# expansion_board_V0.net
KiCad netlist of a schematic drawn in EAGLE
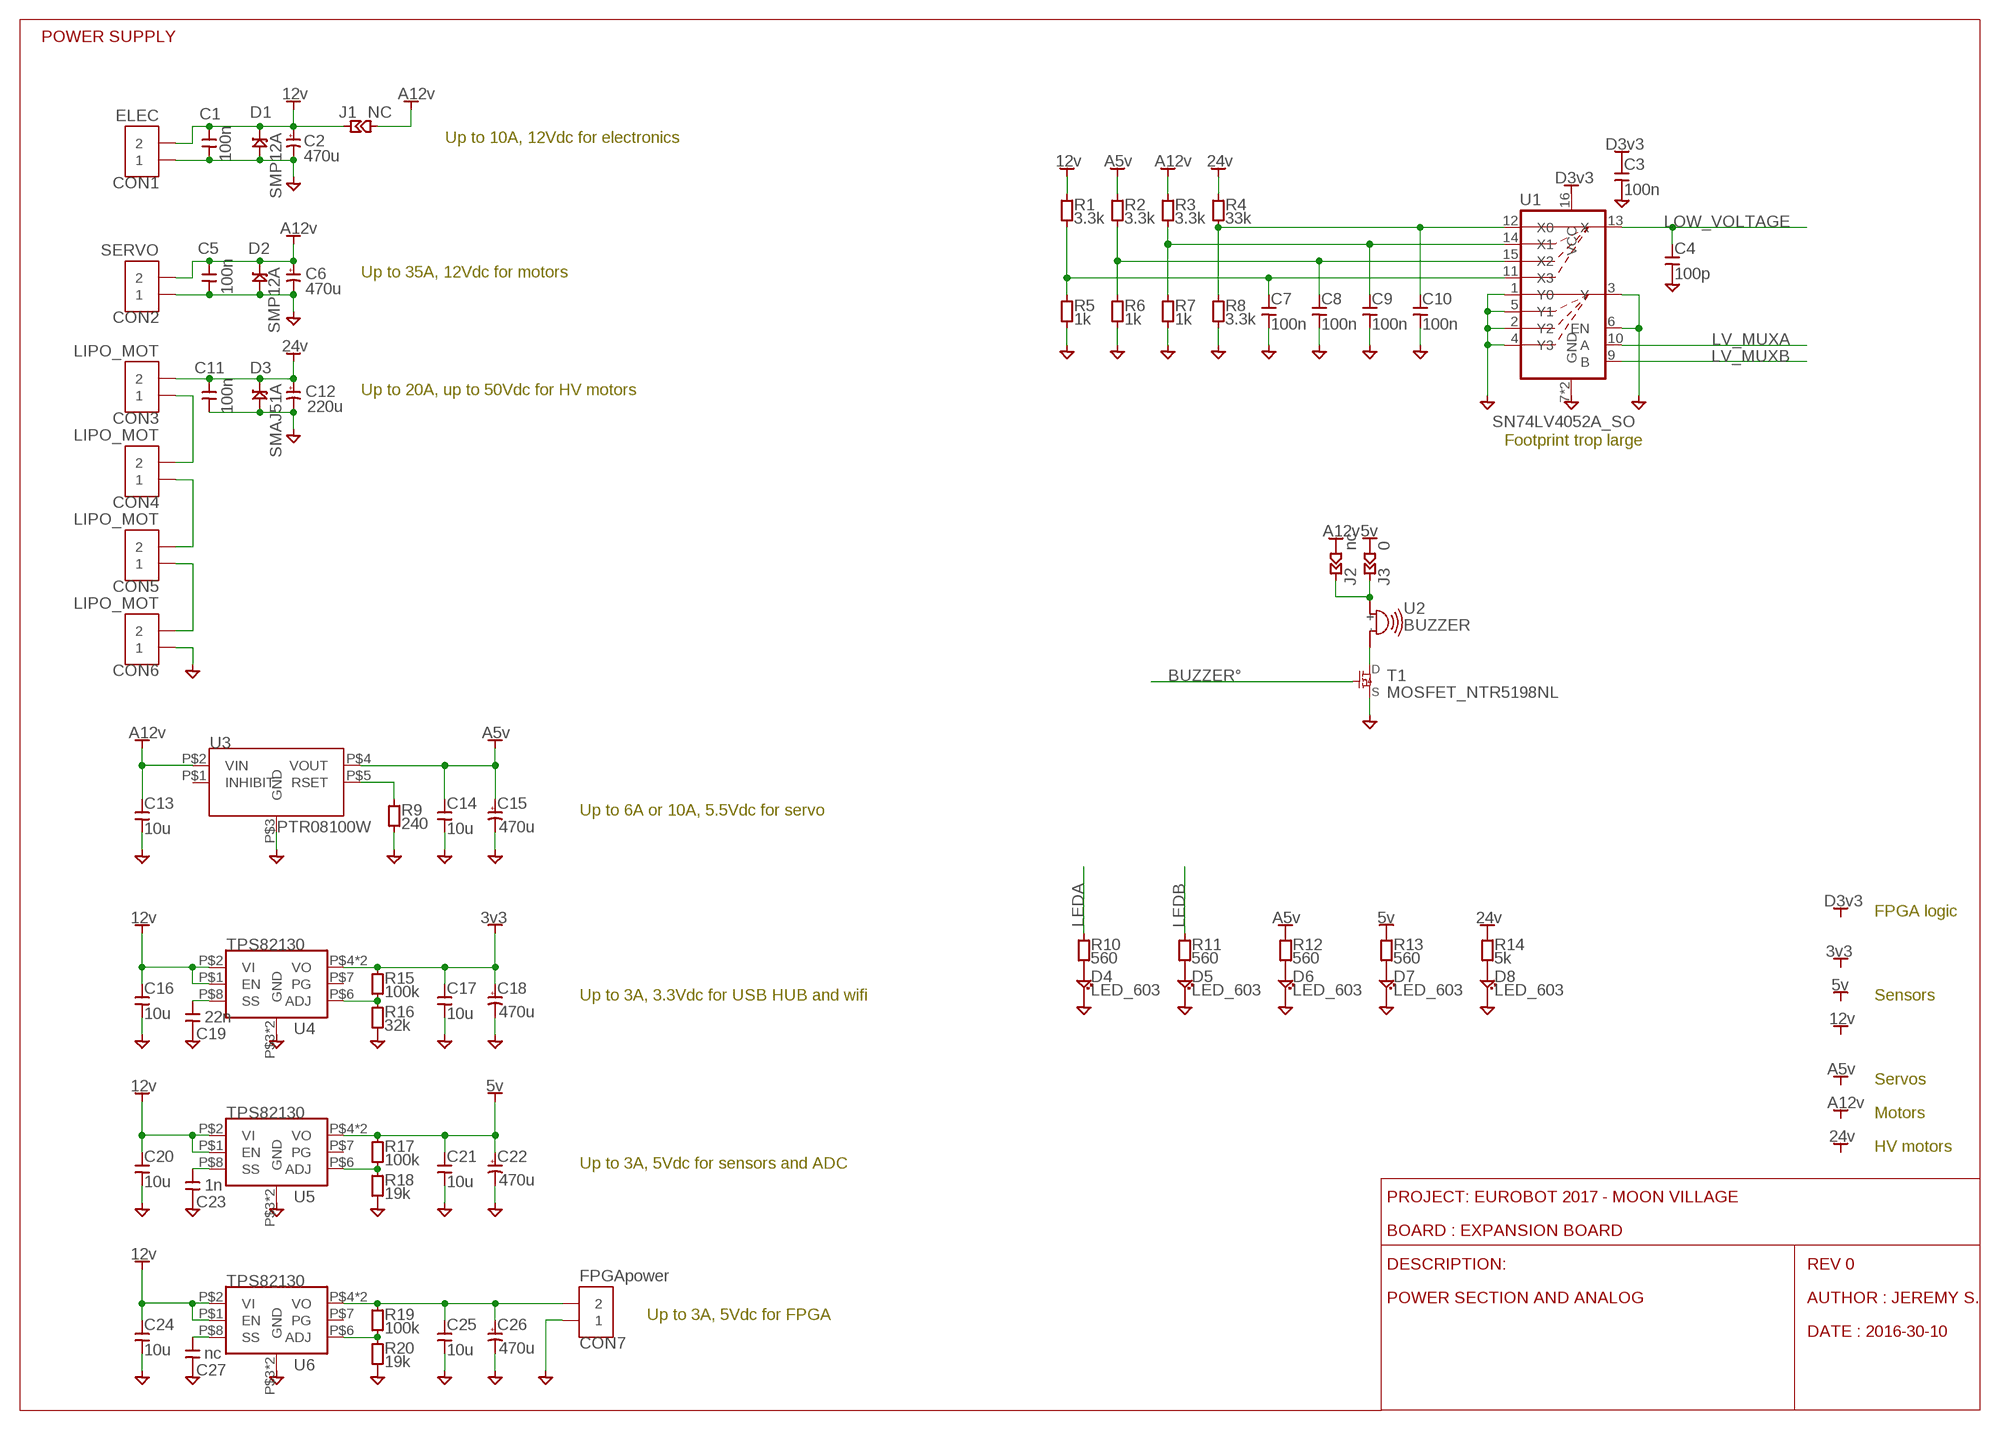
[diagram p0: schematic, sheet 1]
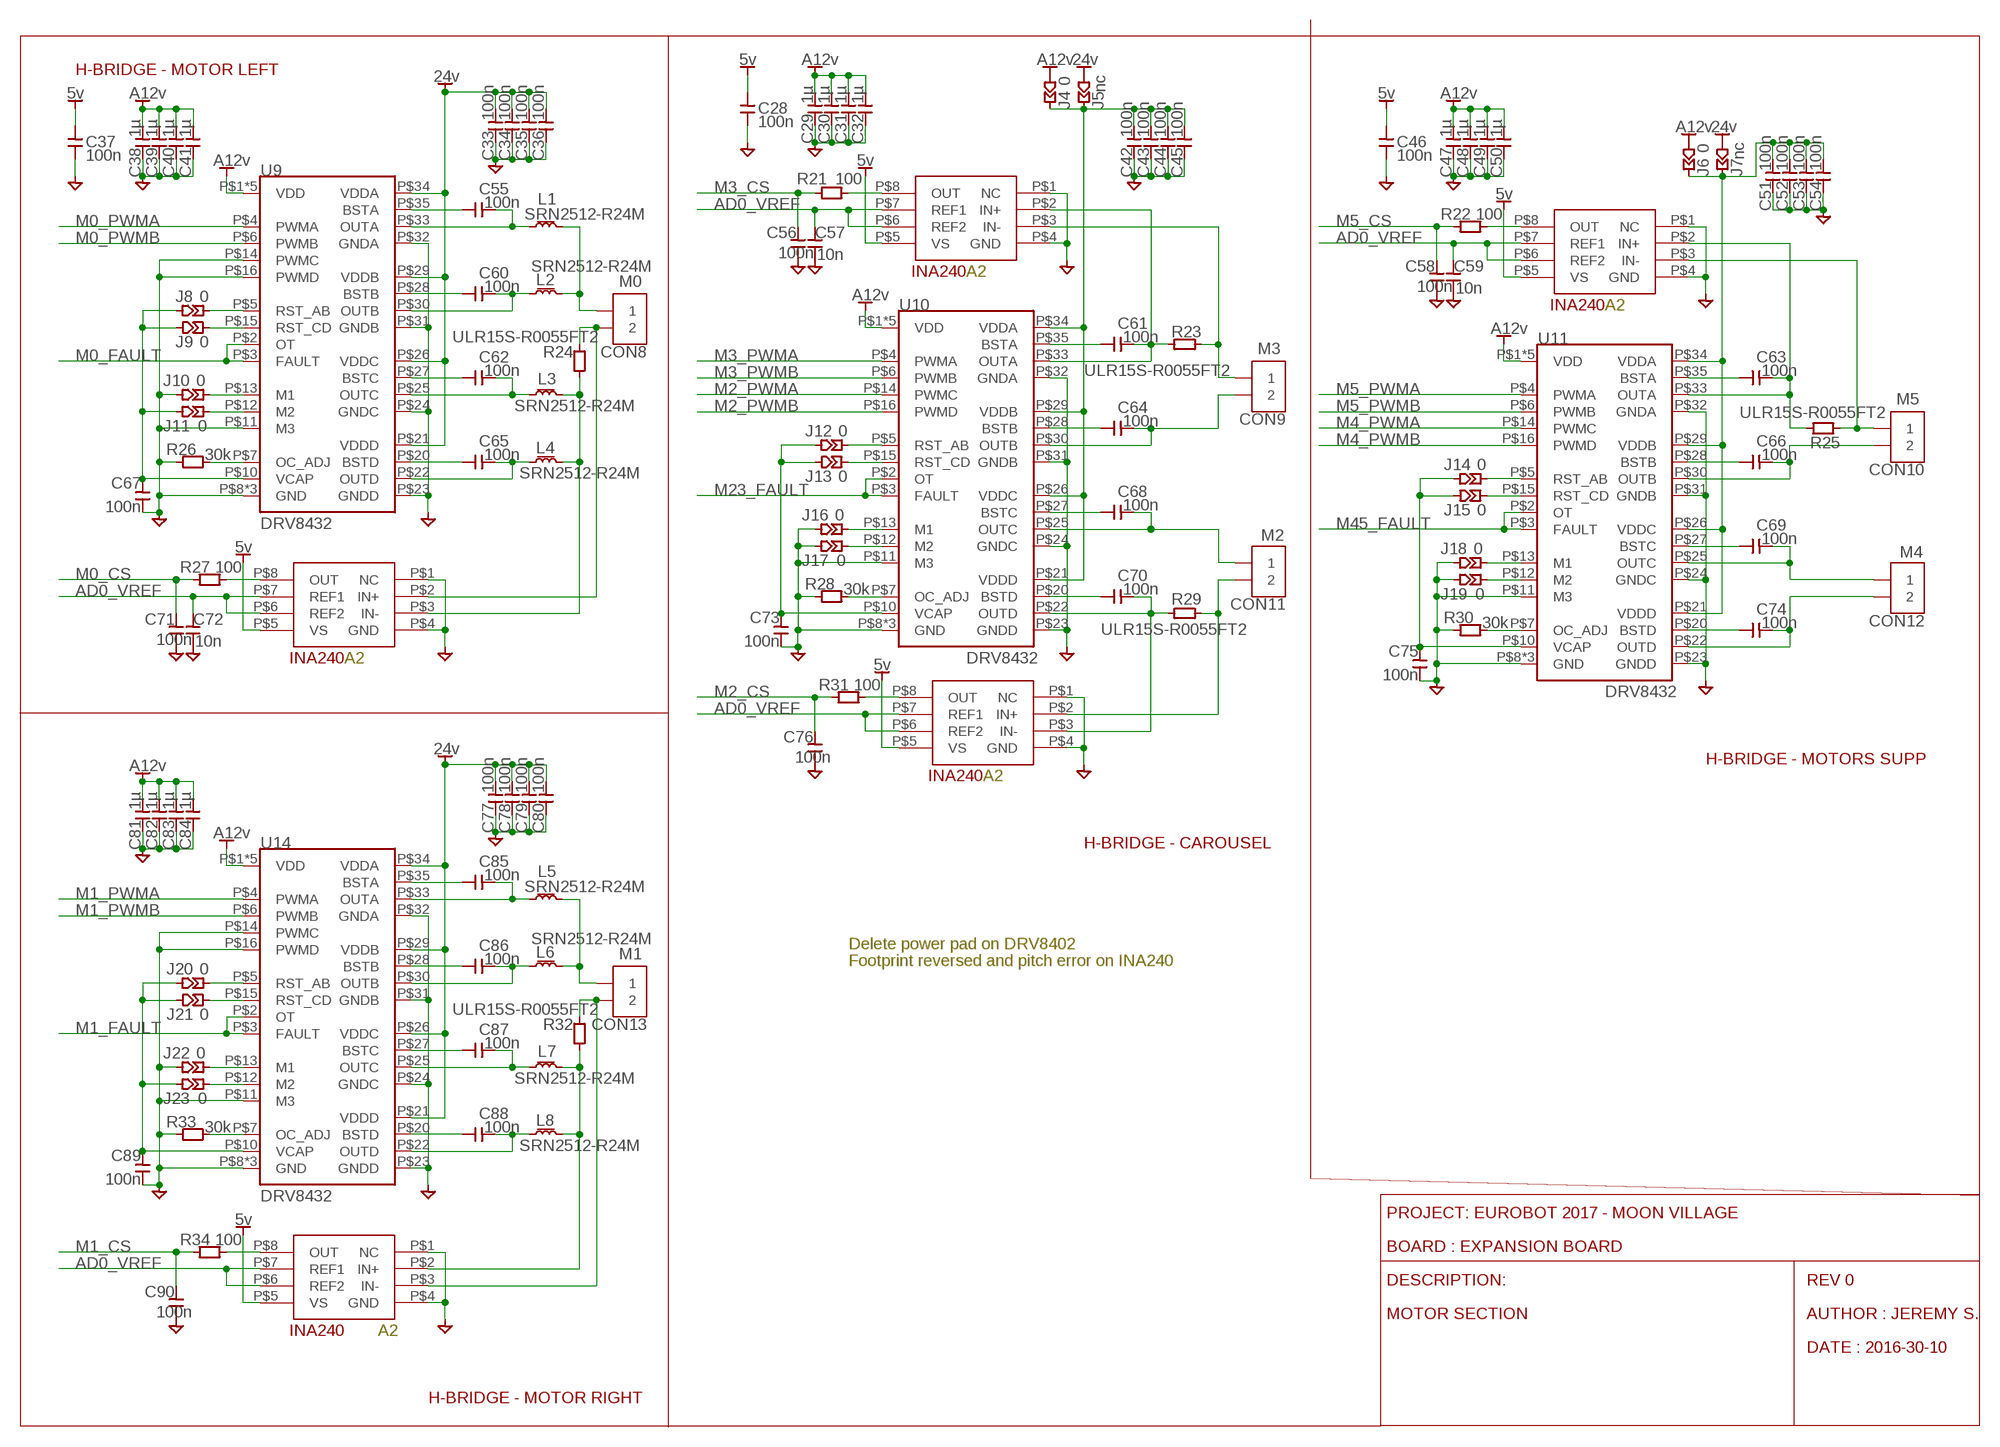
[diagram p1: schematic, sheet 2]
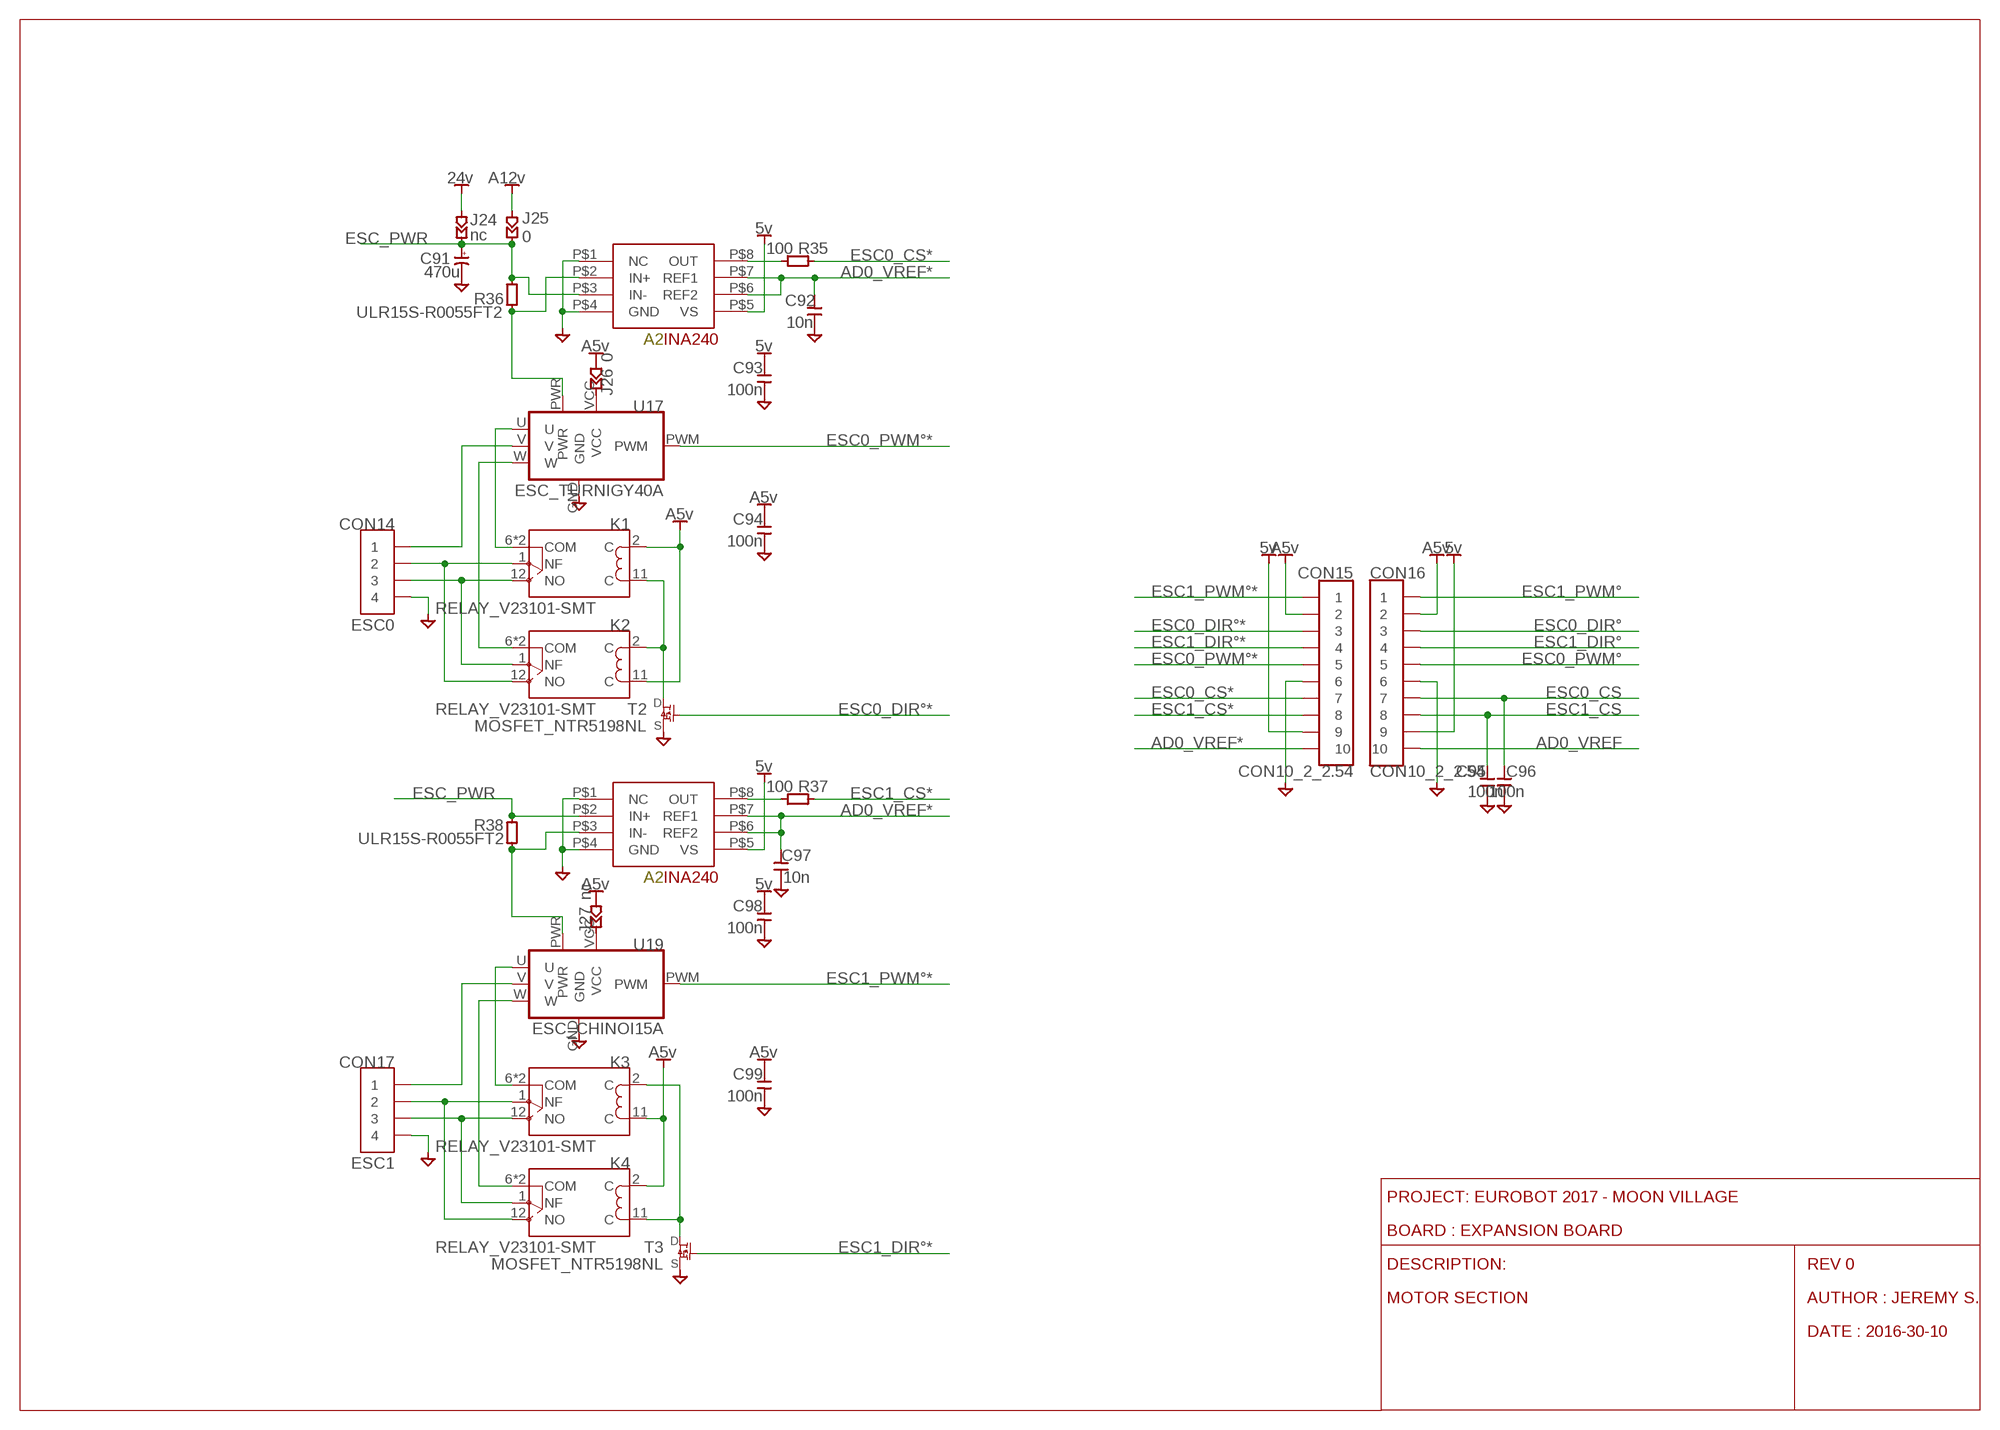
[diagram p2: schematic, sheet 3]
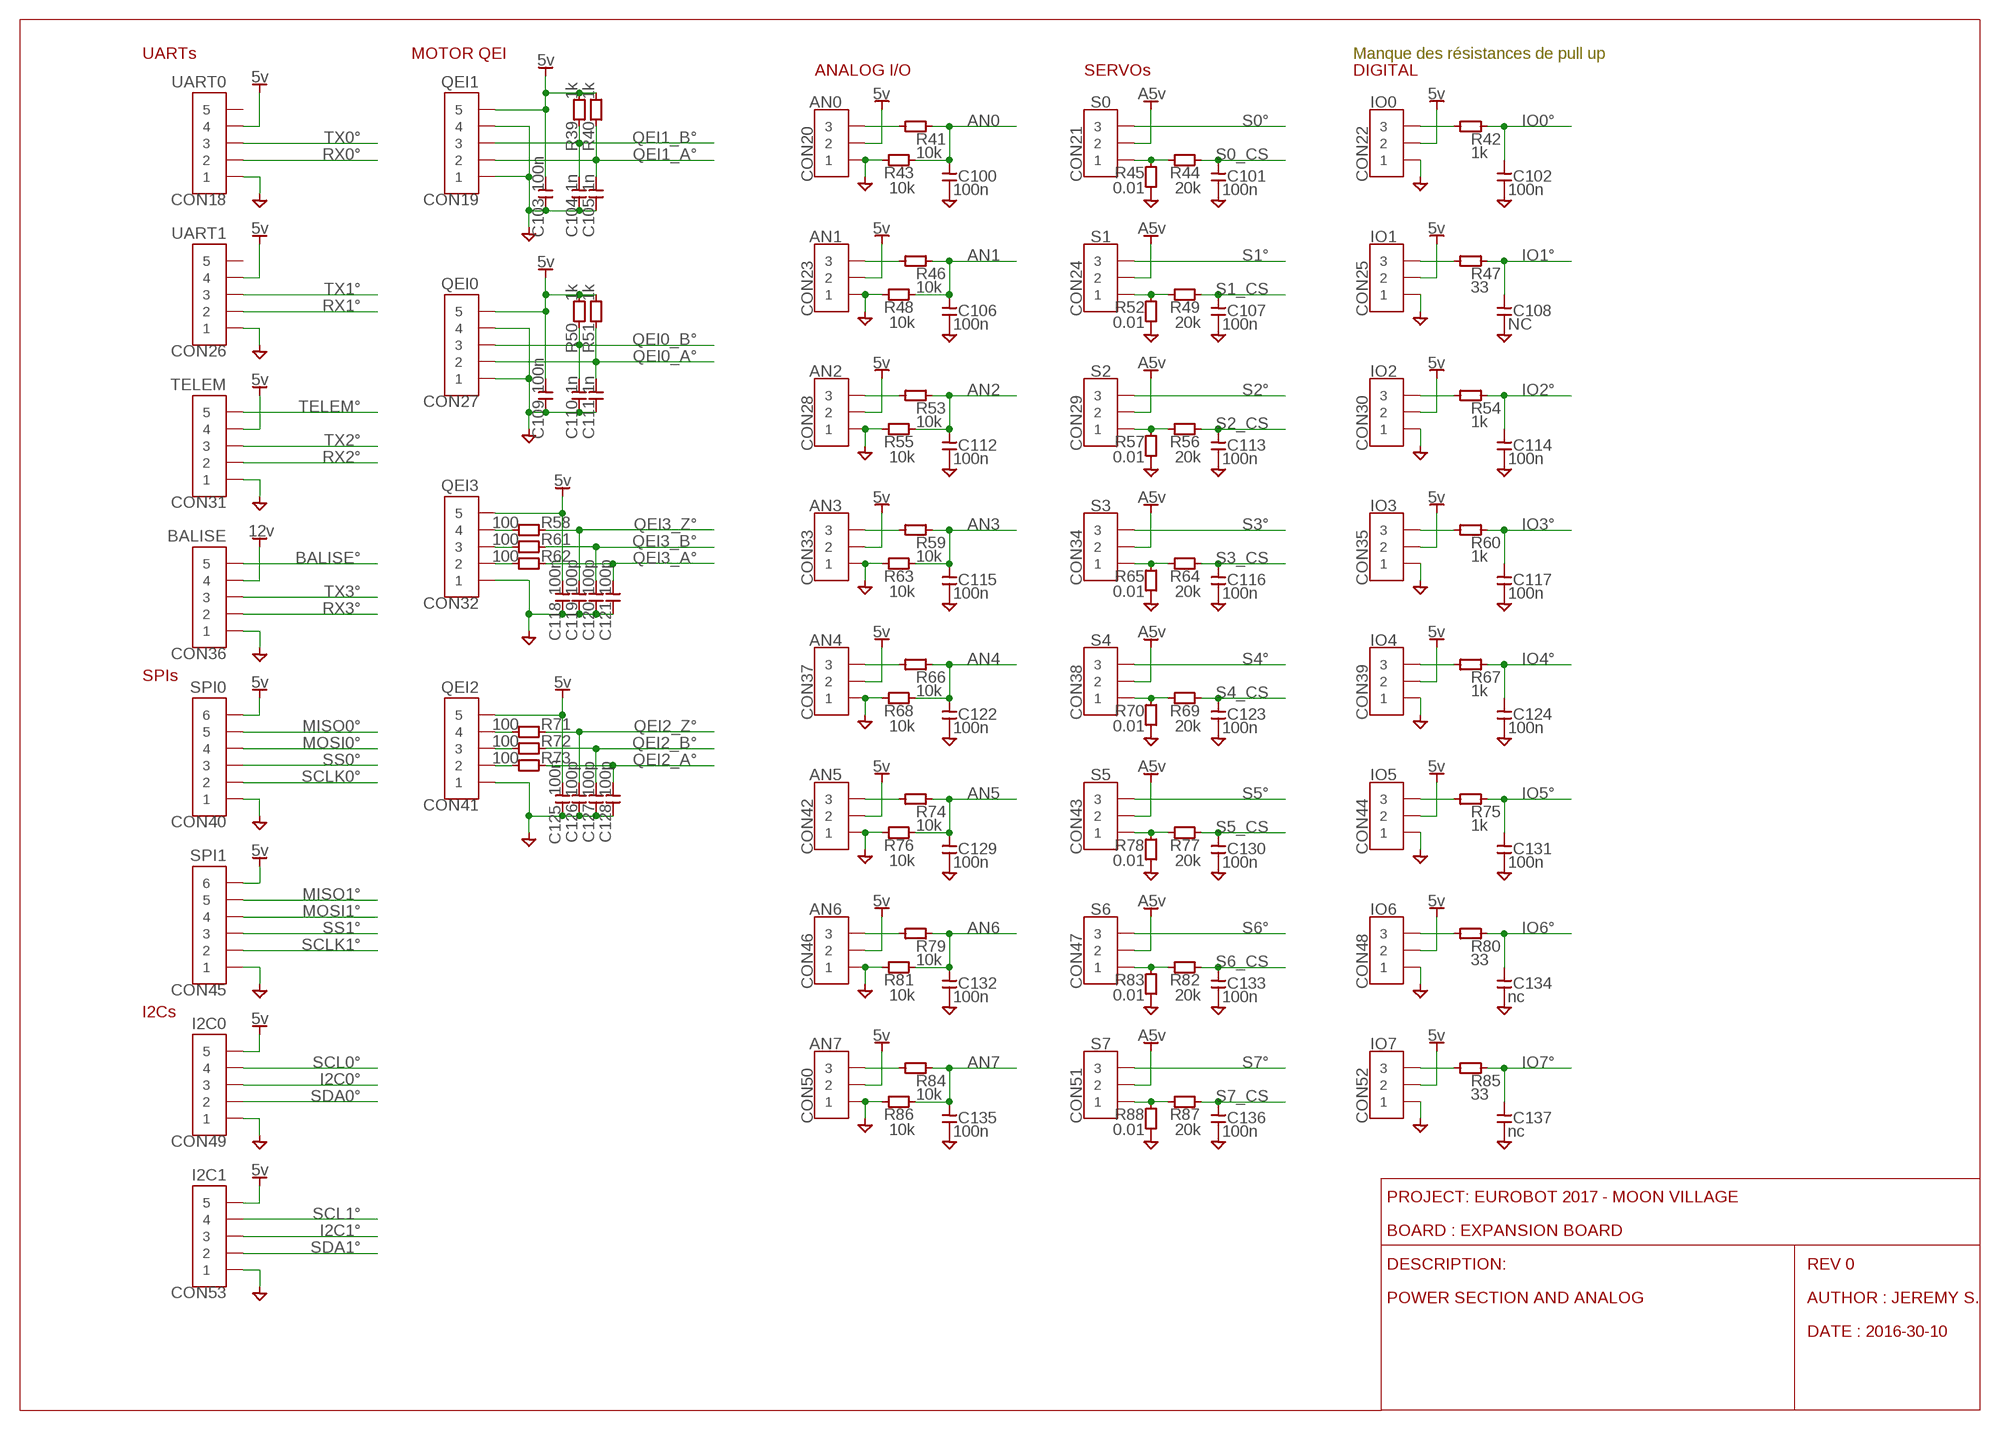
[diagram p3: schematic, sheet 4]
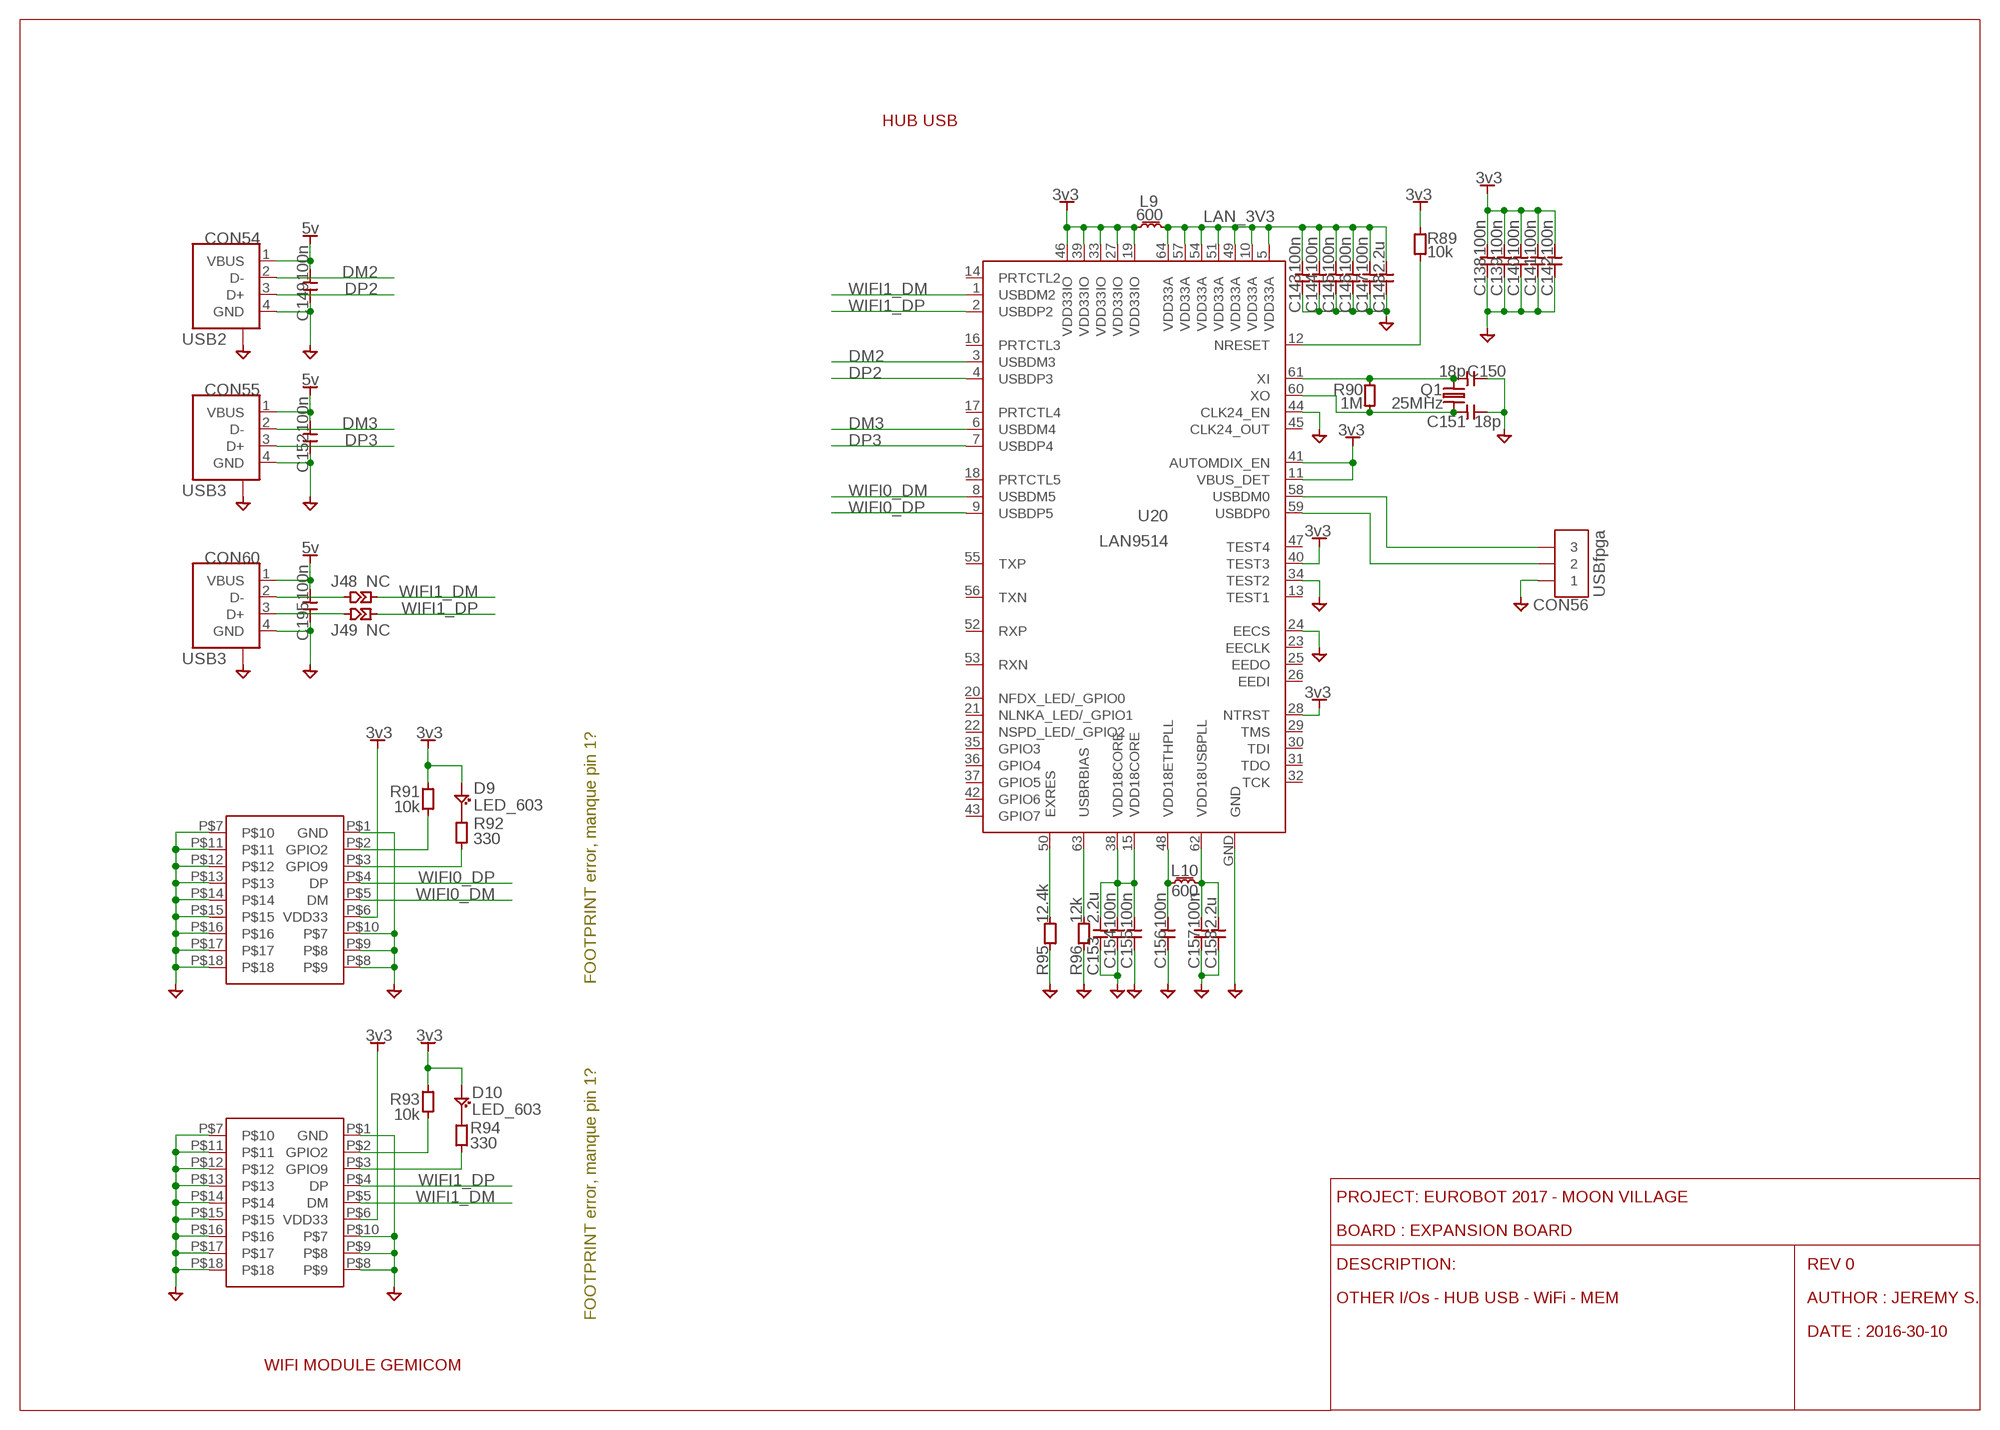
[diagram p4: schematic, sheet 5]
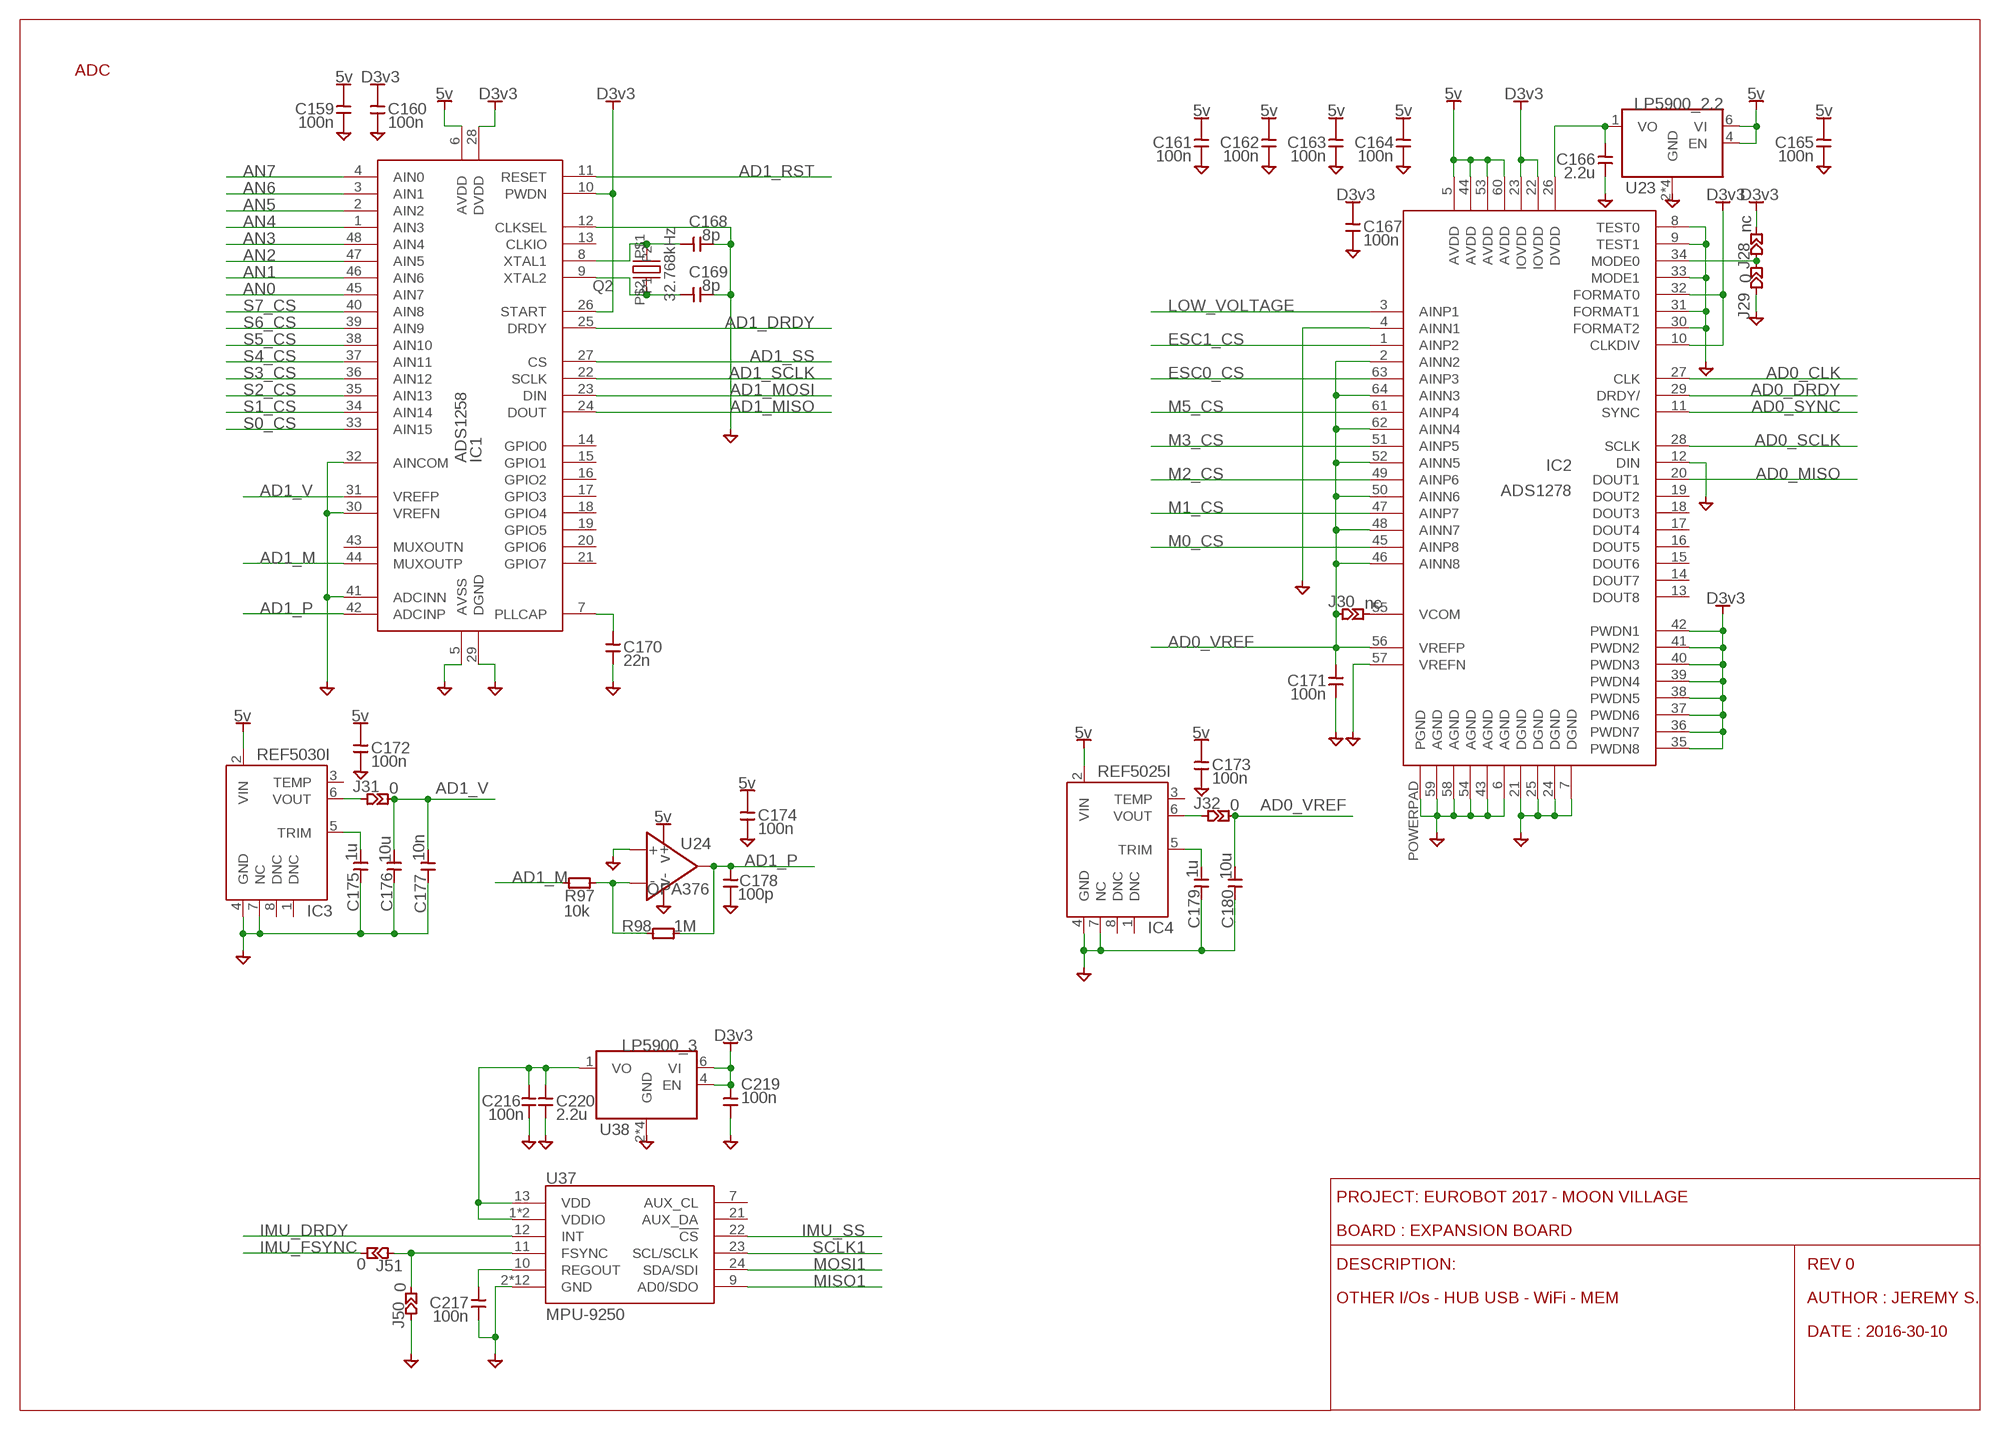
[diagram p5: schematic, sheet 6]
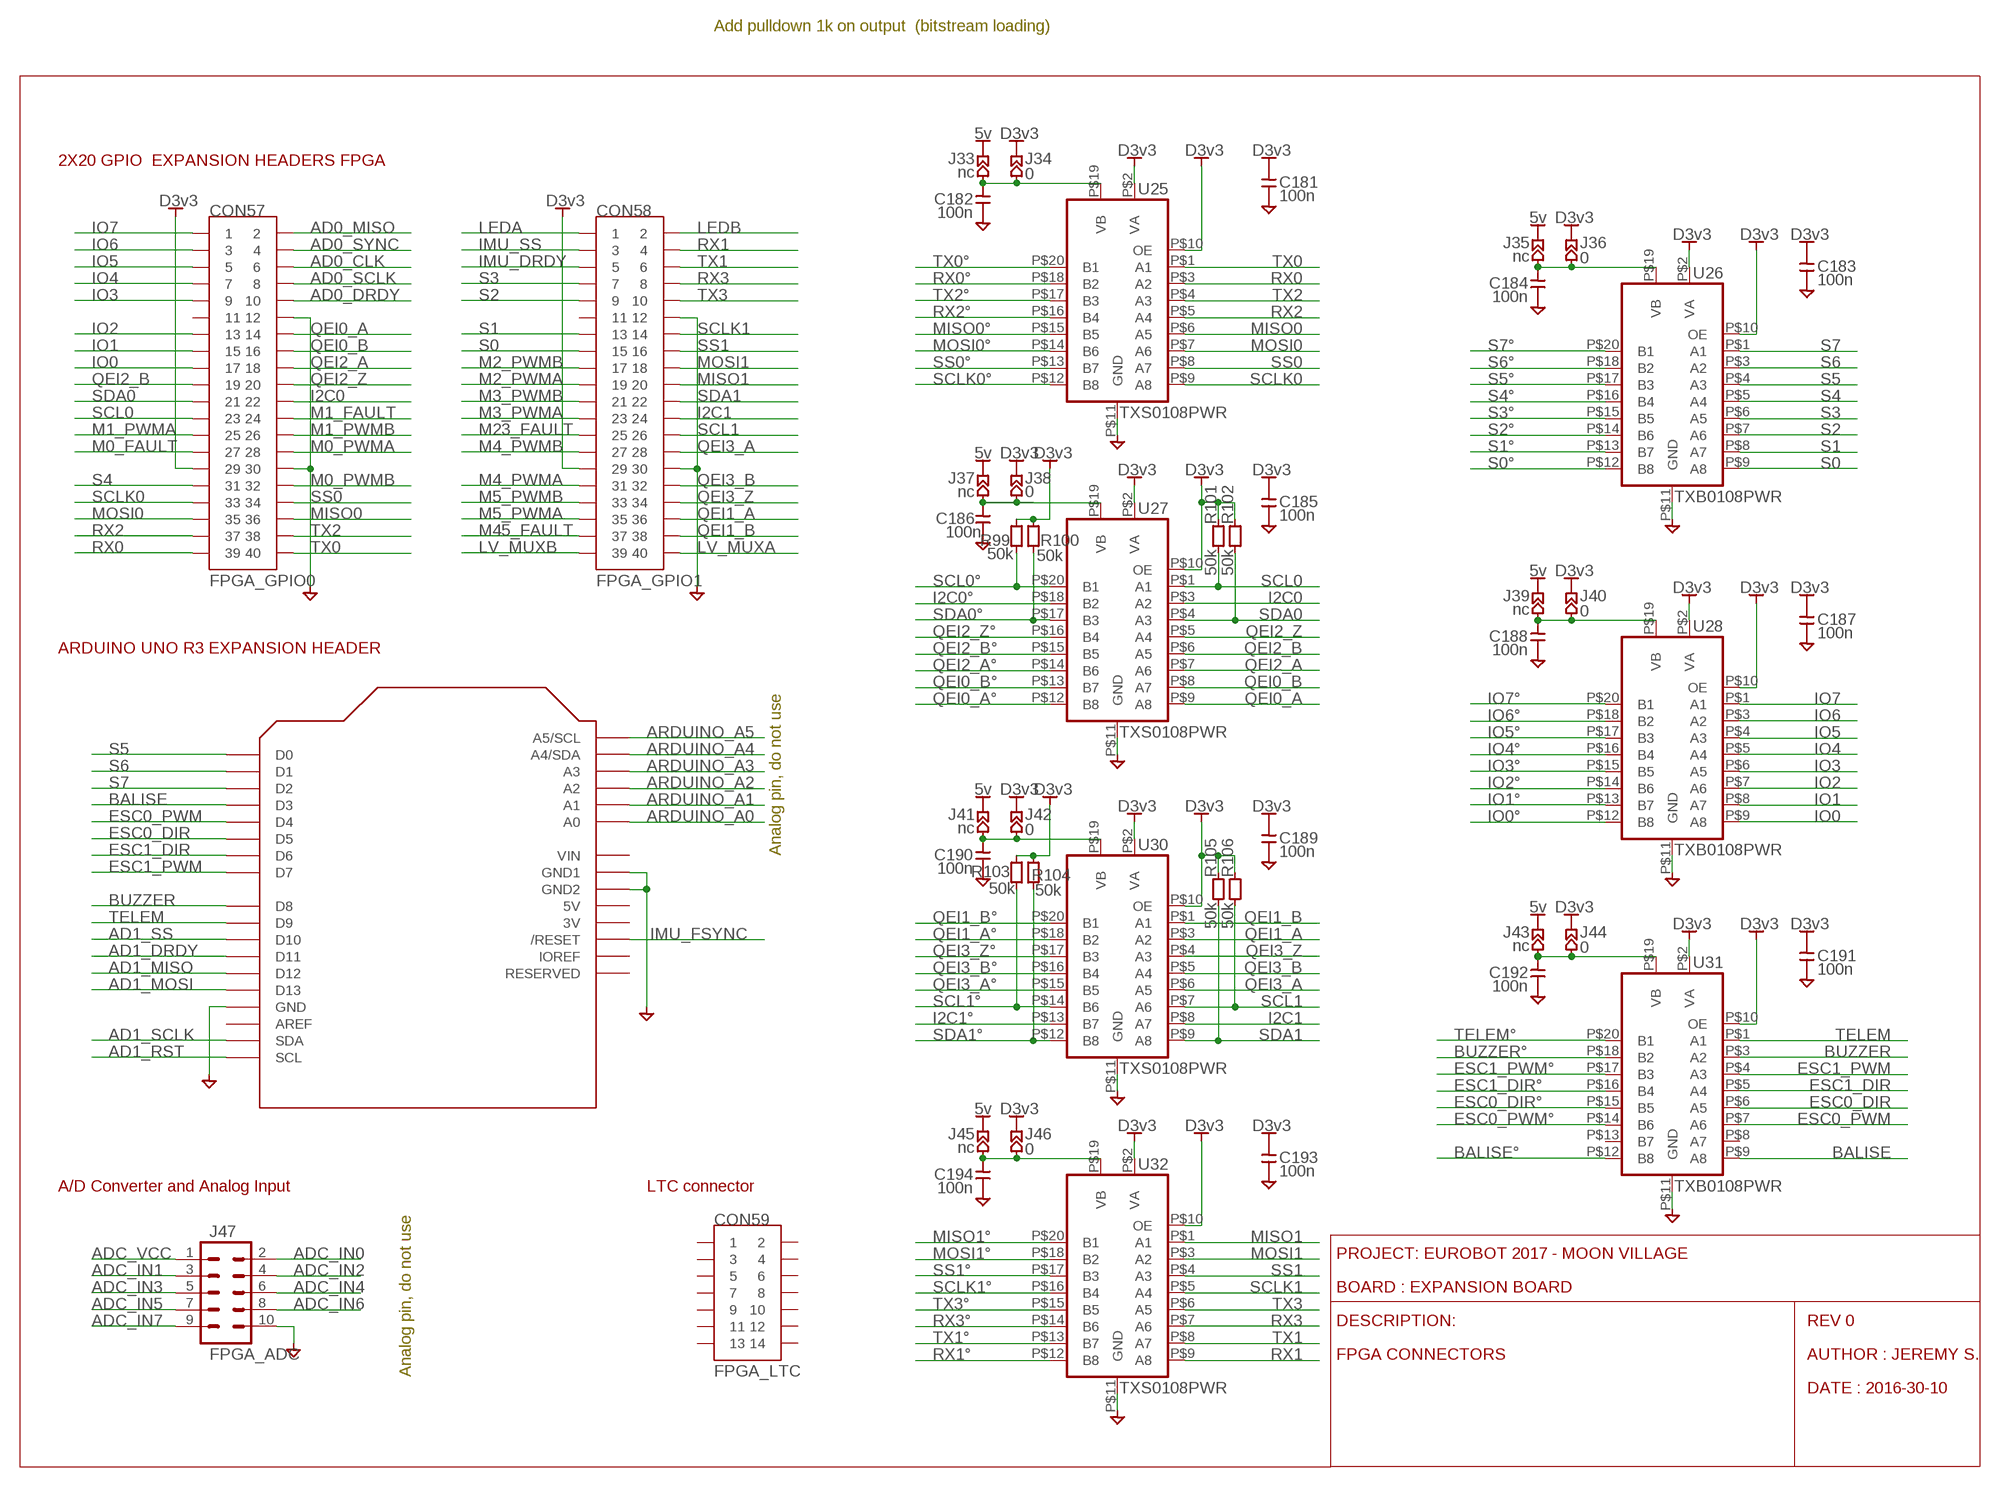
[diagram p6: schematic, sheet 7]
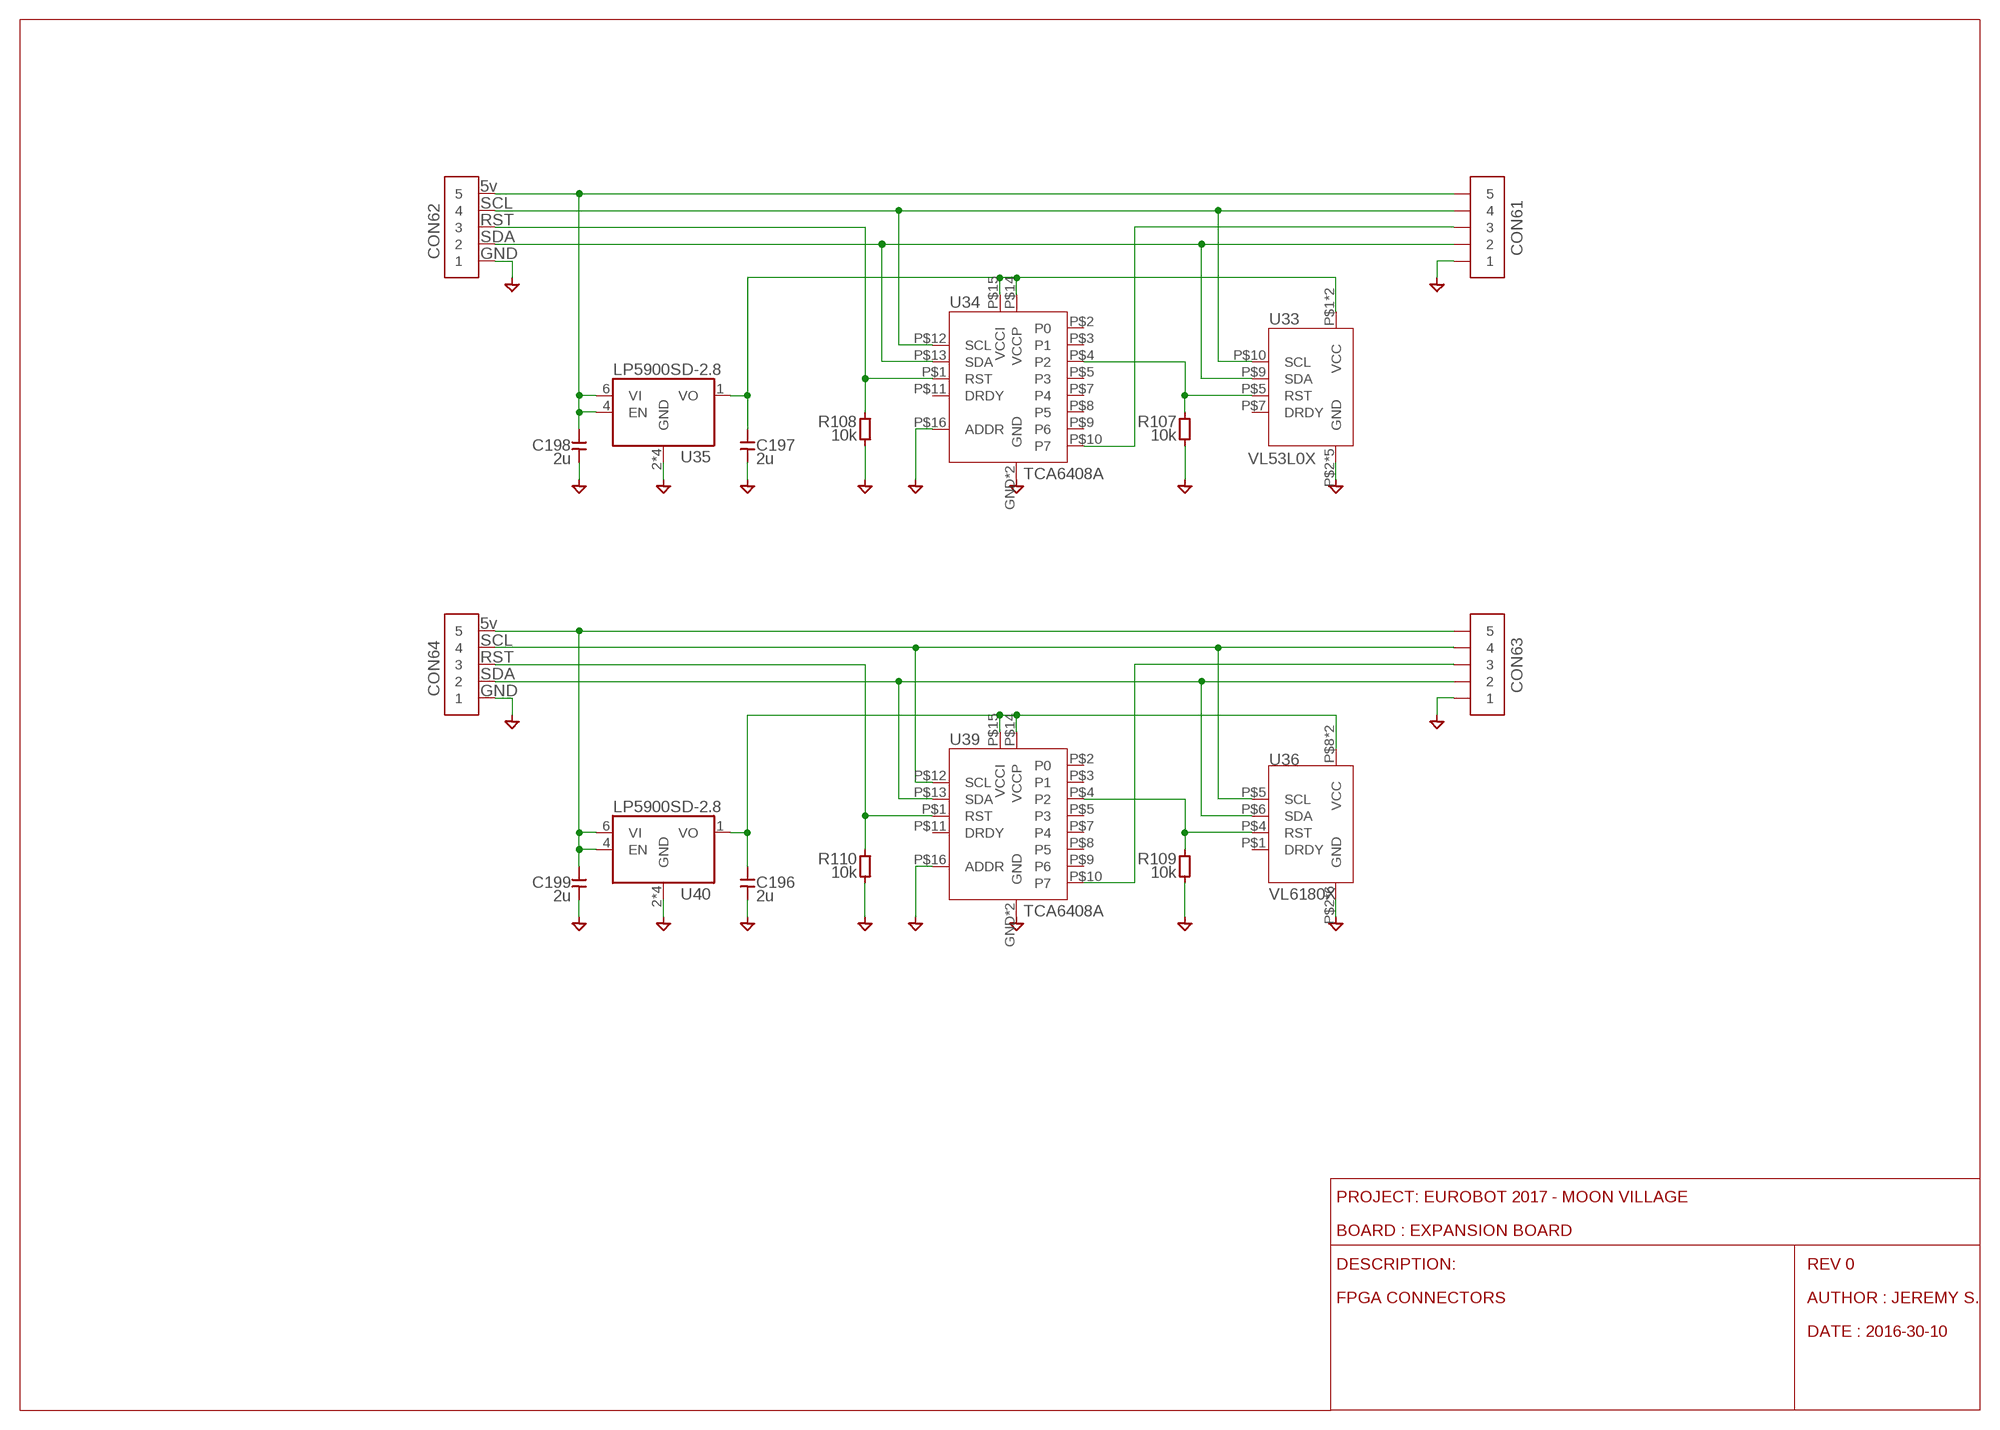
[diagram p7: schematic, sheet 8]

(export (version "E")
  (design (tool "Eeschema 10.0.6"))
  (components
    (comp (ref "C159")
      (value "100n")
      (footprint "eagle-import:CAPC1005X55N")
      (libsource (lib "eagle-import") (part "C_402"))
    )
    (comp (ref "C160")
      (value "100n")
      (footprint "eagle-import:CAPC1005X55N")
      (libsource (lib "eagle-import") (part "C_402"))
    )
    (comp (ref "C161")
      (value "100n")
      (footprint "eagle-import:CAPC1005X55N")
      (libsource (lib "eagle-import") (part "C_402"))
    )
    (comp (ref "C162")
      (value "100n")
      (footprint "eagle-import:CAPC1005X55N")
      (libsource (lib "eagle-import") (part "C_402"))
    )
    (comp (ref "C163")
      (value "100n")
      (footprint "eagle-import:CAPC1005X55N")
      (libsource (lib "eagle-import") (part "C_402"))
    )
    (comp (ref "C164")
      (value "100n")
      (footprint "eagle-import:CAPC1005X55N")
      (libsource (lib "eagle-import") (part "C_402"))
    )
    (comp (ref "C165")
      (value "100n")
      (footprint "eagle-import:CAPC1005X55N")
      (libsource (lib "eagle-import") (part "C_402"))
    )
    (comp (ref "C166")
      (value "2.2u")
      (footprint "eagle-import:CAPC1608X95N")
      (libsource (lib "eagle-import") (part "C_603"))
    )
    (comp (ref "C167")
      (value "100n")
      (footprint "eagle-import:CAPC1005X55N")
      (libsource (lib "eagle-import") (part "C_402"))
    )
    (comp (ref "C168")
      (value "8p")
      (footprint "eagle-import:CAPC1005X55N")
      (libsource (lib "eagle-import") (part "C_402"))
    )
    (comp (ref "C169")
      (value "8p")
      (footprint "eagle-import:CAPC1005X55N")
      (libsource (lib "eagle-import") (part "C_402"))
    )
    (comp (ref "C170")
      (value "22n")
      (footprint "eagle-import:CAPC1005X55N")
      (libsource (lib "eagle-import") (part "C_402"))
    )
    (comp (ref "C171")
      (value "100n")
      (footprint "eagle-import:CAPC1005X55N")
      (libsource (lib "eagle-import") (part "C_402"))
    )
    (comp (ref "C172")
      (value "100n")
      (footprint "eagle-import:CAPC1005X55N")
      (libsource (lib "eagle-import") (part "C_402"))
    )
    (comp (ref "C173")
      (value "100n")
      (footprint "eagle-import:CAPC1005X55N")
      (libsource (lib "eagle-import") (part "C_402"))
    )
    (comp (ref "C174")
      (value "100n")
      (footprint "eagle-import:CAPC1005X55N")
      (libsource (lib "eagle-import") (part "C_402"))
    )
    (comp (ref "C175")
      (value "1u")
      (footprint "eagle-import:CAPC1608X95N")
      (libsource (lib "eagle-import") (part "C_603"))
    )
    (comp (ref "C176")
      (value "10u")
      (footprint "eagle-import:CAPC2013X100N")
      (libsource (lib "eagle-import") (part "C_805"))
    )
    (comp (ref "C177")
      (value "10n")
      (footprint "eagle-import:CAPC1005X55N")
      (libsource (lib "eagle-import") (part "C_402"))
    )
    (comp (ref "C178")
      (value "100p")
      (footprint "eagle-import:CAPC1005X55N")
      (libsource (lib "eagle-import") (part "C_402"))
    )
    (comp (ref "C179")
      (value "1u")
      (footprint "eagle-import:CAPC1608X95N")
      (libsource (lib "eagle-import") (part "C_603"))
    )
    (comp (ref "C180")
      (value "10u")
      (footprint "eagle-import:CAPC2013X100N")
      (libsource (lib "eagle-import") (part "C_805"))
    )
    (comp (ref "C216")
      (value "100n")
      (footprint "eagle-import:CAPC1005X55N")
      (libsource (lib "eagle-import") (part "C_402"))
    )
    (comp (ref "C217")
      (value "100n")
      (footprint "eagle-import:CAPC1005X55N")
      (libsource (lib "eagle-import") (part "C_402"))
    )
    (comp (ref "C219")
      (value "100n")
      (footprint "eagle-import:CAPC1005X55N")
      (libsource (lib "eagle-import") (part "C_402"))
    )
    (comp (ref "C220")
      (value "2.2u")
      (footprint "eagle-import:CAPC1608X95N")
      (libsource (lib "eagle-import") (part "C_603"))
    )
    (comp (ref "IC1")
      (value "ADS1258")
      (footprint "eagle-import:QFN48")
      (libsource (lib "eagle-import") (part "ADS1258"))
    )
    (comp (ref "IC2")
      (value "ADS1278")
      (footprint "eagle-import:TQFP64_POWERPAD")
      (libsource (lib "eagle-import") (part "ADS1278{dblquote}"))
    )
    (comp (ref "IC3")
      (value "REF5030I")
      (footprint "eagle-import:MSOP8_0.65")
      (libsource (lib "eagle-import") (part "REF5025I"))
    )
    (comp (ref "IC4")
      (value "REF5025I")
      (footprint "eagle-import:MSOP8_0.65")
      (libsource (lib "eagle-import") (part "REF5025I"))
    )
    (comp (ref "J28")
      (value "nc")
      (footprint "eagle-import:JUMC1005X50N")
      (libsource (lib "eagle-import") (part "JUMP_402"))
    )
    (comp (ref "J29")
      (value "0")
      (footprint "eagle-import:JUMC1005X50N")
      (libsource (lib "eagle-import") (part "JUMP_402"))
    )
    (comp (ref "J30")
      (value "nc")
      (footprint "eagle-import:JUMC1005X50N")
      (libsource (lib "eagle-import") (part "JUMP_402"))
    )
    (comp (ref "J31")
      (value "0")
      (footprint "eagle-import:JUMC1005X50N")
      (libsource (lib "eagle-import") (part "JUMP_402"))
    )
    (comp (ref "J32")
      (value "0")
      (footprint "eagle-import:JUMC1005X50N")
      (libsource (lib "eagle-import") (part "JUMP_402"))
    )
    (comp (ref "J50")
      (value "0")
      (footprint "eagle-import:JUMC1005X50N")
      (libsource (lib "eagle-import") (part "JUMP_402"))
    )
    (comp (ref "J51")
      (value "0")
      (footprint "eagle-import:JUMC1005X50N")
      (libsource (lib "eagle-import") (part "JUMP_402"))
    )
    (comp (ref "Q2")
      (value "32.768kHz")
      (footprint "eagle-import:1206")
      (libsource (lib "eagle-import") (part "QUARTZ_1206"))
    )
    (comp (ref "R97")
      (value "10k")
      (footprint "eagle-import:RESC1005X40N")
      (libsource (lib "eagle-import") (part "R_402"))
    )
    (comp (ref "R98")
      (value "1M")
      (footprint "eagle-import:RESC1005X40N")
      (libsource (lib "eagle-import") (part "R_402"))
    )
    (comp (ref "U23")
      (value "LP5900_2.2")
      (footprint "eagle-import:SON65P250X220X80-7N")
      (libsource (lib "eagle-import") (part "REG_EN_LP5900"))
    )
    (comp (ref "U24")
      (value "OPA376")
      (footprint "eagle-import:SC70-5N")
      (libsource (lib "eagle-import") (part "OPA376"))
    )
    (comp (ref "U37")
      (value "MPU-9250")
      (footprint "eagle-import:QFN24-3X3")
      (libsource (lib "eagle-import") (part "MPU-9250"))
    )
    (comp (ref "U38")
      (value "LP5900_3")
      (footprint "eagle-import:SON65P250X220X80-7N")
      (libsource (lib "eagle-import") (part "REG_EN_LP5900"))
    )
    (comp (ref "C91")
      (value "470u")
      (footprint "eagle-import:CAPAE835X1020N")
      (libsource (lib "eagle-import") (part "CPOL"))
    )
    (comp (ref "C92")
      (value "10n")
      (footprint "eagle-import:CAPC1005X55N")
      (libsource (lib "eagle-import") (part "C_402"))
    )
    (comp (ref "C93")
      (value "100n")
      (footprint "eagle-import:CAPC1005X55N")
      (libsource (lib "eagle-import") (part "C_402"))
    )
    (comp (ref "C94")
      (value "100n")
      (footprint "eagle-import:CAPC1005X55N")
      (libsource (lib "eagle-import") (part "C_402"))
    )
    (comp (ref "C95")
      (value "100n")
      (footprint "eagle-import:CAPC1005X55N")
      (libsource (lib "eagle-import") (part "C_402"))
    )
    (comp (ref "C96")
      (value "100n")
      (footprint "eagle-import:CAPC1005X55N")
      (libsource (lib "eagle-import") (part "C_402"))
    )
    (comp (ref "C97")
      (value "10n")
      (footprint "eagle-import:CAPC1005X55N")
      (libsource (lib "eagle-import") (part "C_402"))
    )
    (comp (ref "C98")
      (value "100n")
      (footprint "eagle-import:CAPC1005X55N")
      (libsource (lib "eagle-import") (part "C_402"))
    )
    (comp (ref "C99")
      (value "100n")
      (footprint "eagle-import:CAPC1005X55N")
      (libsource (lib "eagle-import") (part "C_402"))
    )
    (comp (ref "CON14")
      (value "ESC0")
      (footprint "eagle-import:PHOENIX381P1662X920-4N")
      (libsource (lib "eagle-import") (part "CON4_3.81"))
    )
    (comp (ref "CON15")
      (value "CON10_2_2.54")
      (footprint "eagle-import:CON245P2030X890-2X5N")
      (libsource (lib "eagle-import") (part "CON10_2_2.54"))
    )
    (comp (ref "CON16")
      (value "CON10_2_2.54")
      (footprint "eagle-import:CON245P2030X890-2X5N")
      (libsource (lib "eagle-import") (part "CON10_2_2.54"))
    )
    (comp (ref "CON17")
      (value "ESC1")
      (footprint "eagle-import:PHOENIX381P1662X920-4N")
      (libsource (lib "eagle-import") (part "CON4_3.81"))
    )
    (comp (ref "J24")
      (value "nc")
      (footprint "eagle-import:JUMC1608X50AN")
      (libsource (lib "eagle-import") (part "JUMP_603"))
    )
    (comp (ref "J25")
      (value "0")
      (footprint "eagle-import:JUMC1608X50AN")
      (libsource (lib "eagle-import") (part "JUMP_603"))
    )
    (comp (ref "J26")
      (value "0")
      (footprint "eagle-import:JUMC1005X50N")
      (libsource (lib "eagle-import") (part "JUMP_402"))
    )
    (comp (ref "J27")
      (value "nc")
      (footprint "eagle-import:JUMC1005X50N")
      (libsource (lib "eagle-import") (part "JUMP_402"))
    )
    (comp (ref "K1")
      (value "RELAY_V23101-SMT")
      (footprint "eagle-import:V23101-D0103-A201-SMT")
      (libsource (lib "eagle-import") (part "RELAY_V23101-SMT"))
    )
    (comp (ref "K2")
      (value "RELAY_V23101-SMT")
      (footprint "eagle-import:V23101-D0103-A201-SMT")
      (libsource (lib "eagle-import") (part "RELAY_V23101-SMT"))
    )
    (comp (ref "K3")
      (value "RELAY_V23101-SMT")
      (footprint "eagle-import:V23101-D0103-A201-SMT")
      (libsource (lib "eagle-import") (part "RELAY_V23101-SMT"))
    )
    (comp (ref "K4")
      (value "RELAY_V23101-SMT")
      (footprint "eagle-import:V23101-D0103-A201-SMT")
      (libsource (lib "eagle-import") (part "RELAY_V23101-SMT"))
    )
    (comp (ref "R35")
      (value "100")
      (footprint "eagle-import:RESC1005X40N")
      (libsource (lib "eagle-import") (part "R_402"))
    )
    (comp (ref "R36")
      (value "ULR15S-R0055FT2")
      (footprint "eagle-import:RESC_ULR15S-R0055FT2")
      (libsource (lib "eagle-import") (part "R_ULR15S-R0055FT2"))
    )
    (comp (ref "R37")
      (value "100")
      (footprint "eagle-import:RESC1005X40N")
      (libsource (lib "eagle-import") (part "R_402"))
    )
    (comp (ref "R38")
      (value "ULR15S-R0055FT2")
      (footprint "eagle-import:RESC_ULR15S-R0055FT2")
      (libsource (lib "eagle-import") (part "R_ULR15S-R0055FT2"))
    )
    (comp (ref "T2")
      (value "MOSFET_NTR5198NL")
      (footprint "eagle-import:SOT95P290X130-3N")
      (libsource (lib "eagle-import") (part "MOSFET_NTR5198NL"))
    )
    (comp (ref "T3")
      (value "MOSFET_NTR5198NL")
      (footprint "eagle-import:SOT95P290X130-3N")
      (libsource (lib "eagle-import") (part "MOSFET_NTR5198NL"))
    )
    (comp (ref "U16")
      (value "INA240-A2")
      (footprint "eagle-import:TSSOP")
      (libsource (lib "eagle-import") (part "INA240-TSSOP"))
    )
    (comp (ref "U17")
      (value "ESC_TURNIGY40A")
      (footprint "eagle-import:ESC_TURNIGY40A")
      (libsource (lib "eagle-import") (part "ESC_TURNIGY40A"))
    )
    (comp (ref "U18")
      (value "INA240-A2")
      (footprint "eagle-import:TSSOP")
      (libsource (lib "eagle-import") (part "INA240-TSSOP"))
    )
    (comp (ref "U19")
      (value "ESC_CHINOI15A")
      (footprint "eagle-import:ESC_CHINOI15A")
      (libsource (lib "eagle-import") (part "ESC_CHINOI15A"))
    )
    (comp (ref "C181")
      (value "100n")
      (footprint "eagle-import:CAPC1005X55N")
      (libsource (lib "eagle-import") (part "C_402"))
    )
    (comp (ref "C182")
      (value "100n")
      (footprint "eagle-import:CAPC1005X55N")
      (libsource (lib "eagle-import") (part "C_402"))
    )
    (comp (ref "C183")
      (value "100n")
      (footprint "eagle-import:CAPC1005X55N")
      (libsource (lib "eagle-import") (part "C_402"))
    )
    (comp (ref "C184")
      (value "100n")
      (footprint "eagle-import:CAPC1005X55N")
      (libsource (lib "eagle-import") (part "C_402"))
    )
    (comp (ref "C185")
      (value "100n")
      (footprint "eagle-import:CAPC1005X55N")
      (libsource (lib "eagle-import") (part "C_402"))
    )
    (comp (ref "C186")
      (value "100n")
      (footprint "eagle-import:CAPC1005X55N")
      (libsource (lib "eagle-import") (part "C_402"))
    )
    (comp (ref "C187")
      (value "100n")
      (footprint "eagle-import:CAPC1005X55N")
      (libsource (lib "eagle-import") (part "C_402"))
    )
    (comp (ref "C188")
      (value "100n")
      (footprint "eagle-import:CAPC1005X55N")
      (libsource (lib "eagle-import") (part "C_402"))
    )
    (comp (ref "C189")
      (value "100n")
      (footprint "eagle-import:CAPC1005X55N")
      (libsource (lib "eagle-import") (part "C_402"))
    )
    (comp (ref "C190")
      (value "100n")
      (footprint "eagle-import:CAPC1005X55N")
      (libsource (lib "eagle-import") (part "C_402"))
    )
    (comp (ref "C191")
      (value "100n")
      (footprint "eagle-import:CAPC1005X55N")
      (libsource (lib "eagle-import") (part "C_402"))
    )
    (comp (ref "C192")
      (value "100n")
      (footprint "eagle-import:CAPC1005X55N")
      (libsource (lib "eagle-import") (part "C_402"))
    )
    (comp (ref "C193")
      (value "100n")
      (footprint "eagle-import:CAPC1005X55N")
      (libsource (lib "eagle-import") (part "C_402"))
    )
    (comp (ref "C194")
      (value "100n")
      (footprint "eagle-import:CAPC1005X55N")
      (libsource (lib "eagle-import") (part "C_402"))
    )
    (comp (ref "CON57")
      (value "FPGA_GPIO0")
      (footprint "eagle-import:CON254P5080X600-40N")
      (libsource (lib "eagle-import") (part "CON40_2.54"))
    )
    (comp (ref "CON58")
      (value "FPGA_GPIO1")
      (footprint "eagle-import:CON254P5080X600-40N")
      (libsource (lib "eagle-import") (part "CON40_2.54"))
    )
    (comp (ref "CON59")
      (value "FPGA_LTC")
      (footprint "eagle-import:CON200P1700X400-2X7N")
      (libsource (lib "eagle-import") (part "CON14"))
    )
    (comp (ref "J33")
      (value "nc")
      (footprint "eagle-import:JUMC1005X50N")
      (libsource (lib "eagle-import") (part "JUMP_402"))
    )
    (comp (ref "J34")
      (value "0")
      (footprint "eagle-import:JUMC1005X50N")
      (libsource (lib "eagle-import") (part "JUMP_402"))
    )
    (comp (ref "J35")
      (value "nc")
      (footprint "eagle-import:JUMC1005X50N")
      (libsource (lib "eagle-import") (part "JUMP_402"))
    )
    (comp (ref "J36")
      (value "0")
      (footprint "eagle-import:JUMC1005X50N")
      (libsource (lib "eagle-import") (part "JUMP_402"))
    )
    (comp (ref "J37")
      (value "nc")
      (footprint "eagle-import:JUMC1005X50N")
      (libsource (lib "eagle-import") (part "JUMP_402"))
    )
    (comp (ref "J38")
      (value "0")
      (footprint "eagle-import:JUMC1005X50N")
      (libsource (lib "eagle-import") (part "JUMP_402"))
    )
    (comp (ref "J39")
      (value "nc")
      (footprint "eagle-import:JUMC1005X50N")
      (libsource (lib "eagle-import") (part "JUMP_402"))
    )
    (comp (ref "J40")
      (value "0")
      (footprint "eagle-import:JUMC1005X50N")
      (libsource (lib "eagle-import") (part "JUMP_402"))
    )
    (comp (ref "J41")
      (value "nc")
      (footprint "eagle-import:JUMC1005X50N")
      (libsource (lib "eagle-import") (part "JUMP_402"))
    )
    (comp (ref "J42")
      (value "0")
      (footprint "eagle-import:JUMC1005X50N")
      (libsource (lib "eagle-import") (part "JUMP_402"))
    )
    (comp (ref "J43")
      (value "nc")
      (footprint "eagle-import:JUMC1005X50N")
      (libsource (lib "eagle-import") (part "JUMP_402"))
    )
    (comp (ref "J44")
      (value "0")
      (footprint "eagle-import:JUMC1005X50N")
      (libsource (lib "eagle-import") (part "JUMP_402"))
    )
    (comp (ref "J45")
      (value "nc")
      (footprint "eagle-import:JUMC1005X50N")
      (libsource (lib "eagle-import") (part "JUMP_402"))
    )
    (comp (ref "J46")
      (value "0")
      (footprint "eagle-import:JUMC1005X50N")
      (libsource (lib "eagle-import") (part "JUMP_402"))
    )
    (comp (ref "J47")
      (value "FPGA_ADC")
      (footprint "eagle-import:2X5_NOSILK")
      (libsource (lib "eagle-import") (part "M05X2NO_SILK"))
    )
    (comp (ref "R99")
      (value "50k")
      (footprint "eagle-import:RESC1005X40N")
      (libsource (lib "eagle-import") (part "R_402"))
    )
    (comp (ref "R100")
      (value "50k")
      (footprint "eagle-import:RESC1005X40N")
      (libsource (lib "eagle-import") (part "R_402"))
    )
    (comp (ref "R101")
      (value "50k")
      (footprint "eagle-import:RESC1005X40N")
      (libsource (lib "eagle-import") (part "R_402"))
    )
    (comp (ref "R102")
      (value "50k")
      (footprint "eagle-import:RESC1005X40N")
      (libsource (lib "eagle-import") (part "R_402"))
    )
    (comp (ref "R103")
      (value "50k")
      (footprint "eagle-import:RESC1005X40N")
      (libsource (lib "eagle-import") (part "R_402"))
    )
    (comp (ref "R104")
      (value "50k")
      (footprint "eagle-import:RESC1005X40N")
      (libsource (lib "eagle-import") (part "R_402"))
    )
    (comp (ref "R105")
      (value "50k")
      (footprint "eagle-import:RESC1005X40N")
      (libsource (lib "eagle-import") (part "R_402"))
    )
    (comp (ref "R106")
      (value "50k")
      (footprint "eagle-import:RESC1005X40N")
      (libsource (lib "eagle-import") (part "R_402"))
    )
    (comp (ref "U25")
      (value "TXS0108PWR")
      (footprint "eagle-import:SOP65P640X110-20N")
      (libsource (lib "eagle-import") (part "TX_0108_TSSOP"))
    )
    (comp (ref "U26")
      (value "TXB0108PWR")
      (footprint "eagle-import:SOP65P640X110-20N")
      (libsource (lib "eagle-import") (part "TX_0108_TSSOP"))
    )
    (comp (ref "U27")
      (value "TXS0108PWR")
      (footprint "eagle-import:SOP65P640X110-20N")
      (libsource (lib "eagle-import") (part "TX_0108_TSSOP"))
    )
    (comp (ref "U28")
      (value "TXB0108PWR")
      (footprint "eagle-import:SOP65P640X110-20N")
      (libsource (lib "eagle-import") (part "TX_0108_TSSOP"))
    )
    (comp (ref "U29")
      (value "FPGA_ARDUINO")
      (footprint "eagle-import:ARDUINOR3")
      (libsource (lib "eagle-import") (part "ARDUINOR3-DIMENSION"))
    )
    (comp (ref "U30")
      (value "TXS0108PWR")
      (footprint "eagle-import:SOP65P640X110-20N")
      (libsource (lib "eagle-import") (part "TX_0108_TSSOP"))
    )
    (comp (ref "U31")
      (value "TXB0108PWR")
      (footprint "eagle-import:SOP65P640X110-20N")
      (libsource (lib "eagle-import") (part "TX_0108_TSSOP"))
    )
    (comp (ref "U32")
      (value "TXS0108PWR")
      (footprint "eagle-import:SOP65P640X110-20N")
      (libsource (lib "eagle-import") (part "TX_0108_TSSOP"))
    )
    (comp (ref "C28")
      (value "100n")
      (footprint "eagle-import:CAPC1005X55N")
      (libsource (lib "eagle-import") (part "C_402"))
    )
    (comp (ref "C29")
      (value "1µ")
      (footprint "eagle-import:CAPC1608X95N")
      (libsource (lib "eagle-import") (part "C_603"))
    )
    (comp (ref "C30")
      (value "1µ")
      (footprint "eagle-import:CAPC1608X95N")
      (libsource (lib "eagle-import") (part "C_603"))
    )
    (comp (ref "C31")
      (value "1µ")
      (footprint "eagle-import:CAPC1608X95N")
      (libsource (lib "eagle-import") (part "C_603"))
    )
    (comp (ref "C32")
      (value "1µ")
      (footprint "eagle-import:CAPC1608X95N")
      (libsource (lib "eagle-import") (part "C_603"))
    )
    (comp (ref "C33")
      (value "100n")
      (footprint "eagle-import:CAPC1608X95N")
      (libsource (lib "eagle-import") (part "C_603"))
    )
    (comp (ref "C34")
      (value "100n")
      (footprint "eagle-import:CAPC1608X95N")
      (libsource (lib "eagle-import") (part "C_603"))
    )
    (comp (ref "C35")
      (value "100n")
      (footprint "eagle-import:CAPC1608X95N")
      (libsource (lib "eagle-import") (part "C_603"))
    )
    (comp (ref "C36")
      (value "100n")
      (footprint "eagle-import:CAPC1608X95N")
      (libsource (lib "eagle-import") (part "C_603"))
    )
    (comp (ref "C37")
      (value "100n")
      (footprint "eagle-import:CAPC1005X55N")
      (libsource (lib "eagle-import") (part "C_402"))
    )
    (comp (ref "C38")
      (value "1µ")
      (footprint "eagle-import:CAPC1608X95N")
      (libsource (lib "eagle-import") (part "C_603"))
    )
    (comp (ref "C39")
      (value "1µ")
      (footprint "eagle-import:CAPC1608X95N")
      (libsource (lib "eagle-import") (part "C_603"))
    )
    (comp (ref "C40")
      (value "1µ")
      (footprint "eagle-import:CAPC1608X95N")
      (libsource (lib "eagle-import") (part "C_603"))
    )
    (comp (ref "C41")
      (value "1µ")
      (footprint "eagle-import:CAPC1608X95N")
      (libsource (lib "eagle-import") (part "C_603"))
    )
    (comp (ref "C42")
      (value "100n")
      (footprint "eagle-import:CAPC1608X95N")
      (libsource (lib "eagle-import") (part "C_603"))
    )
    (comp (ref "C43")
      (value "100n")
      (footprint "eagle-import:CAPC1608X95N")
      (libsource (lib "eagle-import") (part "C_603"))
    )
    (comp (ref "C44")
      (value "100n")
      (footprint "eagle-import:CAPC1608X95N")
      (libsource (lib "eagle-import") (part "C_603"))
    )
    (comp (ref "C45")
      (value "100n")
      (footprint "eagle-import:CAPC1608X95N")
      (libsource (lib "eagle-import") (part "C_603"))
    )
    (comp (ref "C46")
      (value "100n")
      (footprint "eagle-import:CAPC1005X55N")
      (libsource (lib "eagle-import") (part "C_402"))
    )
    (comp (ref "C47")
      (value "1µ")
      (footprint "eagle-import:CAPC1608X95N")
      (libsource (lib "eagle-import") (part "C_603"))
    )
    (comp (ref "C48")
      (value "1µ")
      (footprint "eagle-import:CAPC1608X95N")
      (libsource (lib "eagle-import") (part "C_603"))
    )
    (comp (ref "C49")
      (value "1µ")
      (footprint "eagle-import:CAPC1608X95N")
      (libsource (lib "eagle-import") (part "C_603"))
    )
    (comp (ref "C50")
      (value "1µ")
      (footprint "eagle-import:CAPC1608X95N")
      (libsource (lib "eagle-import") (part "C_603"))
    )
    (comp (ref "C51")
      (value "100n")
      (footprint "eagle-import:CAPC1608X95N")
      (libsource (lib "eagle-import") (part "C_603"))
    )
    (comp (ref "C52")
      (value "100n")
      (footprint "eagle-import:CAPC1608X95N")
      (libsource (lib "eagle-import") (part "C_603"))
    )
    (comp (ref "C53")
      (value "100n")
      (footprint "eagle-import:CAPC1608X95N")
      (libsource (lib "eagle-import") (part "C_603"))
    )
    (comp (ref "C54")
      (value "100n")
      (footprint "eagle-import:CAPC1608X95N")
      (libsource (lib "eagle-import") (part "C_603"))
    )
    (comp (ref "C55")
      (value "100n")
      (footprint "eagle-import:CAPC1608X95N")
      (libsource (lib "eagle-import") (part "C_603"))
    )
    (comp (ref "C56")
      (value "100n")
      (footprint "eagle-import:CAPC1005X55N")
      (libsource (lib "eagle-import") (part "C_402"))
    )
    (comp (ref "C57")
      (value "10n")
      (footprint "eagle-import:CAPC1005X55N")
      (libsource (lib "eagle-import") (part "C_402"))
    )
    (comp (ref "C58")
      (value "100n")
      (footprint "eagle-import:CAPC1005X55N")
      (libsource (lib "eagle-import") (part "C_402"))
    )
    (comp (ref "C59")
      (value "10n")
      (footprint "eagle-import:CAPC1005X55N")
      (libsource (lib "eagle-import") (part "C_402"))
    )
    (comp (ref "C60")
      (value "100n")
      (footprint "eagle-import:CAPC1608X95N")
      (libsource (lib "eagle-import") (part "C_603"))
    )
    (comp (ref "C61")
      (value "100n")
      (footprint "eagle-import:CAPC1608X95N")
      (libsource (lib "eagle-import") (part "C_603"))
    )
    (comp (ref "C62")
      (value "100n")
      (footprint "eagle-import:CAPC1608X95N")
      (libsource (lib "eagle-import") (part "C_603"))
    )
    (comp (ref "C63")
      (value "100n")
      (footprint "eagle-import:CAPC1608X95N")
      (libsource (lib "eagle-import") (part "C_603"))
    )
    (comp (ref "C64")
      (value "100n")
      (footprint "eagle-import:CAPC1608X95N")
      (libsource (lib "eagle-import") (part "C_603"))
    )
    (comp (ref "C65")
      (value "100n")
      (footprint "eagle-import:CAPC1608X95N")
      (libsource (lib "eagle-import") (part "C_603"))
    )
    (comp (ref "C66")
      (value "100n")
      (footprint "eagle-import:CAPC1608X95N")
      (libsource (lib "eagle-import") (part "C_603"))
    )
    (comp (ref "C67")
      (value "100n")
      (footprint "eagle-import:CAPC1005X55N")
      (libsource (lib "eagle-import") (part "C_402"))
    )
    (comp (ref "C68")
      (value "100n")
      (footprint "eagle-import:CAPC1608X95N")
      (libsource (lib "eagle-import") (part "C_603"))
    )
    (comp (ref "C69")
      (value "100n")
      (footprint "eagle-import:CAPC1608X95N")
      (libsource (lib "eagle-import") (part "C_603"))
    )
    (comp (ref "C70")
      (value "100n")
      (footprint "eagle-import:CAPC1608X95N")
      (libsource (lib "eagle-import") (part "C_603"))
    )
    (comp (ref "C71")
      (value "100n")
      (footprint "eagle-import:CAPC1005X55N")
      (libsource (lib "eagle-import") (part "C_402"))
    )
    (comp (ref "C72")
      (value "10n")
      (footprint "eagle-import:CAPC1005X55N")
      (libsource (lib "eagle-import") (part "C_402"))
    )
    (comp (ref "C73")
      (value "100n")
      (footprint "eagle-import:CAPC1005X55N")
      (libsource (lib "eagle-import") (part "C_402"))
    )
    (comp (ref "C74")
      (value "100n")
      (footprint "eagle-import:CAPC1608X95N")
      (libsource (lib "eagle-import") (part "C_603"))
    )
    (comp (ref "C75")
      (value "100n")
      (footprint "eagle-import:CAPC1005X55N")
      (libsource (lib "eagle-import") (part "C_402"))
    )
    (comp (ref "C76")
      (value "100n")
      (footprint "eagle-import:CAPC1005X55N")
      (libsource (lib "eagle-import") (part "C_402"))
    )
    (comp (ref "C77")
      (value "100n")
      (footprint "eagle-import:CAPC1608X95N")
      (libsource (lib "eagle-import") (part "C_603"))
    )
    (comp (ref "C78")
      (value "100n")
      (footprint "eagle-import:CAPC1608X95N")
      (libsource (lib "eagle-import") (part "C_603"))
    )
    (comp (ref "C79")
      (value "100n")
      (footprint "eagle-import:CAPC1608X95N")
      (libsource (lib "eagle-import") (part "C_603"))
    )
    (comp (ref "C80")
      (value "100n")
      (footprint "eagle-import:CAPC1608X95N")
      (libsource (lib "eagle-import") (part "C_603"))
    )
    (comp (ref "C81")
      (value "1µ")
      (footprint "eagle-import:CAPC1608X95N")
      (libsource (lib "eagle-import") (part "C_603"))
    )
    (comp (ref "C82")
      (value "1µ")
      (footprint "eagle-import:CAPC1608X95N")
      (libsource (lib "eagle-import") (part "C_603"))
    )
    (comp (ref "C83")
      (value "1µ")
      (footprint "eagle-import:CAPC1608X95N")
      (libsource (lib "eagle-import") (part "C_603"))
    )
    (comp (ref "C84")
      (value "1µ")
      (footprint "eagle-import:CAPC1608X95N")
      (libsource (lib "eagle-import") (part "C_603"))
    )
    (comp (ref "C85")
      (value "100n")
      (footprint "eagle-import:CAPC1608X95N")
      (libsource (lib "eagle-import") (part "C_603"))
    )
    (comp (ref "C86")
      (value "100n")
      (footprint "eagle-import:CAPC1608X95N")
      (libsource (lib "eagle-import") (part "C_603"))
    )
    (comp (ref "C87")
      (value "100n")
      (footprint "eagle-import:CAPC1608X95N")
      (libsource (lib "eagle-import") (part "C_603"))
    )
    (comp (ref "C88")
      (value "100n")
      (footprint "eagle-import:CAPC1608X95N")
      (libsource (lib "eagle-import") (part "C_603"))
    )
    (comp (ref "C89")
      (value "100n")
      (footprint "eagle-import:CAPC1005X55N")
      (libsource (lib "eagle-import") (part "C_402"))
    )
    (comp (ref "C90")
      (value "100n")
      (footprint "eagle-import:CAPC1005X55N")
      (libsource (lib "eagle-import") (part "C_402"))
    )
    (comp (ref "CON8")
      (value "M0")
      (footprint "eagle-import:PHOENIX381P900X920-2N")
      (libsource (lib "eagle-import") (part "CON2_3.81"))
    )
    (comp (ref "CON9")
      (value "M3")
      (footprint "eagle-import:PHOENIX381P900X920-2N")
      (libsource (lib "eagle-import") (part "CON2_3.81"))
    )
    (comp (ref "CON10")
      (value "M5")
      (footprint "eagle-import:PHOENIX381P900X920-2N")
      (libsource (lib "eagle-import") (part "CON2_3.81"))
    )
    (comp (ref "CON11")
      (value "M2")
      (footprint "eagle-import:PHOENIX381P900X920-2N")
      (libsource (lib "eagle-import") (part "CON2_3.81"))
    )
    (comp (ref "CON12")
      (value "M4")
      (footprint "eagle-import:PHOENIX381P900X920-2N")
      (libsource (lib "eagle-import") (part "CON2_3.81"))
    )
    (comp (ref "CON13")
      (value "M1")
      (footprint "eagle-import:PHOENIX381P900X920-2N")
      (libsource (lib "eagle-import") (part "CON2_3.81"))
    )
    (comp (ref "J4")
      (value "0")
      (footprint "eagle-import:JUMC1608X50AN")
      (libsource (lib "eagle-import") (part "JUMP_603"))
    )
    (comp (ref "J5")
      (value "nc")
      (footprint "eagle-import:JUMC1608X50AN")
      (libsource (lib "eagle-import") (part "JUMP_603"))
    )
    (comp (ref "J6")
      (value "0")
      (footprint "eagle-import:JUMC1608X50AN")
      (libsource (lib "eagle-import") (part "JUMP_603"))
    )
    (comp (ref "J7")
      (value "nc")
      (footprint "eagle-import:JUMC1608X50AN")
      (libsource (lib "eagle-import") (part "JUMP_603"))
    )
    (comp (ref "J8")
      (value "0")
      (footprint "eagle-import:JUMC1005X50N")
      (libsource (lib "eagle-import") (part "JUMP_402"))
    )
    (comp (ref "J9")
      (value "0")
      (footprint "eagle-import:JUMC1005X50N")
      (libsource (lib "eagle-import") (part "JUMP_402"))
    )
    (comp (ref "J10")
      (value "0")
      (footprint "eagle-import:JUMC1005X50N")
      (libsource (lib "eagle-import") (part "JUMP_402"))
    )
    (comp (ref "J11")
      (value "0")
      (footprint "eagle-import:JUMC1005X50N")
      (libsource (lib "eagle-import") (part "JUMP_402"))
    )
    (comp (ref "J12")
      (value "0")
      (footprint "eagle-import:JUMC1005X50N")
      (libsource (lib "eagle-import") (part "JUMP_402"))
    )
    (comp (ref "J13")
      (value "0")
      (footprint "eagle-import:JUMC1005X50N")
      (libsource (lib "eagle-import") (part "JUMP_402"))
    )
    (comp (ref "J14")
      (value "0")
      (footprint "eagle-import:JUMC1005X50N")
      (libsource (lib "eagle-import") (part "JUMP_402"))
    )
    (comp (ref "J15")
      (value "0")
      (footprint "eagle-import:JUMC1005X50N")
      (libsource (lib "eagle-import") (part "JUMP_402"))
    )
    (comp (ref "J16")
      (value "0")
      (footprint "eagle-import:JUMC1005X50N")
      (libsource (lib "eagle-import") (part "JUMP_402"))
    )
    (comp (ref "J17")
      (value "0")
      (footprint "eagle-import:JUMC1005X50N")
      (libsource (lib "eagle-import") (part "JUMP_402"))
    )
    (comp (ref "J18")
      (value "0")
      (footprint "eagle-import:JUMC1005X50N")
      (libsource (lib "eagle-import") (part "JUMP_402"))
    )
    (comp (ref "J19")
      (value "0")
      (footprint "eagle-import:JUMC1005X50N")
      (libsource (lib "eagle-import") (part "JUMP_402"))
    )
    (comp (ref "J20")
      (value "0")
      (footprint "eagle-import:JUMC1005X50N")
      (libsource (lib "eagle-import") (part "JUMP_402"))
    )
    (comp (ref "J21")
      (value "0")
      (footprint "eagle-import:JUMC1005X50N")
      (libsource (lib "eagle-import") (part "JUMP_402"))
    )
    (comp (ref "J22")
      (value "0")
      (footprint "eagle-import:JUMC1005X50N")
      (libsource (lib "eagle-import") (part "JUMP_402"))
    )
    (comp (ref "J23")
      (value "0")
      (footprint "eagle-import:JUMC1005X50N")
      (libsource (lib "eagle-import") (part "JUMP_402"))
    )
    (comp (ref "L1")
      (value "SRN2512-R24M")
      (footprint "eagle-import:INDC2520X120N")
      (libsource (lib "eagle-import") (part "INDUCTANCE_2520"))
    )
    (comp (ref "L2")
      (value "SRN2512-R24M")
      (footprint "eagle-import:INDC2520X120N")
      (libsource (lib "eagle-import") (part "INDUCTANCE_2520"))
    )
    (comp (ref "L3")
      (value "SRN2512-R24M")
      (footprint "eagle-import:INDC2520X120N")
      (libsource (lib "eagle-import") (part "INDUCTANCE_2520"))
    )
    (comp (ref "L4")
      (value "SRN2512-R24M")
      (footprint "eagle-import:INDC2520X120N")
      (libsource (lib "eagle-import") (part "INDUCTANCE_2520"))
    )
    (comp (ref "L5")
      (value "SRN2512-R24M")
      (footprint "eagle-import:INDC2520X120N")
      (libsource (lib "eagle-import") (part "INDUCTANCE_2520"))
    )
    (comp (ref "L6")
      (value "SRN2512-R24M")
      (footprint "eagle-import:INDC2520X120N")
      (libsource (lib "eagle-import") (part "INDUCTANCE_2520"))
    )
    (comp (ref "L7")
      (value "SRN2512-R24M")
      (footprint "eagle-import:INDC2520X120N")
      (libsource (lib "eagle-import") (part "INDUCTANCE_2520"))
    )
    (comp (ref "L8")
      (value "SRN2512-R24M")
      (footprint "eagle-import:INDC2520X120N")
      (libsource (lib "eagle-import") (part "INDUCTANCE_2520"))
    )
    (comp (ref "R21")
      (value "100")
      (footprint "eagle-import:RESC1005X40N")
      (libsource (lib "eagle-import") (part "R_402"))
    )
    (comp (ref "R22")
      (value "100")
      (footprint "eagle-import:RESC1005X40N")
      (libsource (lib "eagle-import") (part "R_402"))
    )
    (comp (ref "R23")
      (value "ULR15S-R0055FT2")
      (footprint "eagle-import:RESC_ULR15S-R0055FT2")
      (libsource (lib "eagle-import") (part "R_ULR15S-R0055FT2"))
    )
    (comp (ref "R24")
      (value "ULR15S-R0055FT2")
      (footprint "eagle-import:RESC_ULR15S-R0055FT2")
      (libsource (lib "eagle-import") (part "R_ULR15S-R0055FT2"))
    )
    (comp (ref "R25")
      (value "ULR15S-R0055FT2")
      (footprint "eagle-import:RESC_ULR15S-R0055FT2")
      (libsource (lib "eagle-import") (part "R_ULR15S-R0055FT2"))
    )
    (comp (ref "R26")
      (value "30k")
      (footprint "eagle-import:RESC1005X40N")
      (libsource (lib "eagle-import") (part "R_402"))
    )
    (comp (ref "R27")
      (value "100")
      (footprint "eagle-import:RESC1005X40N")
      (libsource (lib "eagle-import") (part "R_402"))
    )
    (comp (ref "R28")
      (value "30k")
      (footprint "eagle-import:RESC1005X40N")
      (libsource (lib "eagle-import") (part "R_402"))
    )
    (comp (ref "R29")
      (value "ULR15S-R0055FT2")
      (footprint "eagle-import:RESC_ULR15S-R0055FT2")
      (libsource (lib "eagle-import") (part "R_ULR15S-R0055FT2"))
    )
    (comp (ref "R30")
      (value "30k")
      (footprint "eagle-import:RESC1005X40N")
      (libsource (lib "eagle-import") (part "R_402"))
    )
    (comp (ref "R31")
      (value "100")
      (footprint "eagle-import:RESC1005X40N")
      (libsource (lib "eagle-import") (part "R_402"))
    )
    (comp (ref "R32")
      (value "ULR15S-R0055FT2")
      (footprint "eagle-import:RESC_ULR15S-R0055FT2")
      (libsource (lib "eagle-import") (part "R_ULR15S-R0055FT2"))
    )
    (comp (ref "R33")
      (value "30k")
      (footprint "eagle-import:RESC1005X40N")
      (libsource (lib "eagle-import") (part "R_402"))
    )
    (comp (ref "R34")
      (value "100")
      (footprint "eagle-import:RESC1005X40N")
      (libsource (lib "eagle-import") (part "R_402"))
    )
    (comp (ref "U7")
      (value "INA240-A2")
      (footprint "eagle-import:TSSOP")
      (libsource (lib "eagle-import") (part "INA240-TSSOP"))
    )
    (comp (ref "U8")
      (value "INA240-A2")
      (footprint "eagle-import:TSSOP")
      (libsource (lib "eagle-import") (part "INA240-TSSOP"))
    )
    (comp (ref "U9")
      (value "DRV8432")
      (footprint "eagle-import:R-PDSO-G36")
      (libsource (lib "eagle-import") (part "DRV84X2_DRV8432"))
    )
    (comp (ref "U10")
      (value "DRV8432")
      (footprint "eagle-import:R-PDSO-G36")
      (libsource (lib "eagle-import") (part "DRV84X2_DRV8432"))
    )
    (comp (ref "U11")
      (value "DRV8432")
      (footprint "eagle-import:R-PDSO-G36")
      (libsource (lib "eagle-import") (part "DRV84X2_DRV8432"))
    )
    (comp (ref "U12")
      (value "INA240-A2")
      (footprint "eagle-import:TSSOP")
      (libsource (lib "eagle-import") (part "INA240-TSSOP"))
    )
    (comp (ref "U13")
      (value "INA240-A2")
      (footprint "eagle-import:TSSOP")
      (libsource (lib "eagle-import") (part "INA240-TSSOP"))
    )
    (comp (ref "U14")
      (value "DRV8432")
      (footprint "eagle-import:R-PDSO-G36")
      (libsource (lib "eagle-import") (part "DRV84X2_DRV8432"))
    )
    (comp (ref "U15")
      (value "INA240-A2")
      (footprint "eagle-import:TSSOP")
      (libsource (lib "eagle-import") (part "INA240-TSSOP"))
    )
    (comp (ref "C100")
      (value "100n")
      (footprint "eagle-import:CAPC1005X55N")
      (libsource (lib "eagle-import") (part "C_402"))
    )
    (comp (ref "C101")
      (value "100n")
      (footprint "eagle-import:CAPC1005X55N")
      (libsource (lib "eagle-import") (part "C_402"))
    )
    (comp (ref "C102")
      (value "100n")
      (footprint "eagle-import:CAPC1005X55N")
      (libsource (lib "eagle-import") (part "C_402"))
    )
    (comp (ref "C103")
      (value "100n")
      (footprint "eagle-import:CAPC1005X55N")
      (libsource (lib "eagle-import") (part "C_402"))
    )
    (comp (ref "C104")
      (value "1n")
      (footprint "eagle-import:CAPC1005X55N")
      (libsource (lib "eagle-import") (part "C_402"))
    )
    (comp (ref "C105")
      (value "1n")
      (footprint "eagle-import:CAPC1005X55N")
      (libsource (lib "eagle-import") (part "C_402"))
    )
    (comp (ref "C106")
      (value "100n")
      (footprint "eagle-import:CAPC1005X55N")
      (libsource (lib "eagle-import") (part "C_402"))
    )
    (comp (ref "C107")
      (value "100n")
      (footprint "eagle-import:CAPC1005X55N")
      (libsource (lib "eagle-import") (part "C_402"))
    )
    (comp (ref "C108")
      (value "NC")
      (footprint "eagle-import:CAPC1005X55N")
      (libsource (lib "eagle-import") (part "C_402"))
    )
    (comp (ref "C109")
      (value "100n")
      (footprint "eagle-import:CAPC1005X55N")
      (libsource (lib "eagle-import") (part "C_402"))
    )
    (comp (ref "C110")
      (value "1n")
      (footprint "eagle-import:CAPC1005X55N")
      (libsource (lib "eagle-import") (part "C_402"))
    )
    (comp (ref "C111")
      (value "1n")
      (footprint "eagle-import:CAPC1005X55N")
      (libsource (lib "eagle-import") (part "C_402"))
    )
    (comp (ref "C112")
      (value "100n")
      (footprint "eagle-import:CAPC1005X55N")
      (libsource (lib "eagle-import") (part "C_402"))
    )
    (comp (ref "C113")
      (value "100n")
      (footprint "eagle-import:CAPC1005X55N")
      (libsource (lib "eagle-import") (part "C_402"))
    )
    (comp (ref "C114")
      (value "100n")
      (footprint "eagle-import:CAPC1005X55N")
      (libsource (lib "eagle-import") (part "C_402"))
    )
    (comp (ref "C115")
      (value "100n")
      (footprint "eagle-import:CAPC1005X55N")
      (libsource (lib "eagle-import") (part "C_402"))
    )
    (comp (ref "C116")
      (value "100n")
      (footprint "eagle-import:CAPC1005X55N")
      (libsource (lib "eagle-import") (part "C_402"))
    )
    (comp (ref "C117")
      (value "100n")
      (footprint "eagle-import:CAPC1005X55N")
      (libsource (lib "eagle-import") (part "C_402"))
    )
    (comp (ref "C118")
      (value "100n")
      (footprint "eagle-import:CAPC1005X55N")
      (libsource (lib "eagle-import") (part "C_402"))
    )
    (comp (ref "C119")
      (value "100p")
      (footprint "eagle-import:CAPC1005X55N")
      (libsource (lib "eagle-import") (part "C_402"))
    )
    (comp (ref "C120")
      (value "100p")
      (footprint "eagle-import:CAPC1005X55N")
      (libsource (lib "eagle-import") (part "C_402"))
    )
    (comp (ref "C121")
      (value "100p")
      (footprint "eagle-import:CAPC1005X55N")
      (libsource (lib "eagle-import") (part "C_402"))
    )
    (comp (ref "C122")
      (value "100n")
      (footprint "eagle-import:CAPC1005X55N")
      (libsource (lib "eagle-import") (part "C_402"))
    )
    (comp (ref "C123")
      (value "100n")
      (footprint "eagle-import:CAPC1005X55N")
      (libsource (lib "eagle-import") (part "C_402"))
    )
    (comp (ref "C124")
      (value "100n")
      (footprint "eagle-import:CAPC1005X55N")
      (libsource (lib "eagle-import") (part "C_402"))
    )
    (comp (ref "C125")
      (value "100n")
      (footprint "eagle-import:CAPC1005X55N")
      (libsource (lib "eagle-import") (part "C_402"))
    )
    (comp (ref "C126")
      (value "100p")
      (footprint "eagle-import:CAPC1005X55N")
      (libsource (lib "eagle-import") (part "C_402"))
    )
    (comp (ref "C127")
      (value "100p")
      (footprint "eagle-import:CAPC1005X55N")
      (libsource (lib "eagle-import") (part "C_402"))
    )
    (comp (ref "C128")
      (value "100p")
      (footprint "eagle-import:CAPC1005X55N")
      (libsource (lib "eagle-import") (part "C_402"))
    )
    (comp (ref "C129")
      (value "100n")
      (footprint "eagle-import:CAPC1005X55N")
      (libsource (lib "eagle-import") (part "C_402"))
    )
    (comp (ref "C130")
      (value "100n")
      (footprint "eagle-import:CAPC1005X55N")
      (libsource (lib "eagle-import") (part "C_402"))
    )
    (comp (ref "C131")
      (value "100n")
      (footprint "eagle-import:CAPC1005X55N")
      (libsource (lib "eagle-import") (part "C_402"))
    )
    (comp (ref "C132")
      (value "100n")
      (footprint "eagle-import:CAPC1005X55N")
      (libsource (lib "eagle-import") (part "C_402"))
    )
    (comp (ref "C133")
      (value "100n")
      (footprint "eagle-import:CAPC1005X55N")
      (libsource (lib "eagle-import") (part "C_402"))
    )
    (comp (ref "C134")
      (value "nc")
      (footprint "eagle-import:CAPC1005X55N")
      (libsource (lib "eagle-import") (part "C_402"))
    )
    (comp (ref "C135")
      (value "100n")
      (footprint "eagle-import:CAPC1005X55N")
      (libsource (lib "eagle-import") (part "C_402"))
    )
    (comp (ref "C136")
      (value "100n")
      (footprint "eagle-import:CAPC1005X55N")
      (libsource (lib "eagle-import") (part "C_402"))
    )
    (comp (ref "C137")
      (value "nc")
      (footprint "eagle-import:CAPC1005X55N")
      (libsource (lib "eagle-import") (part "C_402"))
    )
    (comp (ref "CON18")
      (value "UART0")
      (footprint "eagle-import:CON254P1270X400-5S")
      (libsource (lib "eagle-import") (part "CON5_2.54S"))
    )
    (comp (ref "CON19")
      (value "QEI1")
      (footprint "eagle-import:CON254P1270X400-5S")
      (libsource (lib "eagle-import") (part "CON5_2.54S"))
    )
    (comp (ref "CON20")
      (value "AN0")
      (footprint "eagle-import:CON254P762X400-3SMT")
      (libsource (lib "eagle-import") (part "CON3_SMT"))
    )
    (comp (ref "CON21")
      (value "S0")
      (footprint "eagle-import:CON254P762X400-3SMT")
      (libsource (lib "eagle-import") (part "CON3_SMT"))
    )
    (comp (ref "CON22")
      (value "IO0")
      (footprint "eagle-import:CON254P762X400-3SMT")
      (libsource (lib "eagle-import") (part "CON3_SMT"))
    )
    (comp (ref "CON23")
      (value "AN1")
      (footprint "eagle-import:CON254P762X400-3SMT")
      (libsource (lib "eagle-import") (part "CON3_SMT"))
    )
    (comp (ref "CON24")
      (value "S1")
      (footprint "eagle-import:CON254P762X400-3SMT")
      (libsource (lib "eagle-import") (part "CON3_SMT"))
    )
    (comp (ref "CON25")
      (value "IO1")
      (footprint "eagle-import:CON254P762X400-3SMT")
      (libsource (lib "eagle-import") (part "CON3_SMT"))
    )
    (comp (ref "CON26")
      (value "UART1")
      (footprint "eagle-import:CON254P1270X400-5S")
      (libsource (lib "eagle-import") (part "CON5_2.54S"))
    )
    (comp (ref "CON27")
      (value "QEI0")
      (footprint "eagle-import:CON254P1270X400-5S")
      (libsource (lib "eagle-import") (part "CON5_2.54S"))
    )
    (comp (ref "CON28")
      (value "AN2")
      (footprint "eagle-import:CON254P762X400-3SMT")
      (libsource (lib "eagle-import") (part "CON3_SMT"))
    )
    (comp (ref "CON29")
      (value "S2")
      (footprint "eagle-import:CON254P762X400-3SMT")
      (libsource (lib "eagle-import") (part "CON3_SMT"))
    )
    (comp (ref "CON30")
      (value "IO2")
      (footprint "eagle-import:CON254P762X400-3SMT")
      (libsource (lib "eagle-import") (part "CON3_SMT"))
    )
    (comp (ref "CON31")
      (value "TELEM")
      (footprint "eagle-import:CON254P1270X400-5S")
      (libsource (lib "eagle-import") (part "CON5_2.54S"))
    )
    (comp (ref "CON32")
      (value "QEI3")
      (footprint "eagle-import:CON254P1270X400-5S")
      (libsource (lib "eagle-import") (part "CON5_2.54S"))
    )
    (comp (ref "CON33")
      (value "AN3")
      (footprint "eagle-import:CON254P762X400-3SMT")
      (libsource (lib "eagle-import") (part "CON3_SMT"))
    )
    (comp (ref "CON34")
      (value "S3")
      (footprint "eagle-import:CON254P762X400-3SMT")
      (libsource (lib "eagle-import") (part "CON3_SMT"))
    )
    (comp (ref "CON35")
      (value "IO3")
      (footprint "eagle-import:CON254P762X400-3SMT")
      (libsource (lib "eagle-import") (part "CON3_SMT"))
    )
    (comp (ref "CON36")
      (value "BALISE")
      (footprint "eagle-import:CON254P1270X400-5S")
      (libsource (lib "eagle-import") (part "CON5_2.54S"))
    )
    (comp (ref "CON37")
      (value "AN4")
      (footprint "eagle-import:CON254P762X400-3SMT")
      (libsource (lib "eagle-import") (part "CON3_SMT"))
    )
    (comp (ref "CON38")
      (value "S4")
      (footprint "eagle-import:CON254P762X400-3SMT")
      (libsource (lib "eagle-import") (part "CON3_SMT"))
    )
    (comp (ref "CON39")
      (value "IO4")
      (footprint "eagle-import:CON254P762X400-3SMT")
      (libsource (lib "eagle-import") (part "CON3_SMT"))
    )
    (comp (ref "CON40")
      (value "SPI0")
      (footprint "eagle-import:CON254P1524X400-6N-S")
      (libsource (lib "eagle-import") (part "CON6_2.54S"))
    )
    (comp (ref "CON41")
      (value "QEI2")
      (footprint "eagle-import:CON254P1270X400-5S")
      (libsource (lib "eagle-import") (part "CON5_2.54S"))
    )
    (comp (ref "CON42")
      (value "AN5")
      (footprint "eagle-import:CON254P762X400-3SMT")
      (libsource (lib "eagle-import") (part "CON3_SMT"))
    )
    (comp (ref "CON43")
      (value "S5")
      (footprint "eagle-import:CON254P762X400-3SMT")
      (libsource (lib "eagle-import") (part "CON3_SMT"))
    )
    (comp (ref "CON44")
      (value "IO5")
      (footprint "eagle-import:CON254P762X400-3SMT")
      (libsource (lib "eagle-import") (part "CON3_SMT"))
    )
    (comp (ref "CON45")
      (value "SPI1")
      (footprint "eagle-import:CON254P1524X400-6N-S")
      (libsource (lib "eagle-import") (part "CON6_2.54S"))
    )
    (comp (ref "CON46")
      (value "AN6")
      (footprint "eagle-import:CON254P762X400-3SMT")
      (libsource (lib "eagle-import") (part "CON3_SMT"))
    )
    (comp (ref "CON47")
      (value "S6")
      (footprint "eagle-import:CON254P762X400-3SMT")
      (libsource (lib "eagle-import") (part "CON3_SMT"))
    )
    (comp (ref "CON48")
      (value "IO6")
      (footprint "eagle-import:CON254P762X400-3SMT")
      (libsource (lib "eagle-import") (part "CON3_SMT"))
    )
    (comp (ref "CON49")
      (value "I2C0")
      (footprint "eagle-import:CON254P1270X400-5S")
      (libsource (lib "eagle-import") (part "CON5_2.54S"))
    )
    (comp (ref "CON50")
      (value "AN7")
      (footprint "eagle-import:CON254P762X400-3SMT")
      (libsource (lib "eagle-import") (part "CON3_SMT"))
    )
    (comp (ref "CON51")
      (value "S7")
      (footprint "eagle-import:CON254P762X400-3SMT")
      (libsource (lib "eagle-import") (part "CON3_SMT"))
    )
    (comp (ref "CON52")
      (value "IO7")
      (footprint "eagle-import:CON254P762X400-3SMT")
      (libsource (lib "eagle-import") (part "CON3_SMT"))
    )
    (comp (ref "CON53")
      (value "I2C1")
      (footprint "eagle-import:CON254P1270X400-5S")
      (libsource (lib "eagle-import") (part "CON5_2.54S"))
    )
    (comp (ref "R39")
      (value "1k")
      (footprint "eagle-import:RESC1005X40N")
      (libsource (lib "eagle-import") (part "R_402"))
    )
    (comp (ref "R40")
      (value "1k")
      (footprint "eagle-import:RESC1005X40N")
      (libsource (lib "eagle-import") (part "R_402"))
    )
    (comp (ref "R41")
      (value "10k")
      (footprint "eagle-import:RESC1005X40N")
      (libsource (lib "eagle-import") (part "R_402"))
    )
    (comp (ref "R42")
      (value "1k")
      (footprint "eagle-import:RESC1005X40N")
      (libsource (lib "eagle-import") (part "R_402"))
    )
    (comp (ref "R43")
      (value "10k")
      (footprint "eagle-import:RESC1005X40N")
      (libsource (lib "eagle-import") (part "R_402"))
    )
    (comp (ref "R44")
      (value "20k")
      (footprint "eagle-import:RESC1005X40N")
      (libsource (lib "eagle-import") (part "R_402"))
    )
    (comp (ref "R45")
      (value "0.01")
      (footprint "eagle-import:RESC1608X50AN")
      (libsource (lib "eagle-import") (part "R_603"))
    )
    (comp (ref "R46")
      (value "10k")
      (footprint "eagle-import:RESC1005X40N")
      (libsource (lib "eagle-import") (part "R_402"))
    )
    (comp (ref "R47")
      (value "33")
      (footprint "eagle-import:RESC1005X40N")
      (libsource (lib "eagle-import") (part "R_402"))
    )
    (comp (ref "R48")
      (value "10k")
      (footprint "eagle-import:RESC1005X40N")
      (libsource (lib "eagle-import") (part "R_402"))
    )
    (comp (ref "R49")
      (value "20k")
      (footprint "eagle-import:RESC1005X40N")
      (libsource (lib "eagle-import") (part "R_402"))
    )
    (comp (ref "R50")
      (value "1k")
      (footprint "eagle-import:RESC1005X40N")
      (libsource (lib "eagle-import") (part "R_402"))
    )
    (comp (ref "R51")
      (value "1k")
      (footprint "eagle-import:RESC1005X40N")
      (libsource (lib "eagle-import") (part "R_402"))
    )
    (comp (ref "R52")
      (value "0.01")
      (footprint "eagle-import:RESC1608X50AN")
      (libsource (lib "eagle-import") (part "R_603"))
    )
    (comp (ref "R53")
      (value "10k")
      (footprint "eagle-import:RESC1005X40N")
      (libsource (lib "eagle-import") (part "R_402"))
    )
    (comp (ref "R54")
      (value "1k")
      (footprint "eagle-import:RESC1005X40N")
      (libsource (lib "eagle-import") (part "R_402"))
    )
    (comp (ref "R55")
      (value "10k")
      (footprint "eagle-import:RESC1005X40N")
      (libsource (lib "eagle-import") (part "R_402"))
    )
    (comp (ref "R56")
      (value "20k")
      (footprint "eagle-import:RESC1005X40N")
      (libsource (lib "eagle-import") (part "R_402"))
    )
    (comp (ref "R57")
      (value "0.01")
      (footprint "eagle-import:RESC1608X50AN")
      (libsource (lib "eagle-import") (part "R_603"))
    )
    (comp (ref "R58")
      (value "100")
      (footprint "eagle-import:RESC1005X40N")
      (libsource (lib "eagle-import") (part "R_402"))
    )
    (comp (ref "R59")
      (value "10k")
      (footprint "eagle-import:RESC1005X40N")
      (libsource (lib "eagle-import") (part "R_402"))
    )
    (comp (ref "R60")
      (value "1k")
      (footprint "eagle-import:RESC1005X40N")
      (libsource (lib "eagle-import") (part "R_402"))
    )
    (comp (ref "R61")
      (value "100")
      (footprint "eagle-import:RESC1005X40N")
      (libsource (lib "eagle-import") (part "R_402"))
    )
    (comp (ref "R62")
      (value "100")
      (footprint "eagle-import:RESC1005X40N")
      (libsource (lib "eagle-import") (part "R_402"))
    )
    (comp (ref "R63")
      (value "10k")
      (footprint "eagle-import:RESC1005X40N")
      (libsource (lib "eagle-import") (part "R_402"))
    )
    (comp (ref "R64")
      (value "20k")
      (footprint "eagle-import:RESC1005X40N")
      (libsource (lib "eagle-import") (part "R_402"))
    )
    (comp (ref "R65")
      (value "0.01")
      (footprint "eagle-import:RESC1608X50AN")
      (libsource (lib "eagle-import") (part "R_603"))
    )
    (comp (ref "R66")
      (value "10k")
      (footprint "eagle-import:RESC1005X40N")
      (libsource (lib "eagle-import") (part "R_402"))
    )
    (comp (ref "R67")
      (value "1k")
      (footprint "eagle-import:RESC1005X40N")
      (libsource (lib "eagle-import") (part "R_402"))
    )
    (comp (ref "R68")
      (value "10k")
      (footprint "eagle-import:RESC1005X40N")
      (libsource (lib "eagle-import") (part "R_402"))
    )
    (comp (ref "R69")
      (value "20k")
      (footprint "eagle-import:RESC1005X40N")
      (libsource (lib "eagle-import") (part "R_402"))
    )
    (comp (ref "R70")
      (value "0.01")
      (footprint "eagle-import:RESC1608X50AN")
      (libsource (lib "eagle-import") (part "R_603"))
    )
    (comp (ref "R71")
      (value "100")
      (footprint "eagle-import:RESC1005X40N")
      (libsource (lib "eagle-import") (part "R_402"))
    )
    (comp (ref "R72")
      (value "100")
      (footprint "eagle-import:RESC1005X40N")
      (libsource (lib "eagle-import") (part "R_402"))
    )
    (comp (ref "R73")
      (value "100")
      (footprint "eagle-import:RESC1005X40N")
      (libsource (lib "eagle-import") (part "R_402"))
    )
    (comp (ref "R74")
      (value "10k")
      (footprint "eagle-import:RESC1005X40N")
      (libsource (lib "eagle-import") (part "R_402"))
    )
    (comp (ref "R75")
      (value "1k")
      (footprint "eagle-import:RESC1005X40N")
      (libsource (lib "eagle-import") (part "R_402"))
    )
    (comp (ref "R76")
      (value "10k")
      (footprint "eagle-import:RESC1005X40N")
      (libsource (lib "eagle-import") (part "R_402"))
    )
    (comp (ref "R77")
      (value "20k")
      (footprint "eagle-import:RESC1005X40N")
      (libsource (lib "eagle-import") (part "R_402"))
    )
    (comp (ref "R78")
      (value "0.01")
      (footprint "eagle-import:RESC1608X50AN")
      (libsource (lib "eagle-import") (part "R_603"))
    )
    (comp (ref "R79")
      (value "10k")
      (footprint "eagle-import:RESC1005X40N")
      (libsource (lib "eagle-import") (part "R_402"))
    )
    (comp (ref "R80")
      (value "33")
      (footprint "eagle-import:RESC1005X40N")
      (libsource (lib "eagle-import") (part "R_402"))
    )
    (comp (ref "R81")
      (value "10k")
      (footprint "eagle-import:RESC1005X40N")
      (libsource (lib "eagle-import") (part "R_402"))
    )
    (comp (ref "R82")
      (value "20k")
      (footprint "eagle-import:RESC1005X40N")
      (libsource (lib "eagle-import") (part "R_402"))
    )
    (comp (ref "R83")
      (value "0.01")
      (footprint "eagle-import:RESC1608X50AN")
      (libsource (lib "eagle-import") (part "R_603"))
    )
    (comp (ref "R84")
      (value "10k")
      (footprint "eagle-import:RESC1005X40N")
      (libsource (lib "eagle-import") (part "R_402"))
    )
    (comp (ref "R85")
      (value "33")
      (footprint "eagle-import:RESC1005X40N")
      (libsource (lib "eagle-import") (part "R_402"))
    )
    (comp (ref "R86")
      (value "10k")
      (footprint "eagle-import:RESC1005X40N")
      (libsource (lib "eagle-import") (part "R_402"))
    )
    (comp (ref "R87")
      (value "20k")
      (footprint "eagle-import:RESC1005X40N")
      (libsource (lib "eagle-import") (part "R_402"))
    )
    (comp (ref "R88")
      (value "0.01")
      (footprint "eagle-import:RESC1608X50AN")
      (libsource (lib "eagle-import") (part "R_603"))
    )
    (comp (ref "C1")
      (value "100n")
      (footprint "eagle-import:CAPC1005X55N")
      (libsource (lib "eagle-import") (part "C_402"))
    )
    (comp (ref "C2")
      (value "470u")
      (footprint "eagle-import:CAPAE835X1020N")
      (libsource (lib "eagle-import") (part "CPOL"))
    )
    (comp (ref "C3")
      (value "100n")
      (footprint "eagle-import:CAPC1005X55N")
      (libsource (lib "eagle-import") (part "C_402"))
    )
    (comp (ref "C4")
      (value "100p")
      (footprint "eagle-import:CAPC1005X55N")
      (libsource (lib "eagle-import") (part "C_402"))
    )
    (comp (ref "C5")
      (value "100n")
      (footprint "eagle-import:CAPC1005X55N")
      (libsource (lib "eagle-import") (part "C_402"))
    )
    (comp (ref "C6")
      (value "470u")
      (footprint "eagle-import:CAPAE835X1020N")
      (libsource (lib "eagle-import") (part "CPOL"))
    )
    (comp (ref "C7")
      (value "100n")
      (footprint "eagle-import:CAPC1005X55N")
      (libsource (lib "eagle-import") (part "C_402"))
    )
    (comp (ref "C8")
      (value "100n")
      (footprint "eagle-import:CAPC1005X55N")
      (libsource (lib "eagle-import") (part "C_402"))
    )
    (comp (ref "C9")
      (value "100n")
      (footprint "eagle-import:CAPC1005X55N")
      (libsource (lib "eagle-import") (part "C_402"))
    )
    (comp (ref "C10")
      (value "100n")
      (footprint "eagle-import:CAPC1005X55N")
      (libsource (lib "eagle-import") (part "C_402"))
    )
    (comp (ref "C11")
      (value "100n")
      (footprint "eagle-import:CAPC2013X100N")
      (libsource (lib "eagle-import") (part "C_805"))
    )
    (comp (ref "C12")
      (value "220u")
      (footprint "eagle-import:CAPAE835X1020N")
      (libsource (lib "eagle-import") (part "CPOL"))
    )
    (comp (ref "C13")
      (value "10u")
      (footprint "eagle-import:CAPC2013X100N")
      (libsource (lib "eagle-import") (part "C_805"))
    )
    (comp (ref "C14")
      (value "10u")
      (footprint "eagle-import:CAPC2013X100N")
      (libsource (lib "eagle-import") (part "C_805"))
    )
    (comp (ref "C15")
      (value "470u")
      (footprint "eagle-import:CAPAE835X1020N")
      (libsource (lib "eagle-import") (part "CPOL"))
    )
    (comp (ref "C16")
      (value "10u")
      (footprint "eagle-import:CAPC2013X100N")
      (libsource (lib "eagle-import") (part "C_805"))
    )
    (comp (ref "C17")
      (value "10u")
      (footprint "eagle-import:CAPC2013X100N")
      (libsource (lib "eagle-import") (part "C_805"))
    )
    (comp (ref "C18")
      (value "470u")
      (footprint "eagle-import:CAPAE835X1020N")
      (libsource (lib "eagle-import") (part "CPOL"))
    )
    (comp (ref "C19")
      (value "22n")
      (footprint "eagle-import:CAPC1005X55N")
      (libsource (lib "eagle-import") (part "C_402"))
    )
    (comp (ref "C20")
      (value "10u")
      (footprint "eagle-import:CAPC2013X100N")
      (libsource (lib "eagle-import") (part "C_805"))
    )
    (comp (ref "C21")
      (value "10u")
      (footprint "eagle-import:CAPC2013X100N")
      (libsource (lib "eagle-import") (part "C_805"))
    )
    (comp (ref "C22")
      (value "470u")
      (footprint "eagle-import:CAPAE835X1020N")
      (libsource (lib "eagle-import") (part "CPOL"))
    )
    (comp (ref "C23")
      (value "1n")
      (footprint "eagle-import:CAPC1005X55N")
      (libsource (lib "eagle-import") (part "C_402"))
    )
    (comp (ref "C24")
      (value "10u")
      (footprint "eagle-import:CAPC2013X100N")
      (libsource (lib "eagle-import") (part "C_805"))
    )
    (comp (ref "C25")
      (value "10u")
      (footprint "eagle-import:CAPC2013X100N")
      (libsource (lib "eagle-import") (part "C_805"))
    )
    (comp (ref "C26")
      (value "470u")
      (footprint "eagle-import:CAPAE835X1020N")
      (libsource (lib "eagle-import") (part "CPOL"))
    )
    (comp (ref "C27")
      (value "nc")
      (footprint "eagle-import:CAPC1005X55N")
      (libsource (lib "eagle-import") (part "C_402"))
    )
    (comp (ref "CON1")
      (value "ELEC")
      (footprint "eagle-import:PHOENIX381P900X920-2N")
      (libsource (lib "eagle-import") (part "CON2_3.81"))
    )
    (comp (ref "CON2")
      (value "SERVO")
      (footprint "eagle-import:PHOENIX381P900X920-2N")
      (libsource (lib "eagle-import") (part "CON2_3.81"))
    )
    (comp (ref "CON3")
      (value "LIPO_MOT")
      (footprint "eagle-import:PHOENIX381P900X920-2N")
      (libsource (lib "eagle-import") (part "CON2_3.81"))
    )
    (comp (ref "CON4")
      (value "LIPO_MOT")
      (footprint "eagle-import:PHOENIX381P900X920-2N")
      (libsource (lib "eagle-import") (part "CON2_3.81"))
    )
    (comp (ref "CON5")
      (value "LIPO_MOT")
      (footprint "eagle-import:PHOENIX381P900X920-2N")
      (libsource (lib "eagle-import") (part "CON2_3.81"))
    )
    (comp (ref "CON6")
      (value "LIPO_MOT")
      (footprint "eagle-import:PHOENIX381P900X920-2N")
      (libsource (lib "eagle-import") (part "CON2_3.81"))
    )
    (comp (ref "CON7")
      (value "FPGApower")
      (footprint "eagle-import:PHOENIX381P900X920-2N")
      (libsource (lib "eagle-import") (part "CON2_3.81"))
    )
    (comp (ref "D1")
      (value "SMP12A")
      (footprint "eagle-import:DO220AA")
      (libsource (lib "eagle-import") (part "ZENER"))
    )
    (comp (ref "D2")
      (value "SMP12A")
      (footprint "eagle-import:DO220AA")
      (libsource (lib "eagle-import") (part "ZENER"))
    )
    (comp (ref "D3")
      (value "SMAJ51A")
      (footprint "eagle-import:D0214AC")
      (libsource (lib "eagle-import") (part "ZENERDO214"))
    )
    (comp (ref "D4")
      (value "LED_603")
      (footprint "eagle-import:LEDC1608X60N")
      (libsource (lib "eagle-import") (part "LED_603"))
    )
    (comp (ref "D5")
      (value "LED_603")
      (footprint "eagle-import:LEDC1608X60N")
      (libsource (lib "eagle-import") (part "LED_603"))
    )
    (comp (ref "D6")
      (value "LED_603")
      (footprint "eagle-import:LEDC1608X60N")
      (libsource (lib "eagle-import") (part "LED_603"))
    )
    (comp (ref "D7")
      (value "LED_603")
      (footprint "eagle-import:LEDC1608X60N")
      (libsource (lib "eagle-import") (part "LED_603"))
    )
    (comp (ref "D8")
      (value "LED_603")
      (footprint "eagle-import:LEDC1608X60N")
      (libsource (lib "eagle-import") (part "LED_603"))
    )
    (comp (ref "J1")
      (value "NC")
      (footprint "eagle-import:JUMC1608X50AN")
      (libsource (lib "eagle-import") (part "JUMP_603"))
    )
    (comp (ref "J2")
      (value "nc")
      (footprint "eagle-import:JUMC1005X50N")
      (libsource (lib "eagle-import") (part "JUMP_402"))
    )
    (comp (ref "J3")
      (value "0")
      (footprint "eagle-import:JUMC1005X50N")
      (libsource (lib "eagle-import") (part "JUMP_402"))
    )
    (comp (ref "R1")
      (value "3.3k")
      (footprint "eagle-import:RESC1005X40N")
      (libsource (lib "eagle-import") (part "R_402"))
    )
    (comp (ref "R2")
      (value "3.3k")
      (footprint "eagle-import:RESC1005X40N")
      (libsource (lib "eagle-import") (part "R_402"))
    )
    (comp (ref "R3")
      (value "3.3k")
      (footprint "eagle-import:RESC1005X40N")
      (libsource (lib "eagle-import") (part "R_402"))
    )
    (comp (ref "R4")
      (value "33k")
      (footprint "eagle-import:RESC1005X40N")
      (libsource (lib "eagle-import") (part "R_402"))
    )
    (comp (ref "R5")
      (value "1k")
      (footprint "eagle-import:RESC1005X40N")
      (libsource (lib "eagle-import") (part "R_402"))
    )
    (comp (ref "R6")
      (value "1k")
      (footprint "eagle-import:RESC1005X40N")
      (libsource (lib "eagle-import") (part "R_402"))
    )
    (comp (ref "R7")
      (value "1k")
      (footprint "eagle-import:RESC1005X40N")
      (libsource (lib "eagle-import") (part "R_402"))
    )
    (comp (ref "R8")
      (value "3.3k")
      (footprint "eagle-import:RESC1005X40N")
      (libsource (lib "eagle-import") (part "R_402"))
    )
    (comp (ref "R9")
      (value "240")
      (footprint "eagle-import:RESC1005X40N")
      (libsource (lib "eagle-import") (part "R_402"))
    )
    (comp (ref "R10")
      (value "560")
      (footprint "eagle-import:RESC1005X40N")
      (libsource (lib "eagle-import") (part "R_402"))
    )
    (comp (ref "R11")
      (value "560")
      (footprint "eagle-import:RESC1005X40N")
      (libsource (lib "eagle-import") (part "R_402"))
    )
    (comp (ref "R12")
      (value "560")
      (footprint "eagle-import:RESC1005X40N")
      (libsource (lib "eagle-import") (part "R_402"))
    )
    (comp (ref "R13")
      (value "560")
      (footprint "eagle-import:RESC1005X40N")
      (libsource (lib "eagle-import") (part "R_402"))
    )
    (comp (ref "R14")
      (value "5k")
      (footprint "eagle-import:RESC1005X40N")
      (libsource (lib "eagle-import") (part "R_402"))
    )
    (comp (ref "R15")
      (value "100k")
      (footprint "eagle-import:RESC1005X40N")
      (libsource (lib "eagle-import") (part "R_402"))
    )
    (comp (ref "R16")
      (value "32k")
      (footprint "eagle-import:RESC1005X40N")
      (libsource (lib "eagle-import") (part "R_402"))
    )
    (comp (ref "R17")
      (value "100k")
      (footprint "eagle-import:RESC1005X40N")
      (libsource (lib "eagle-import") (part "R_402"))
    )
    (comp (ref "R18")
      (value "19k")
      (footprint "eagle-import:RESC1005X40N")
      (libsource (lib "eagle-import") (part "R_402"))
    )
    (comp (ref "R19")
      (value "100k")
      (footprint "eagle-import:RESC1005X40N")
      (libsource (lib "eagle-import") (part "R_402"))
    )
    (comp (ref "R20")
      (value "19k")
      (footprint "eagle-import:RESC1005X40N")
      (libsource (lib "eagle-import") (part "R_402"))
    )
    (comp (ref "T1")
      (value "MOSFET_NTR5198NL")
      (footprint "eagle-import:SOT95P290X130-3N")
      (libsource (lib "eagle-import") (part "MOSFET_NTR5198NL"))
    )
    (comp (ref "U1")
      (value "SN74LV4052A_SO")
      (footprint "eagle-import:SOIC127P780X200-16N")
      (libsource (lib "eagle-import") (part "SN74LV4052A_SO"))
    )
    (comp (ref "U2")
      (value "BUZZER")
      (footprint "eagle-import:BUZZER_CIRCLE")
      (libsource (lib "eagle-import") (part "BUZZER"))
    )
    (comp (ref "U3")
      (value "PTR08100W")
      (footprint "eagle-import:PTR08100W")
      (libsource (lib "eagle-import") (part "PTR08100W"))
    )
    (comp (ref "U4")
      (value "TPS82130")
      (footprint "eagle-import:SON65P310X290X153-9N")
      (libsource (lib "eagle-import") (part "TPS82130"))
    )
    (comp (ref "U5")
      (value "TPS82130")
      (footprint "eagle-import:SON65P310X290X153-9N")
      (libsource (lib "eagle-import") (part "TPS82130"))
    )
    (comp (ref "U6")
      (value "TPS82130")
      (footprint "eagle-import:SON65P310X290X153-9N")
      (libsource (lib "eagle-import") (part "TPS82130"))
    )
    (comp (ref "C196")
      (value "2u")
      (footprint "eagle-import:CAPC1608X95N")
      (libsource (lib "eagle-import") (part "C_603"))
    )
    (comp (ref "C197")
      (value "2u")
      (footprint "eagle-import:CAPC1608X95N")
      (libsource (lib "eagle-import") (part "C_603"))
    )
    (comp (ref "C198")
      (value "2u")
      (footprint "eagle-import:CAPC1608X95N")
      (libsource (lib "eagle-import") (part "C_603"))
    )
    (comp (ref "C199")
      (value "2u")
      (footprint "eagle-import:CAPC1608X95N")
      (libsource (lib "eagle-import") (part "C_603"))
    )
    (comp (ref "CON61")
      (value "CON5_2.54S")
      (footprint "eagle-import:CON254P1270X400-5S")
      (libsource (lib "eagle-import") (part "CON5_2.54S"))
    )
    (comp (ref "CON62")
      (value "CON5_2.54S")
      (footprint "eagle-import:CON254P1270X400-5S")
      (libsource (lib "eagle-import") (part "CON5_2.54S"))
    )
    (comp (ref "CON63")
      (value "CON5_2.54S")
      (footprint "eagle-import:CON254P1270X400-5S")
      (libsource (lib "eagle-import") (part "CON5_2.54S"))
    )
    (comp (ref "CON64")
      (value "CON5_2.54S")
      (footprint "eagle-import:CON254P1270X400-5S")
      (libsource (lib "eagle-import") (part "CON5_2.54S"))
    )
    (comp (ref "R107")
      (value "10k")
      (footprint "eagle-import:RESC1005X40N")
      (libsource (lib "eagle-import") (part "R_402"))
    )
    (comp (ref "R108")
      (value "10k")
      (footprint "eagle-import:RESC1005X40N")
      (libsource (lib "eagle-import") (part "R_402"))
    )
    (comp (ref "R109")
      (value "10k")
      (footprint "eagle-import:RESC1005X40N")
      (libsource (lib "eagle-import") (part "R_402"))
    )
    (comp (ref "R110")
      (value "10k")
      (footprint "eagle-import:RESC1005X40N")
      (libsource (lib "eagle-import") (part "R_402"))
    )
    (comp (ref "U33")
      (value "VL53L0X")
      (footprint "eagle-import:VL53L0X")
      (libsource (lib "eagle-import") (part "VL53L0X"))
    )
    (comp (ref "U34")
      (value "TCA6408A")
      (footprint "eagle-import:QFN50P300X300X80-17N")
      (libsource (lib "eagle-import") (part "I2C_EXPTCA6408A"))
    )
    (comp (ref "U35")
      (value "LP5900SD-2.8")
      (footprint "eagle-import:SON65P250X220X80-7N")
      (libsource (lib "eagle-import") (part "REG_EN_LP5900"))
    )
    (comp (ref "U36")
      (value "VL6180X")
      (footprint "eagle-import:VL6180X")
      (libsource (lib "eagle-import") (part "VL6180X"))
    )
    (comp (ref "U39")
      (value "TCA6408A")
      (footprint "eagle-import:QFN50P300X300X80-17N")
      (libsource (lib "eagle-import") (part "I2C_EXPTCA6408A"))
    )
    (comp (ref "U40")
      (value "LP5900SD-2.8")
      (footprint "eagle-import:SON65P250X220X80-7N")
      (libsource (lib "eagle-import") (part "REG_EN_LP5900"))
    )
    (comp (ref "C138")
      (value "100n")
      (footprint "eagle-import:CAPC1005X55N")
      (libsource (lib "eagle-import") (part "C_402"))
    )
    (comp (ref "C139")
      (value "100n")
      (footprint "eagle-import:CAPC1005X55N")
      (libsource (lib "eagle-import") (part "C_402"))
    )
    (comp (ref "C140")
      (value "100n")
      (footprint "eagle-import:CAPC1005X55N")
      (libsource (lib "eagle-import") (part "C_402"))
    )
    (comp (ref "C141")
      (value "100n")
      (footprint "eagle-import:CAPC1005X55N")
      (libsource (lib "eagle-import") (part "C_402"))
    )
    (comp (ref "C142")
      (value "100n")
      (footprint "eagle-import:CAPC1005X55N")
      (libsource (lib "eagle-import") (part "C_402"))
    )
    (comp (ref "C143")
      (value "100n")
      (footprint "eagle-import:CAPC1005X55N")
      (libsource (lib "eagle-import") (part "C_402"))
    )
    (comp (ref "C144")
      (value "100n")
      (footprint "eagle-import:CAPC1005X55N")
      (libsource (lib "eagle-import") (part "C_402"))
    )
    (comp (ref "C145")
      (value "100n")
      (footprint "eagle-import:CAPC1005X55N")
      (libsource (lib "eagle-import") (part "C_402"))
    )
    (comp (ref "C146")
      (value "100n")
      (footprint "eagle-import:CAPC1005X55N")
      (libsource (lib "eagle-import") (part "C_402"))
    )
    (comp (ref "C147")
      (value "100n")
      (footprint "eagle-import:CAPC1005X55N")
      (libsource (lib "eagle-import") (part "C_402"))
    )
    (comp (ref "C148")
      (value "2.2u")
      (footprint "eagle-import:CAPC1608X95N")
      (libsource (lib "eagle-import") (part "C_603"))
    )
    (comp (ref "C149")
      (value "100n")
      (footprint "eagle-import:CAPC1005X55N")
      (libsource (lib "eagle-import") (part "C_402"))
    )
    (comp (ref "C150")
      (value "18p")
      (footprint "eagle-import:CAPC1005X55N")
      (libsource (lib "eagle-import") (part "C_402"))
    )
    (comp (ref "C151")
      (value "18p")
      (footprint "eagle-import:CAPC1005X55N")
      (libsource (lib "eagle-import") (part "C_402"))
    )
    (comp (ref "C152")
      (value "100n")
      (footprint "eagle-import:CAPC1005X55N")
      (libsource (lib "eagle-import") (part "C_402"))
    )
    (comp (ref "C153")
      (value "2.2u")
      (footprint "eagle-import:CAPC1608X95N")
      (libsource (lib "eagle-import") (part "C_603"))
    )
    (comp (ref "C154")
      (value "100n")
      (footprint "eagle-import:CAPC1005X55N")
      (libsource (lib "eagle-import") (part "C_402"))
    )
    (comp (ref "C155")
      (value "100n")
      (footprint "eagle-import:CAPC1005X55N")
      (libsource (lib "eagle-import") (part "C_402"))
    )
    (comp (ref "C156")
      (value "100n")
      (footprint "eagle-import:CAPC1005X55N")
      (libsource (lib "eagle-import") (part "C_402"))
    )
    (comp (ref "C157")
      (value "100n")
      (footprint "eagle-import:CAPC1005X55N")
      (libsource (lib "eagle-import") (part "C_402"))
    )
    (comp (ref "C158")
      (value "2.2u")
      (footprint "eagle-import:CAPC1608X95N")
      (libsource (lib "eagle-import") (part "C_603"))
    )
    (comp (ref "C195")
      (value "100n")
      (footprint "eagle-import:CAPC1005X55N")
      (libsource (lib "eagle-import") (part "C_402"))
    )
    (comp (ref "CON54")
      (value "USB2")
      (footprint "eagle-import:USB_A")
      (libsource (lib "eagle-import") (part "USB_A"))
    )
    (comp (ref "CON55")
      (value "USB3")
      (footprint "eagle-import:USB_A")
      (libsource (lib "eagle-import") (part "USB_A"))
    )
    (comp (ref "CON56")
      (value "USBfpga")
      (footprint "eagle-import:CON254P762X400-3N-S")
      (libsource (lib "eagle-import") (part "CON3_2.54S"))
    )
    (comp (ref "CON60")
      (value "USB3")
      (footprint "eagle-import:USB_A")
      (libsource (lib "eagle-import") (part "USB_A"))
    )
    (comp (ref "D9")
      (value "LED_603")
      (footprint "eagle-import:LEDC1608X60N")
      (libsource (lib "eagle-import") (part "LED_603"))
    )
    (comp (ref "D10")
      (value "LED_603")
      (footprint "eagle-import:LEDC1608X60N")
      (libsource (lib "eagle-import") (part "LED_603"))
    )
    (comp (ref "J48")
      (value "NC")
      (footprint "eagle-import:JUMC1005X50N")
      (libsource (lib "eagle-import") (part "JUMP_402"))
    )
    (comp (ref "J49")
      (value "NC")
      (footprint "eagle-import:JUMC1005X50N")
      (libsource (lib "eagle-import") (part "JUMP_402"))
    )
    (comp (ref "L9")
      (value "600")
      (footprint "eagle-import:INDC1608X95N")
      (libsource (lib "eagle-import") (part "INDUCTANCE_603"))
    )
    (comp (ref "L10")
      (value "600")
      (footprint "eagle-import:INDC1608X95N")
      (libsource (lib "eagle-import") (part "INDUCTANCE_603"))
    )
    (comp (ref "Q1")
      (value "25MHz")
      (footprint "eagle-import:XTAL500X320X130N")
      (libsource (lib "eagle-import") (part "QUARTZ2"))
    )
    (comp (ref "R89")
      (value "10k")
      (footprint "eagle-import:RESC1005X40N")
      (libsource (lib "eagle-import") (part "R_402"))
    )
    (comp (ref "R90")
      (value "1M")
      (footprint "eagle-import:RESC1005X40N")
      (libsource (lib "eagle-import") (part "R_402"))
    )
    (comp (ref "R91")
      (value "10k")
      (footprint "eagle-import:RESC1005X40N")
      (libsource (lib "eagle-import") (part "R_402"))
    )
    (comp (ref "R92")
      (value "330")
      (footprint "eagle-import:RESC1005X40N")
      (libsource (lib "eagle-import") (part "R_402"))
    )
    (comp (ref "R93")
      (value "10k")
      (footprint "eagle-import:RESC1005X40N")
      (libsource (lib "eagle-import") (part "R_402"))
    )
    (comp (ref "R94")
      (value "330")
      (footprint "eagle-import:RESC1005X40N")
      (libsource (lib "eagle-import") (part "R_402"))
    )
    (comp (ref "R95")
      (value "12.4k")
      (footprint "eagle-import:RESC1005X40N")
      (libsource (lib "eagle-import") (part "R_402"))
    )
    (comp (ref "R96")
      (value "12k")
      (footprint "eagle-import:RESC1005X40N")
      (libsource (lib "eagle-import") (part "R_402"))
    )
    (comp (ref "U20")
      (value "LAN9514")
      (footprint "eagle-import:QFN50P900X900X100-65N")
      (libsource (lib "eagle-import") (part "LAN9514"))
    )
    (comp (ref "U21")
      (value "LGA22U")
      (footprint "eagle-import:LGA22U")
      (libsource (lib "eagle-import") (part "LGA22U"))
    )
    (comp (ref "U22")
      (value "LGA22U")
      (footprint "eagle-import:LGA22U")
      (libsource (lib "eagle-import") (part "LGA22U"))
    )
  )
  (nets
    (net (code "1") (name "3V3") (class "Default")
      (node (ref "C138") (pin "2") (pinfunction "P$2_2") (pintype "bidirectional"))
      (node (ref "C139") (pin "2") (pinfunction "P$2_2") (pintype "bidirectional"))
      (node (ref "C140") (pin "2") (pinfunction "P$2_2") (pintype "bidirectional"))
      (node (ref "C141") (pin "2") (pinfunction "P$2_2") (pintype "bidirectional"))
      (node (ref "C142") (pin "2") (pinfunction "P$2_2") (pintype "bidirectional"))
      (node (ref "C17") (pin "P$1") (pinfunction "P$1_P$1") (pintype "bidirectional"))
      (node (ref "C18") (pin "+") (pinfunction "+_+") (pintype "bidirectional"))
      (node (ref "D10") (pin "A") (pinfunction "A_A") (pintype "bidirectional"))
      (node (ref "D9") (pin "A") (pinfunction "A_A") (pintype "bidirectional"))
      (node (ref "L9") (pin "1") (pinfunction "1_1") (pintype "bidirectional"))
      (node (ref "R15") (pin "1") (pinfunction "P$1_1") (pintype "bidirectional"))
      (node (ref "R89") (pin "2") (pinfunction "P$2_2") (pintype "bidirectional"))
      (node (ref "R91") (pin "2") (pinfunction "P$2_2") (pintype "bidirectional"))
      (node (ref "R93") (pin "2") (pinfunction "P$2_2") (pintype "bidirectional"))
      (node (ref "U20") (pin "11") (pinfunction "VBUS_DET_11") (pintype "bidirectional"))
      (node (ref "U20") (pin "19") (pinfunction "VDD33IO_19") (pintype "bidirectional"))
      (node (ref "U20") (pin "27") (pinfunction "VDD33IO_27") (pintype "bidirectional"))
      (node (ref "U20") (pin "28") (pinfunction "NTRST_28") (pintype "bidirectional"))
      (node (ref "U20") (pin "33") (pinfunction "VDD33IO_33") (pintype "bidirectional"))
      (node (ref "U20") (pin "39") (pinfunction "VDD33IO_39") (pintype "bidirectional"))
      (node (ref "U20") (pin "40") (pinfunction "TEST3_40") (pintype "bidirectional"))
      (node (ref "U20") (pin "41") (pinfunction "AUTOMDIX_EN_41") (pintype "bidirectional"))
      (node (ref "U20") (pin "46") (pinfunction "VDD33IO_46") (pintype "bidirectional"))
      (node (ref "U21") (pin "P$6") (pinfunction "VDD33_P$6") (pintype "bidirectional"))
      (node (ref "U22") (pin "P$6") (pinfunction "VDD33_P$6") (pintype "bidirectional"))
      (node (ref "U4") (pin "P$4") (pinfunction "VO_P$4") (pintype "bidirectional"))
      (node (ref "U4") (pin "P$5") (pinfunction "VO_P$5") (pintype "bidirectional"))
    )
    (net (code "2") (name "5V") (class "Default")
      (node (ref "C103") (pin "2") (pinfunction "P$2_2") (pintype "bidirectional"))
      (node (ref "C109") (pin "2") (pinfunction "P$2_2") (pintype "bidirectional"))
      (node (ref "C118") (pin "2") (pinfunction "P$2_2") (pintype "bidirectional"))
      (node (ref "C125") (pin "2") (pinfunction "P$2_2") (pintype "bidirectional"))
      (node (ref "C149") (pin "2") (pinfunction "P$2_2") (pintype "bidirectional"))
      (node (ref "C152") (pin "2") (pinfunction "P$2_2") (pintype "bidirectional"))
      (node (ref "C159") (pin "2") (pinfunction "P$2_2") (pintype "bidirectional"))
      (node (ref "C161") (pin "2") (pinfunction "P$2_2") (pintype "bidirectional"))
      (node (ref "C162") (pin "2") (pinfunction "P$2_2") (pintype "bidirectional"))
      (node (ref "C163") (pin "2") (pinfunction "P$2_2") (pintype "bidirectional"))
      (node (ref "C164") (pin "2") (pinfunction "P$2_2") (pintype "bidirectional"))
      (node (ref "C165") (pin "2") (pinfunction "P$2_2") (pintype "bidirectional"))
      (node (ref "C172") (pin "2") (pinfunction "P$2_2") (pintype "bidirectional"))
      (node (ref "C173") (pin "2") (pinfunction "P$2_2") (pintype "bidirectional"))
      (node (ref "C174") (pin "2") (pinfunction "P$2_2") (pintype "bidirectional"))
      (node (ref "C195") (pin "2") (pinfunction "P$2_2") (pintype "bidirectional"))
      (node (ref "C21") (pin "P$1") (pinfunction "P$1_P$1") (pintype "bidirectional"))
      (node (ref "C22") (pin "+") (pinfunction "+_+") (pintype "bidirectional"))
      (node (ref "C28") (pin "2") (pinfunction "P$2_2") (pintype "bidirectional"))
      (node (ref "C37") (pin "2") (pinfunction "P$2_2") (pintype "bidirectional"))
      (node (ref "C46") (pin "2") (pinfunction "P$2_2") (pintype "bidirectional"))
      (node (ref "C93") (pin "1") (pinfunction "P$1_1") (pintype "bidirectional"))
      (node (ref "C98") (pin "1") (pinfunction "P$1_1") (pintype "bidirectional"))
      (node (ref "CON15") (pin "P$9") (pinfunction "9_P$9") (pintype "bidirectional"))
      (node (ref "CON16") (pin "P$9") (pinfunction "9_P$9") (pintype "bidirectional"))
      (node (ref "CON18") (pin "4") (pinfunction "4_4") (pintype "bidirectional"))
      (node (ref "CON19") (pin "5") (pinfunction "5_5") (pintype "bidirectional"))
      (node (ref "CON20") (pin "2") (pinfunction "2_2") (pintype "bidirectional"))
      (node (ref "CON22") (pin "2") (pinfunction "2_2") (pintype "bidirectional"))
      (node (ref "CON23") (pin "2") (pinfunction "2_2") (pintype "bidirectional"))
      (node (ref "CON25") (pin "2") (pinfunction "2_2") (pintype "bidirectional"))
      (node (ref "CON26") (pin "4") (pinfunction "4_4") (pintype "bidirectional"))
      (node (ref "CON27") (pin "5") (pinfunction "5_5") (pintype "bidirectional"))
      (node (ref "CON28") (pin "2") (pinfunction "2_2") (pintype "bidirectional"))
      (node (ref "CON30") (pin "2") (pinfunction "2_2") (pintype "bidirectional"))
      (node (ref "CON31") (pin "4") (pinfunction "4_4") (pintype "bidirectional"))
      (node (ref "CON32") (pin "5") (pinfunction "5_5") (pintype "bidirectional"))
      (node (ref "CON33") (pin "2") (pinfunction "2_2") (pintype "bidirectional"))
      (node (ref "CON35") (pin "2") (pinfunction "2_2") (pintype "bidirectional"))
      (node (ref "CON37") (pin "2") (pinfunction "2_2") (pintype "bidirectional"))
      (node (ref "CON39") (pin "2") (pinfunction "2_2") (pintype "bidirectional"))
      (node (ref "CON40") (pin "6") (pinfunction "6_6") (pintype "bidirectional"))
      (node (ref "CON41") (pin "5") (pinfunction "5_5") (pintype "bidirectional"))
      (node (ref "CON42") (pin "2") (pinfunction "2_2") (pintype "bidirectional"))
      (node (ref "CON44") (pin "2") (pinfunction "2_2") (pintype "bidirectional"))
      (node (ref "CON45") (pin "6") (pinfunction "6_6") (pintype "bidirectional"))
      (node (ref "CON46") (pin "2") (pinfunction "2_2") (pintype "bidirectional"))
      (node (ref "CON48") (pin "2") (pinfunction "2_2") (pintype "bidirectional"))
      (node (ref "CON49") (pin "5") (pinfunction "5_5") (pintype "bidirectional"))
      (node (ref "CON50") (pin "2") (pinfunction "2_2") (pintype "bidirectional"))
      (node (ref "CON52") (pin "2") (pinfunction "2_2") (pintype "bidirectional"))
      (node (ref "CON53") (pin "5") (pinfunction "5_5") (pintype "bidirectional"))
      (node (ref "CON54") (pin "1") (pinfunction "VBUS_1") (pintype "bidirectional"))
      (node (ref "CON55") (pin "1") (pinfunction "VBUS_1") (pintype "bidirectional"))
      (node (ref "CON60") (pin "1") (pinfunction "VBUS_1") (pintype "bidirectional"))
      (node (ref "IC1") (pin "6") (pinfunction "AVDD_6") (pintype "passive"))
      (node (ref "IC2") (pin "44") (pinfunction "AVDD_44") (pintype "passive"))
      (node (ref "IC2") (pin "5") (pinfunction "AVDD_5") (pintype "passive"))
      (node (ref "IC2") (pin "53") (pinfunction "AVDD_53") (pintype "passive"))
      (node (ref "IC2") (pin "60") (pinfunction "AVDD_60") (pintype "passive"))
      (node (ref "IC3") (pin "2") (pinfunction "VIN_2") (pintype "passive"))
      (node (ref "IC4") (pin "2") (pinfunction "VIN_2") (pintype "passive"))
      (node (ref "J3") (pin "P$1") (pinfunction "1_P$1") (pintype "bidirectional"))
      (node (ref "J33") (pin "P$2") (pinfunction "2_P$2") (pintype "bidirectional"))
      (node (ref "J35") (pin "P$2") (pinfunction "2_P$2") (pintype "bidirectional"))
      (node (ref "J37") (pin "P$2") (pinfunction "2_P$2") (pintype "bidirectional"))
      (node (ref "J39") (pin "P$2") (pinfunction "2_P$2") (pintype "bidirectional"))
      (node (ref "J41") (pin "P$2") (pinfunction "2_P$2") (pintype "bidirectional"))
      (node (ref "J43") (pin "P$2") (pinfunction "2_P$2") (pintype "bidirectional"))
      (node (ref "J45") (pin "P$2") (pinfunction "2_P$2") (pintype "bidirectional"))
      (node (ref "R13") (pin "1") (pinfunction "P$1_1") (pintype "bidirectional"))
      (node (ref "R17") (pin "1") (pinfunction "P$1_1") (pintype "bidirectional"))
      (node (ref "R39") (pin "2") (pinfunction "P$2_2") (pintype "bidirectional"))
      (node (ref "R40") (pin "2") (pinfunction "P$2_2") (pintype "bidirectional"))
      (node (ref "R50") (pin "2") (pinfunction "P$2_2") (pintype "bidirectional"))
      (node (ref "R51") (pin "2") (pinfunction "P$2_2") (pintype "bidirectional"))
      (node (ref "U12") (pin "P$5") (pinfunction "VS_P$5") (pintype "bidirectional"))
      (node (ref "U13") (pin "P$5") (pinfunction "VS_P$5") (pintype "bidirectional"))
      (node (ref "U15") (pin "P$5") (pinfunction "VS_P$5") (pintype "bidirectional"))
      (node (ref "U16") (pin "P$5") (pinfunction "VS_P$5") (pintype "bidirectional"))
      (node (ref "U18") (pin "P$5") (pinfunction "VS_P$5") (pintype "bidirectional"))
      (node (ref "U23") (pin "4") (pinfunction "EN_4") (pintype "bidirectional"))
      (node (ref "U23") (pin "6") (pinfunction "VI_6") (pintype "bidirectional"))
      (node (ref "U24") (pin "P$5") (pinfunction "VCC_P$5") (pintype "bidirectional"))
      (node (ref "U5") (pin "P$4") (pinfunction "VO_P$4") (pintype "bidirectional"))
      (node (ref "U5") (pin "P$5") (pinfunction "VO_P$5") (pintype "bidirectional"))
      (node (ref "U7") (pin "P$5") (pinfunction "VS_P$5") (pintype "bidirectional"))
      (node (ref "U8") (pin "P$5") (pinfunction "VS_P$5") (pintype "bidirectional"))
    )
    (net (code "3") (name "12V") (class "Default")
      (node (ref "C1") (pin "1") (pinfunction "P$1_1") (pintype "bidirectional"))
      (node (ref "C16") (pin "P$1") (pinfunction "P$1_P$1") (pintype "bidirectional"))
      (node (ref "C2") (pin "+") (pinfunction "+_+") (pintype "bidirectional"))
      (node (ref "C20") (pin "P$1") (pinfunction "P$1_P$1") (pintype "bidirectional"))
      (node (ref "C24") (pin "P$1") (pinfunction "P$1_P$1") (pintype "bidirectional"))
      (node (ref "CON1") (pin "P$2") (pinfunction "2_P$2") (pintype "bidirectional"))
      (node (ref "CON36") (pin "4") (pinfunction "4_4") (pintype "bidirectional"))
      (node (ref "D1") (pin "C") (pinfunction "C_C") (pintype "bidirectional"))
      (node (ref "J1") (pin "P$2") (pinfunction "2_P$2") (pintype "bidirectional"))
      (node (ref "R1") (pin "1") (pinfunction "P$1_1") (pintype "bidirectional"))
      (node (ref "U4") (pin "P$1") (pinfunction "EN_P$1") (pintype "bidirectional"))
      (node (ref "U4") (pin "P$2") (pinfunction "VI_P$2") (pintype "bidirectional"))
      (node (ref "U5") (pin "P$1") (pinfunction "EN_P$1") (pintype "bidirectional"))
      (node (ref "U5") (pin "P$2") (pinfunction "VI_P$2") (pintype "bidirectional"))
      (node (ref "U6") (pin "P$1") (pinfunction "EN_P$1") (pintype "bidirectional"))
      (node (ref "U6") (pin "P$2") (pinfunction "VI_P$2") (pintype "bidirectional"))
    )
    (net (code "4") (name "24V") (class "Default")
      (node (ref "C11") (pin "P$1") (pinfunction "P$1_P$1") (pintype "bidirectional"))
      (node (ref "C12") (pin "+") (pinfunction "+_+") (pintype "bidirectional"))
      (node (ref "C33") (pin "P$2") (pinfunction "P$2_P$2") (pintype "bidirectional"))
      (node (ref "C34") (pin "P$2") (pinfunction "P$2_P$2") (pintype "bidirectional"))
      (node (ref "C35") (pin "P$2") (pinfunction "P$2_P$2") (pintype "bidirectional"))
      (node (ref "C36") (pin "P$2") (pinfunction "P$2_P$2") (pintype "bidirectional"))
      (node (ref "C77") (pin "P$2") (pinfunction "P$2_P$2") (pintype "bidirectional"))
      (node (ref "C78") (pin "P$2") (pinfunction "P$2_P$2") (pintype "bidirectional"))
      (node (ref "C79") (pin "P$2") (pinfunction "P$2_P$2") (pintype "bidirectional"))
      (node (ref "C80") (pin "P$2") (pinfunction "P$2_P$2") (pintype "bidirectional"))
      (node (ref "CON3") (pin "P$2") (pinfunction "2_P$2") (pintype "bidirectional"))
      (node (ref "D3") (pin "C") (pinfunction "C_C") (pintype "bidirectional"))
      (node (ref "J24") (pin "P$1") (pinfunction "1_P$1") (pintype "bidirectional"))
      (node (ref "J5") (pin "P$1") (pinfunction "1_P$1") (pintype "bidirectional"))
      (node (ref "J7") (pin "P$1") (pinfunction "1_P$1") (pintype "bidirectional"))
      (node (ref "R14") (pin "1") (pinfunction "P$1_1") (pintype "bidirectional"))
      (node (ref "R4") (pin "1") (pinfunction "P$1_1") (pintype "bidirectional"))
      (node (ref "U14") (pin "P$21") (pinfunction "VDDD_P$21") (pintype "bidirectional"))
      (node (ref "U14") (pin "P$26") (pinfunction "VDDC_P$26") (pintype "bidirectional"))
      (node (ref "U14") (pin "P$29") (pinfunction "VDDB_P$29") (pintype "bidirectional"))
      (node (ref "U14") (pin "P$34") (pinfunction "VDDA_P$34") (pintype "bidirectional"))
      (node (ref "U9") (pin "P$21") (pinfunction "VDDD_P$21") (pintype "bidirectional"))
      (node (ref "U9") (pin "P$26") (pinfunction "VDDC_P$26") (pintype "bidirectional"))
      (node (ref "U9") (pin "P$29") (pinfunction "VDDB_P$29") (pintype "bidirectional"))
      (node (ref "U9") (pin "P$34") (pinfunction "VDDA_P$34") (pintype "bidirectional"))
    )
    (net (code "5") (name "A5V") (class "Default")
      (node (ref "C14") (pin "P$1") (pinfunction "P$1_P$1") (pintype "bidirectional"))
      (node (ref "C15") (pin "+") (pinfunction "+_+") (pintype "bidirectional"))
      (node (ref "C94") (pin "1") (pinfunction "P$1_1") (pintype "bidirectional"))
      (node (ref "C99") (pin "1") (pinfunction "P$1_1") (pintype "bidirectional"))
      (node (ref "CON15") (pin "P$2") (pinfunction "2_P$2") (pintype "bidirectional"))
      (node (ref "CON16") (pin "P$2") (pinfunction "2_P$2") (pintype "bidirectional"))
      (node (ref "CON21") (pin "2") (pinfunction "2_2") (pintype "bidirectional"))
      (node (ref "CON24") (pin "2") (pinfunction "2_2") (pintype "bidirectional"))
      (node (ref "CON29") (pin "2") (pinfunction "2_2") (pintype "bidirectional"))
      (node (ref "CON34") (pin "2") (pinfunction "2_2") (pintype "bidirectional"))
      (node (ref "CON38") (pin "2") (pinfunction "2_2") (pintype "bidirectional"))
      (node (ref "CON43") (pin "2") (pinfunction "2_2") (pintype "bidirectional"))
      (node (ref "CON47") (pin "2") (pinfunction "2_2") (pintype "bidirectional"))
      (node (ref "CON51") (pin "2") (pinfunction "2_2") (pintype "bidirectional"))
      (node (ref "J26") (pin "P$1") (pinfunction "1_P$1") (pintype "bidirectional"))
      (node (ref "J27") (pin "P$1") (pinfunction "1_P$1") (pintype "bidirectional"))
      (node (ref "K1") (pin "2") (pinfunction "C_2") (pintype "bidirectional"))
      (node (ref "K2") (pin "11") (pinfunction "C_11") (pintype "bidirectional"))
      (node (ref "K3") (pin "11") (pinfunction "C_11") (pintype "bidirectional"))
      (node (ref "K4") (pin "2") (pinfunction "C_2") (pintype "bidirectional"))
      (node (ref "R12") (pin "1") (pinfunction "P$1_1") (pintype "bidirectional"))
      (node (ref "R2") (pin "1") (pinfunction "P$1_1") (pintype "bidirectional"))
      (node (ref "U3") (pin "P$4") (pinfunction "VOUT_P$4") (pintype "bidirectional"))
    )
    (net (code "6") (name "A12V") (class "Default")
      (node (ref "C13") (pin "P$1") (pinfunction "P$1_P$1") (pintype "bidirectional"))
      (node (ref "C29") (pin "P$2") (pinfunction "P$2_P$2") (pintype "bidirectional"))
      (node (ref "C30") (pin "P$2") (pinfunction "P$2_P$2") (pintype "bidirectional"))
      (node (ref "C31") (pin "P$2") (pinfunction "P$2_P$2") (pintype "bidirectional"))
      (node (ref "C32") (pin "P$2") (pinfunction "P$2_P$2") (pintype "bidirectional"))
      (node (ref "C38") (pin "P$2") (pinfunction "P$2_P$2") (pintype "bidirectional"))
      (node (ref "C39") (pin "P$2") (pinfunction "P$2_P$2") (pintype "bidirectional"))
      (node (ref "C40") (pin "P$2") (pinfunction "P$2_P$2") (pintype "bidirectional"))
      (node (ref "C41") (pin "P$2") (pinfunction "P$2_P$2") (pintype "bidirectional"))
      (node (ref "C47") (pin "P$2") (pinfunction "P$2_P$2") (pintype "bidirectional"))
      (node (ref "C48") (pin "P$2") (pinfunction "P$2_P$2") (pintype "bidirectional"))
      (node (ref "C49") (pin "P$2") (pinfunction "P$2_P$2") (pintype "bidirectional"))
      (node (ref "C5") (pin "1") (pinfunction "P$1_1") (pintype "bidirectional"))
      (node (ref "C50") (pin "P$2") (pinfunction "P$2_P$2") (pintype "bidirectional"))
      (node (ref "C6") (pin "+") (pinfunction "+_+") (pintype "bidirectional"))
      (node (ref "C81") (pin "P$2") (pinfunction "P$2_P$2") (pintype "bidirectional"))
      (node (ref "C82") (pin "P$2") (pinfunction "P$2_P$2") (pintype "bidirectional"))
      (node (ref "C83") (pin "P$2") (pinfunction "P$2_P$2") (pintype "bidirectional"))
      (node (ref "C84") (pin "P$2") (pinfunction "P$2_P$2") (pintype "bidirectional"))
      (node (ref "CON2") (pin "P$2") (pinfunction "2_P$2") (pintype "bidirectional"))
      (node (ref "D2") (pin "C") (pinfunction "C_C") (pintype "bidirectional"))
      (node (ref "J1") (pin "P$1") (pinfunction "1_P$1") (pintype "bidirectional"))
      (node (ref "J2") (pin "P$1") (pinfunction "1_P$1") (pintype "bidirectional"))
      (node (ref "J25") (pin "P$1") (pinfunction "1_P$1") (pintype "bidirectional"))
      (node (ref "J4") (pin "P$1") (pinfunction "1_P$1") (pintype "bidirectional"))
      (node (ref "J6") (pin "P$1") (pinfunction "1_P$1") (pintype "bidirectional"))
      (node (ref "R3") (pin "1") (pinfunction "P$1_1") (pintype "bidirectional"))
      (node (ref "U10") (pin "P$1") (pinfunction "VDD_P$1") (pintype "bidirectional"))
      (node (ref "U10") (pin "P$17") (pinfunction "VDD_P$17") (pintype "bidirectional"))
      (node (ref "U10") (pin "P$18") (pinfunction "VDD_P$18") (pintype "bidirectional"))
      (node (ref "U10") (pin "P$19") (pinfunction "VDD_P$19") (pintype "bidirectional"))
      (node (ref "U10") (pin "P$36") (pinfunction "VDD_P$36") (pintype "bidirectional"))
      (node (ref "U11") (pin "P$1") (pinfunction "VDD_P$1") (pintype "bidirectional"))
      (node (ref "U11") (pin "P$17") (pinfunction "VDD_P$17") (pintype "bidirectional"))
      (node (ref "U11") (pin "P$18") (pinfunction "VDD_P$18") (pintype "bidirectional"))
      (node (ref "U11") (pin "P$19") (pinfunction "VDD_P$19") (pintype "bidirectional"))
      (node (ref "U11") (pin "P$36") (pinfunction "VDD_P$36") (pintype "bidirectional"))
      (node (ref "U14") (pin "P$1") (pinfunction "VDD_P$1") (pintype "bidirectional"))
      (node (ref "U14") (pin "P$17") (pinfunction "VDD_P$17") (pintype "bidirectional"))
      (node (ref "U14") (pin "P$18") (pinfunction "VDD_P$18") (pintype "bidirectional"))
      (node (ref "U14") (pin "P$19") (pinfunction "VDD_P$19") (pintype "bidirectional"))
      (node (ref "U14") (pin "P$36") (pinfunction "VDD_P$36") (pintype "bidirectional"))
      (node (ref "U3") (pin "P$2") (pinfunction "VIN_P$2") (pintype "bidirectional"))
      (node (ref "U9") (pin "P$1") (pinfunction "VDD_P$1") (pintype "bidirectional"))
      (node (ref "U9") (pin "P$17") (pinfunction "VDD_P$17") (pintype "bidirectional"))
      (node (ref "U9") (pin "P$18") (pinfunction "VDD_P$18") (pintype "bidirectional"))
      (node (ref "U9") (pin "P$19") (pinfunction "VDD_P$19") (pintype "bidirectional"))
      (node (ref "U9") (pin "P$36") (pinfunction "VDD_P$36") (pintype "bidirectional"))
    )
    (net (code "7") (name "AD0_CLK") (class "Default")
      (node (ref "CON57") (pin "6") (pinfunction "6_6") (pintype "bidirectional"))
      (node (ref "IC2") (pin "27") (pinfunction "CLK_27") (pintype "passive"))
    )
    (net (code "8") (name "AD0_DRDY") (class "Default")
      (node (ref "CON57") (pin "10") (pinfunction "10_10") (pintype "bidirectional"))
      (node (ref "IC2") (pin "29") (pinfunction "DRDY/_29") (pintype "passive"))
    )
    (net (code "9") (name "AD0_MISO") (class "Default")
      (node (ref "CON57") (pin "2") (pinfunction "2_2") (pintype "bidirectional"))
      (node (ref "IC2") (pin "20") (pinfunction "DOUT1_20") (pintype "passive"))
    )
    (net (code "10") (name "AD0_SCLK") (class "Default")
      (node (ref "CON57") (pin "8") (pinfunction "8_8") (pintype "bidirectional"))
      (node (ref "IC2") (pin "28") (pinfunction "SCLK_28") (pintype "passive"))
    )
    (net (code "11") (name "AD0_SYNC") (class "Default")
      (node (ref "CON57") (pin "4") (pinfunction "4_4") (pintype "bidirectional"))
      (node (ref "IC2") (pin "11") (pinfunction "SYNC_11") (pintype "passive"))
    )
    (net (code "12") (name "AD0_VREF") (class "Default")
      (node (ref "C171") (pin "2") (pinfunction "P$2_2") (pintype "bidirectional"))
      (node (ref "C180") (pin "P$1") (pinfunction "P$1_P$1") (pintype "bidirectional"))
      (node (ref "C57") (pin "2") (pinfunction "P$2_2") (pintype "bidirectional"))
      (node (ref "C59") (pin "2") (pinfunction "P$2_2") (pintype "bidirectional"))
      (node (ref "C72") (pin "2") (pinfunction "P$2_2") (pintype "bidirectional"))
      (node (ref "CON16") (pin "P$10") (pinfunction "10_P$10") (pintype "bidirectional"))
      (node (ref "IC2") (pin "2") (pinfunction "AINN2_2") (pintype "passive"))
      (node (ref "IC2") (pin "46") (pinfunction "AINN8_46") (pintype "passive"))
      (node (ref "IC2") (pin "48") (pinfunction "AINN7_48") (pintype "passive"))
      (node (ref "IC2") (pin "50") (pinfunction "AINN6_50") (pintype "passive"))
      (node (ref "IC2") (pin "52") (pinfunction "AINN5_52") (pintype "passive"))
      (node (ref "IC2") (pin "56") (pinfunction "VREFP_56") (pintype "passive"))
      (node (ref "IC2") (pin "62") (pinfunction "AINN4_62") (pintype "passive"))
      (node (ref "IC2") (pin "64") (pinfunction "AINN3_64") (pintype "passive"))
      (node (ref "J30") (pin "P$1") (pinfunction "1_P$1") (pintype "bidirectional"))
      (node (ref "J32") (pin "P$2") (pinfunction "2_P$2") (pintype "bidirectional"))
      (node (ref "U12") (pin "P$6") (pinfunction "REF2_P$6") (pintype "bidirectional"))
      (node (ref "U12") (pin "P$7") (pinfunction "REF1_P$7") (pintype "bidirectional"))
      (node (ref "U13") (pin "P$6") (pinfunction "REF2_P$6") (pintype "bidirectional"))
      (node (ref "U13") (pin "P$7") (pinfunction "REF1_P$7") (pintype "bidirectional"))
      (node (ref "U15") (pin "P$6") (pinfunction "REF2_P$6") (pintype "bidirectional"))
      (node (ref "U15") (pin "P$7") (pinfunction "REF1_P$7") (pintype "bidirectional"))
      (node (ref "U7") (pin "P$6") (pinfunction "REF2_P$6") (pintype "bidirectional"))
      (node (ref "U7") (pin "P$7") (pinfunction "REF1_P$7") (pintype "bidirectional"))
      (node (ref "U8") (pin "P$6") (pinfunction "REF2_P$6") (pintype "bidirectional"))
      (node (ref "U8") (pin "P$7") (pinfunction "REF1_P$7") (pintype "bidirectional"))
    )
    (net (code "13") (name "AD0_VREF*") (class "Default")
      (node (ref "C92") (pin "2") (pinfunction "P$2_2") (pintype "bidirectional"))
      (node (ref "C97") (pin "2") (pinfunction "P$2_2") (pintype "bidirectional"))
      (node (ref "CON15") (pin "P$10") (pinfunction "10_P$10") (pintype "bidirectional"))
      (node (ref "U16") (pin "P$6") (pinfunction "REF2_P$6") (pintype "bidirectional"))
      (node (ref "U16") (pin "P$7") (pinfunction "REF1_P$7") (pintype "bidirectional"))
      (node (ref "U18") (pin "P$6") (pinfunction "REF2_P$6") (pintype "bidirectional"))
      (node (ref "U18") (pin "P$7") (pinfunction "REF1_P$7") (pintype "bidirectional"))
    )
    (net (code "14") (name "AD1_DRDY") (class "Default")
      (node (ref "IC1") (pin "25") (pinfunction "DRDY_25") (pintype "passive"))
      (node (ref "U29") (pin "D11") (pinfunction "D11_D11") (pintype "bidirectional"))
    )
    (net (code "15") (name "AD1_M") (class "Default")
      (node (ref "IC1") (pin "44") (pinfunction "MUXOUTP_44") (pintype "passive"))
      (node (ref "R97") (pin "1") (pinfunction "P$1_1") (pintype "bidirectional"))
    )
    (net (code "16") (name "AD1_MISO") (class "Default")
      (node (ref "IC1") (pin "24") (pinfunction "DOUT_24") (pintype "passive"))
      (node (ref "U29") (pin "D12") (pinfunction "D12_D12") (pintype "bidirectional"))
    )
    (net (code "17") (name "AD1_MOSI") (class "Default")
      (node (ref "IC1") (pin "23") (pinfunction "DIN_23") (pintype "passive"))
      (node (ref "U29") (pin "D13") (pinfunction "D13_D13") (pintype "bidirectional"))
    )
    (net (code "18") (name "AD1_P") (class "Default")
      (node (ref "C178") (pin "2") (pinfunction "P$2_2") (pintype "bidirectional"))
      (node (ref "IC1") (pin "42") (pinfunction "ADCINP_42") (pintype "passive"))
      (node (ref "R98") (pin "2") (pinfunction "P$2_2") (pintype "bidirectional"))
      (node (ref "U24") (pin "P$4") (pinfunction "OUT_P$4") (pintype "bidirectional"))
    )
    (net (code "19") (name "AD1_RST") (class "Default")
      (node (ref "IC1") (pin "11") (pinfunction "RESET_11") (pintype "passive"))
      (node (ref "U29") (pin "SCL") (pinfunction "SCL_SCL") (pintype "bidirectional"))
    )
    (net (code "20") (name "AD1_SCLK") (class "Default")
      (node (ref "IC1") (pin "22") (pinfunction "SCLK_22") (pintype "passive"))
      (node (ref "U29") (pin "SDA") (pinfunction "SDA_SDA") (pintype "bidirectional"))
    )
    (net (code "21") (name "AD1_SS") (class "Default")
      (node (ref "IC1") (pin "27") (pinfunction "CS_27") (pintype "passive"))
      (node (ref "U29") (pin "D10") (pinfunction "D10_D10") (pintype "bidirectional"))
    )
    (net (code "22") (name "AD1_V") (class "Default")
      (node (ref "C176") (pin "P$1") (pinfunction "P$1_P$1") (pintype "bidirectional"))
      (node (ref "C177") (pin "2") (pinfunction "P$2_2") (pintype "bidirectional"))
      (node (ref "IC1") (pin "31") (pinfunction "VREFP_31") (pintype "passive"))
      (node (ref "J31") (pin "P$2") (pinfunction "2_P$2") (pintype "bidirectional"))
    )
    (net (code "23") (name "ADC_IN0") (class "Default")
      (node (ref "J47") (pin "2") (pinfunction "2_2") (pintype "passive"))
    )
    (net (code "24") (name "ADC_IN1") (class "Default")
      (node (ref "J47") (pin "3") (pinfunction "3_3") (pintype "passive"))
    )
    (net (code "25") (name "ADC_IN2") (class "Default")
      (node (ref "J47") (pin "4") (pinfunction "4_4") (pintype "passive"))
    )
    (net (code "26") (name "ADC_IN3") (class "Default")
      (node (ref "J47") (pin "5") (pinfunction "5_5") (pintype "passive"))
    )
    (net (code "27") (name "ADC_IN4") (class "Default")
      (node (ref "J47") (pin "6") (pinfunction "6_6") (pintype "passive"))
    )
    (net (code "28") (name "ADC_IN5") (class "Default")
      (node (ref "J47") (pin "7") (pinfunction "7_7") (pintype "passive"))
    )
    (net (code "29") (name "ADC_IN6") (class "Default")
      (node (ref "J47") (pin "8") (pinfunction "8_8") (pintype "passive"))
    )
    (net (code "30") (name "ADC_IN7") (class "Default")
      (node (ref "J47") (pin "9") (pinfunction "9_9") (pintype "passive"))
    )
    (net (code "31") (name "ADC_VCC") (class "Default")
      (node (ref "J47") (pin "1") (pinfunction "1_1") (pintype "passive"))
    )
    (net (code "32") (name "AN0") (class "Default")
      (node (ref "C100") (pin "2") (pinfunction "P$2_2") (pintype "bidirectional"))
      (node (ref "IC1") (pin "45") (pinfunction "AIN7_45") (pintype "passive"))
      (node (ref "R41") (pin "2") (pinfunction "P$2_2") (pintype "bidirectional"))
      (node (ref "R43") (pin "1") (pinfunction "P$1_1") (pintype "bidirectional"))
    )
    (net (code "33") (name "AN1") (class "Default")
      (node (ref "C106") (pin "2") (pinfunction "P$2_2") (pintype "bidirectional"))
      (node (ref "IC1") (pin "46") (pinfunction "AIN6_46") (pintype "passive"))
      (node (ref "R46") (pin "2") (pinfunction "P$2_2") (pintype "bidirectional"))
      (node (ref "R48") (pin "1") (pinfunction "P$1_1") (pintype "bidirectional"))
    )
    (net (code "34") (name "AN2") (class "Default")
      (node (ref "C112") (pin "2") (pinfunction "P$2_2") (pintype "bidirectional"))
      (node (ref "IC1") (pin "47") (pinfunction "AIN5_47") (pintype "passive"))
      (node (ref "R53") (pin "2") (pinfunction "P$2_2") (pintype "bidirectional"))
      (node (ref "R55") (pin "1") (pinfunction "P$1_1") (pintype "bidirectional"))
    )
    (net (code "35") (name "AN3") (class "Default")
      (node (ref "C115") (pin "2") (pinfunction "P$2_2") (pintype "bidirectional"))
      (node (ref "IC1") (pin "48") (pinfunction "AIN4_48") (pintype "passive"))
      (node (ref "R59") (pin "2") (pinfunction "P$2_2") (pintype "bidirectional"))
      (node (ref "R63") (pin "1") (pinfunction "P$1_1") (pintype "bidirectional"))
    )
    (net (code "36") (name "AN4") (class "Default")
      (node (ref "C122") (pin "2") (pinfunction "P$2_2") (pintype "bidirectional"))
      (node (ref "IC1") (pin "1") (pinfunction "AIN3_1") (pintype "passive"))
      (node (ref "R66") (pin "2") (pinfunction "P$2_2") (pintype "bidirectional"))
      (node (ref "R68") (pin "1") (pinfunction "P$1_1") (pintype "bidirectional"))
    )
    (net (code "37") (name "AN5") (class "Default")
      (node (ref "C129") (pin "2") (pinfunction "P$2_2") (pintype "bidirectional"))
      (node (ref "IC1") (pin "2") (pinfunction "AIN2_2") (pintype "passive"))
      (node (ref "R74") (pin "2") (pinfunction "P$2_2") (pintype "bidirectional"))
      (node (ref "R76") (pin "1") (pinfunction "P$1_1") (pintype "bidirectional"))
    )
    (net (code "38") (name "AN6") (class "Default")
      (node (ref "C132") (pin "2") (pinfunction "P$2_2") (pintype "bidirectional"))
      (node (ref "IC1") (pin "3") (pinfunction "AIN1_3") (pintype "passive"))
      (node (ref "R79") (pin "2") (pinfunction "P$2_2") (pintype "bidirectional"))
      (node (ref "R81") (pin "1") (pinfunction "P$1_1") (pintype "bidirectional"))
    )
    (net (code "39") (name "AN7") (class "Default")
      (node (ref "C135") (pin "2") (pinfunction "P$2_2") (pintype "bidirectional"))
      (node (ref "IC1") (pin "4") (pinfunction "AIN0_4") (pintype "passive"))
      (node (ref "R84") (pin "2") (pinfunction "P$2_2") (pintype "bidirectional"))
      (node (ref "R86") (pin "1") (pinfunction "P$1_1") (pintype "bidirectional"))
    )
    (net (code "40") (name "ARDUINO_A0") (class "Default")
      (node (ref "U29") (pin "A0") (pinfunction "A0_A0") (pintype "bidirectional"))
    )
    (net (code "41") (name "ARDUINO_A1") (class "Default")
      (node (ref "U29") (pin "A1") (pinfunction "A1_A1") (pintype "bidirectional"))
    )
    (net (code "42") (name "ARDUINO_A2") (class "Default")
      (node (ref "U29") (pin "A2") (pinfunction "A2_A2") (pintype "bidirectional"))
    )
    (net (code "43") (name "ARDUINO_A3") (class "Default")
      (node (ref "U29") (pin "A3") (pinfunction "A3_A3") (pintype "bidirectional"))
    )
    (net (code "44") (name "ARDUINO_A4") (class "Default")
      (node (ref "U29") (pin "A4") (pinfunction "A4/SDA_A4") (pintype "bidirectional"))
    )
    (net (code "45") (name "ARDUINO_A5") (class "Default")
      (node (ref "U29") (pin "A5") (pinfunction "A5/SCL_A5") (pintype "bidirectional"))
    )
    (net (code "46") (name "BALISE") (class "Default")
      (node (ref "U29") (pin "D3") (pinfunction "D3_D3") (pintype "bidirectional"))
      (node (ref "U31") (pin "P$9") (pinfunction "A8_P$9") (pintype "bidirectional"))
    )
    (net (code "47") (name "BALISE°") (class "Default")
      (node (ref "CON36") (pin "5") (pinfunction "5_5") (pintype "bidirectional"))
      (node (ref "U31") (pin "P$12") (pinfunction "B8_P$12") (pintype "bidirectional"))
    )
    (net (code "48") (name "BUZZER") (class "Default")
      (node (ref "U29") (pin "D8") (pinfunction "D8_D8") (pintype "bidirectional"))
      (node (ref "U31") (pin "P$3") (pinfunction "A2_P$3") (pintype "bidirectional"))
    )
    (net (code "49") (name "BUZZER°") (class "Default")
      (node (ref "T1") (pin "P$1") (pinfunction "G_P$1") (pintype "bidirectional"))
      (node (ref "U31") (pin "P$18") (pinfunction "B2_P$18") (pintype "bidirectional"))
    )
    (net (code "50") (name "D3V3") (class "Default")
      (node (ref "C160") (pin "2") (pinfunction "P$2_2") (pintype "bidirectional"))
      (node (ref "C167") (pin "2") (pinfunction "P$2_2") (pintype "bidirectional"))
      (node (ref "C181") (pin "2") (pinfunction "P$2_2") (pintype "bidirectional"))
      (node (ref "C183") (pin "2") (pinfunction "P$2_2") (pintype "bidirectional"))
      (node (ref "C185") (pin "2") (pinfunction "P$2_2") (pintype "bidirectional"))
      (node (ref "C187") (pin "2") (pinfunction "P$2_2") (pintype "bidirectional"))
      (node (ref "C189") (pin "2") (pinfunction "P$2_2") (pintype "bidirectional"))
      (node (ref "C191") (pin "2") (pinfunction "P$2_2") (pintype "bidirectional"))
      (node (ref "C193") (pin "2") (pinfunction "P$2_2") (pintype "bidirectional"))
      (node (ref "C219") (pin "2") (pinfunction "P$2_2") (pintype "bidirectional"))
      (node (ref "C3") (pin "1") (pinfunction "P$1_1") (pintype "bidirectional"))
      (node (ref "CON57") (pin "29") (pinfunction "29_29") (pintype "bidirectional"))
      (node (ref "CON58") (pin "29") (pinfunction "29_29") (pintype "bidirectional"))
      (node (ref "IC1") (pin "10") (pinfunction "PWDN_10") (pintype "passive"))
      (node (ref "IC1") (pin "26") (pinfunction "START_26") (pintype "passive"))
      (node (ref "IC1") (pin "28") (pinfunction "DVDD_28") (pintype "passive"))
      (node (ref "IC2") (pin "10") (pinfunction "CLKDIV_10") (pintype "passive"))
      (node (ref "IC2") (pin "22") (pinfunction "IOVDD_22") (pintype "passive"))
      (node (ref "IC2") (pin "23") (pinfunction "IOVDD_23") (pintype "passive"))
      (node (ref "IC2") (pin "32") (pinfunction "FORMAT0_32") (pintype "passive"))
      (node (ref "IC2") (pin "35") (pinfunction "PWDN8_35") (pintype "passive"))
      (node (ref "IC2") (pin "36") (pinfunction "PWDN7_36") (pintype "passive"))
      (node (ref "IC2") (pin "37") (pinfunction "PWDN6_37") (pintype "passive"))
      (node (ref "IC2") (pin "38") (pinfunction "PWDN5_38") (pintype "passive"))
      (node (ref "IC2") (pin "39") (pinfunction "PWDN4_39") (pintype "passive"))
      (node (ref "IC2") (pin "40") (pinfunction "PWDN3_40") (pintype "passive"))
      (node (ref "IC2") (pin "41") (pinfunction "PWDN2_41") (pintype "passive"))
      (node (ref "IC2") (pin "42") (pinfunction "PWDN1_42") (pintype "passive"))
      (node (ref "J28") (pin "P$2") (pinfunction "2_P$2") (pintype "bidirectional"))
      (node (ref "J34") (pin "P$2") (pinfunction "2_P$2") (pintype "bidirectional"))
      (node (ref "J36") (pin "P$2") (pinfunction "2_P$2") (pintype "bidirectional"))
      (node (ref "J38") (pin "P$2") (pinfunction "2_P$2") (pintype "bidirectional"))
      (node (ref "J40") (pin "P$2") (pinfunction "2_P$2") (pintype "bidirectional"))
      (node (ref "J42") (pin "P$2") (pinfunction "2_P$2") (pintype "bidirectional"))
      (node (ref "J44") (pin "P$2") (pinfunction "2_P$2") (pintype "bidirectional"))
      (node (ref "J46") (pin "P$2") (pinfunction "2_P$2") (pintype "bidirectional"))
      (node (ref "R100") (pin "2") (pinfunction "P$2_2") (pintype "bidirectional"))
      (node (ref "R101") (pin "2") (pinfunction "P$2_2") (pintype "bidirectional"))
      (node (ref "R102") (pin "2") (pinfunction "P$2_2") (pintype "bidirectional"))
      (node (ref "R103") (pin "2") (pinfunction "P$2_2") (pintype "bidirectional"))
      (node (ref "R104") (pin "2") (pinfunction "P$2_2") (pintype "bidirectional"))
      (node (ref "R105") (pin "2") (pinfunction "P$2_2") (pintype "bidirectional"))
      (node (ref "R106") (pin "2") (pinfunction "P$2_2") (pintype "bidirectional"))
      (node (ref "R99") (pin "2") (pinfunction "P$2_2") (pintype "bidirectional"))
      (node (ref "U1") (pin "16") (pinfunction "VCC_16") (pintype "bidirectional"))
      (node (ref "U25") (pin "P$10") (pinfunction "OE_P$10") (pintype "bidirectional"))
      (node (ref "U25") (pin "P$2") (pinfunction "VA_P$2") (pintype "bidirectional"))
      (node (ref "U26") (pin "P$10") (pinfunction "OE_P$10") (pintype "bidirectional"))
      (node (ref "U26") (pin "P$2") (pinfunction "VA_P$2") (pintype "bidirectional"))
      (node (ref "U27") (pin "P$10") (pinfunction "OE_P$10") (pintype "bidirectional"))
      (node (ref "U27") (pin "P$2") (pinfunction "VA_P$2") (pintype "bidirectional"))
      (node (ref "U28") (pin "P$10") (pinfunction "OE_P$10") (pintype "bidirectional"))
      (node (ref "U28") (pin "P$2") (pinfunction "VA_P$2") (pintype "bidirectional"))
      (node (ref "U30") (pin "P$10") (pinfunction "OE_P$10") (pintype "bidirectional"))
      (node (ref "U30") (pin "P$2") (pinfunction "VA_P$2") (pintype "bidirectional"))
      (node (ref "U31") (pin "P$10") (pinfunction "OE_P$10") (pintype "bidirectional"))
      (node (ref "U31") (pin "P$2") (pinfunction "VA_P$2") (pintype "bidirectional"))
      (node (ref "U32") (pin "P$10") (pinfunction "OE_P$10") (pintype "bidirectional"))
      (node (ref "U32") (pin "P$2") (pinfunction "VA_P$2") (pintype "bidirectional"))
      (node (ref "U38") (pin "4") (pinfunction "EN_4") (pintype "bidirectional"))
      (node (ref "U38") (pin "6") (pinfunction "VI_6") (pintype "bidirectional"))
    )
    (net (code "51") (name "DM2") (class "Default")
      (node (ref "CON54") (pin "2") (pinfunction "D-_2") (pintype "bidirectional"))
      (node (ref "U20") (pin "3") (pinfunction "USBDM3_3") (pintype "bidirectional"))
    )
    (net (code "52") (name "DM3") (class "Default")
      (node (ref "CON55") (pin "2") (pinfunction "D-_2") (pintype "bidirectional"))
      (node (ref "U20") (pin "6") (pinfunction "USBDM4_6") (pintype "bidirectional"))
    )
    (net (code "53") (name "DP2") (class "Default")
      (node (ref "CON54") (pin "3") (pinfunction "D+_3") (pintype "bidirectional"))
      (node (ref "U20") (pin "4") (pinfunction "USBDP3_4") (pintype "bidirectional"))
    )
    (net (code "54") (name "DP3") (class "Default")
      (node (ref "CON55") (pin "3") (pinfunction "D+_3") (pintype "bidirectional"))
      (node (ref "U20") (pin "7") (pinfunction "USBDP4_7") (pintype "bidirectional"))
    )
    (net (code "55") (name "ESC0_CS") (class "Default")
      (node (ref "C96") (pin "2") (pinfunction "P$2_2") (pintype "bidirectional"))
      (node (ref "CON16") (pin "P$7") (pinfunction "7_P$7") (pintype "bidirectional"))
      (node (ref "IC2") (pin "63") (pinfunction "AINP3_63") (pintype "passive"))
    )
    (net (code "56") (name "ESC0_CS*") (class "Default")
      (node (ref "CON15") (pin "P$7") (pinfunction "7_P$7") (pintype "bidirectional"))
      (node (ref "R35") (pin "2") (pinfunction "P$2_2") (pintype "bidirectional"))
    )
    (net (code "57") (name "ESC0_DIR") (class "Default")
      (node (ref "U29") (pin "D5") (pinfunction "D5_D5") (pintype "bidirectional"))
      (node (ref "U31") (pin "P$6") (pinfunction "A5_P$6") (pintype "bidirectional"))
    )
    (net (code "58") (name "ESC0_DIR°") (class "Default")
      (node (ref "CON16") (pin "P$3") (pinfunction "3_P$3") (pintype "bidirectional"))
      (node (ref "U31") (pin "P$15") (pinfunction "B5_P$15") (pintype "bidirectional"))
    )
    (net (code "59") (name "ESC0_DIR°*") (class "Default")
      (node (ref "CON15") (pin "P$3") (pinfunction "3_P$3") (pintype "bidirectional"))
      (node (ref "T2") (pin "P$1") (pinfunction "G_P$1") (pintype "bidirectional"))
    )
    (net (code "60") (name "ESC0_PWM") (class "Default")
      (node (ref "U29") (pin "D4") (pinfunction "D4_D4") (pintype "bidirectional"))
      (node (ref "U31") (pin "P$7") (pinfunction "A6_P$7") (pintype "bidirectional"))
    )
    (net (code "61") (name "ESC0_PWM°") (class "Default")
      (node (ref "CON16") (pin "P$5") (pinfunction "5_P$5") (pintype "bidirectional"))
      (node (ref "U31") (pin "P$14") (pinfunction "B6_P$14") (pintype "bidirectional"))
    )
    (net (code "62") (name "ESC0_PWM°*") (class "Default")
      (node (ref "CON15") (pin "P$5") (pinfunction "5_P$5") (pintype "bidirectional"))
      (node (ref "U17") (pin "PWM") (pinfunction "PWM_PWM") (pintype "bidirectional"))
    )
    (net (code "63") (name "ESC1_CS") (class "Default")
      (node (ref "C95") (pin "2") (pinfunction "P$2_2") (pintype "bidirectional"))
      (node (ref "CON16") (pin "P$8") (pinfunction "8_P$8") (pintype "bidirectional"))
      (node (ref "IC2") (pin "1") (pinfunction "AINP2_1") (pintype "passive"))
    )
    (net (code "64") (name "ESC1_CS*") (class "Default")
      (node (ref "CON15") (pin "P$8") (pinfunction "8_P$8") (pintype "bidirectional"))
      (node (ref "R37") (pin "2") (pinfunction "P$2_2") (pintype "bidirectional"))
    )
    (net (code "65") (name "ESC1_DIR") (class "Default")
      (node (ref "U29") (pin "D6") (pinfunction "D6_D6") (pintype "bidirectional"))
      (node (ref "U31") (pin "P$5") (pinfunction "A4_P$5") (pintype "bidirectional"))
    )
    (net (code "66") (name "ESC1_DIR°") (class "Default")
      (node (ref "CON16") (pin "P$4") (pinfunction "4_P$4") (pintype "bidirectional"))
      (node (ref "U31") (pin "P$16") (pinfunction "B4_P$16") (pintype "bidirectional"))
    )
    (net (code "67") (name "ESC1_DIR°*") (class "Default")
      (node (ref "CON15") (pin "P$4") (pinfunction "4_P$4") (pintype "bidirectional"))
      (node (ref "T3") (pin "P$1") (pinfunction "G_P$1") (pintype "bidirectional"))
    )
    (net (code "68") (name "ESC1_PWM") (class "Default")
      (node (ref "U29") (pin "D7") (pinfunction "D7_D7") (pintype "bidirectional"))
      (node (ref "U31") (pin "P$4") (pinfunction "A3_P$4") (pintype "bidirectional"))
    )
    (net (code "69") (name "ESC1_PWM°") (class "Default")
      (node (ref "CON16") (pin "P$1") (pinfunction "1_P$1") (pintype "bidirectional"))
      (node (ref "U31") (pin "P$17") (pinfunction "B3_P$17") (pintype "bidirectional"))
    )
    (net (code "70") (name "ESC1_PWM°*") (class "Default")
      (node (ref "CON15") (pin "P$1") (pinfunction "1_P$1") (pintype "bidirectional"))
      (node (ref "U19") (pin "PWM") (pinfunction "PWM_PWM") (pintype "bidirectional"))
    )
    (net (code "71") (name "ESC_PWR") (class "Default")
      (node (ref "C91") (pin "+") (pinfunction "+_+") (pintype "bidirectional"))
      (node (ref "J24") (pin "P$2") (pinfunction "2_P$2") (pintype "bidirectional"))
      (node (ref "J25") (pin "P$2") (pinfunction "2_P$2") (pintype "bidirectional"))
      (node (ref "R36") (pin "P$2") (pinfunction "P$2_P$2") (pintype "bidirectional"))
      (node (ref "R38") (pin "P$2") (pinfunction "P$2_P$2") (pintype "bidirectional"))
      (node (ref "U16") (pin "P$3") (pinfunction "IN-_P$3") (pintype "bidirectional"))
      (node (ref "U18") (pin "P$2") (pinfunction "IN+_P$2") (pintype "bidirectional"))
    )
    (net (code "72") (name "GND") (class "Default")
      (node (ref "C1") (pin "2") (pinfunction "P$2_2") (pintype "bidirectional"))
      (node (ref "C10") (pin "2") (pinfunction "P$2_2") (pintype "bidirectional"))
      (node (ref "C100") (pin "1") (pinfunction "P$1_1") (pintype "bidirectional"))
      (node (ref "C101") (pin "1") (pinfunction "P$1_1") (pintype "bidirectional"))
      (node (ref "C102") (pin "1") (pinfunction "P$1_1") (pintype "bidirectional"))
      (node (ref "C103") (pin "1") (pinfunction "P$1_1") (pintype "bidirectional"))
      (node (ref "C104") (pin "1") (pinfunction "P$1_1") (pintype "bidirectional"))
      (node (ref "C105") (pin "1") (pinfunction "P$1_1") (pintype "bidirectional"))
      (node (ref "C106") (pin "1") (pinfunction "P$1_1") (pintype "bidirectional"))
      (node (ref "C107") (pin "1") (pinfunction "P$1_1") (pintype "bidirectional"))
      (node (ref "C108") (pin "1") (pinfunction "P$1_1") (pintype "bidirectional"))
      (node (ref "C109") (pin "1") (pinfunction "P$1_1") (pintype "bidirectional"))
      (node (ref "C11") (pin "P$2") (pinfunction "P$2_P$2") (pintype "bidirectional"))
      (node (ref "C110") (pin "1") (pinfunction "P$1_1") (pintype "bidirectional"))
      (node (ref "C111") (pin "1") (pinfunction "P$1_1") (pintype "bidirectional"))
      (node (ref "C112") (pin "1") (pinfunction "P$1_1") (pintype "bidirectional"))
      (node (ref "C113") (pin "1") (pinfunction "P$1_1") (pintype "bidirectional"))
      (node (ref "C114") (pin "1") (pinfunction "P$1_1") (pintype "bidirectional"))
      (node (ref "C115") (pin "1") (pinfunction "P$1_1") (pintype "bidirectional"))
      (node (ref "C116") (pin "1") (pinfunction "P$1_1") (pintype "bidirectional"))
      (node (ref "C117") (pin "1") (pinfunction "P$1_1") (pintype "bidirectional"))
      (node (ref "C118") (pin "1") (pinfunction "P$1_1") (pintype "bidirectional"))
      (node (ref "C119") (pin "1") (pinfunction "P$1_1") (pintype "bidirectional"))
      (node (ref "C12") (pin "-") (pinfunction "-_-") (pintype "bidirectional"))
      (node (ref "C120") (pin "1") (pinfunction "P$1_1") (pintype "bidirectional"))
      (node (ref "C121") (pin "1") (pinfunction "P$1_1") (pintype "bidirectional"))
      (node (ref "C122") (pin "1") (pinfunction "P$1_1") (pintype "bidirectional"))
      (node (ref "C123") (pin "1") (pinfunction "P$1_1") (pintype "bidirectional"))
      (node (ref "C124") (pin "1") (pinfunction "P$1_1") (pintype "bidirectional"))
      (node (ref "C125") (pin "1") (pinfunction "P$1_1") (pintype "bidirectional"))
      (node (ref "C126") (pin "1") (pinfunction "P$1_1") (pintype "bidirectional"))
      (node (ref "C127") (pin "1") (pinfunction "P$1_1") (pintype "bidirectional"))
      (node (ref "C128") (pin "1") (pinfunction "P$1_1") (pintype "bidirectional"))
      (node (ref "C129") (pin "1") (pinfunction "P$1_1") (pintype "bidirectional"))
      (node (ref "C13") (pin "P$2") (pinfunction "P$2_P$2") (pintype "bidirectional"))
      (node (ref "C130") (pin "1") (pinfunction "P$1_1") (pintype "bidirectional"))
      (node (ref "C131") (pin "1") (pinfunction "P$1_1") (pintype "bidirectional"))
      (node (ref "C132") (pin "1") (pinfunction "P$1_1") (pintype "bidirectional"))
      (node (ref "C133") (pin "1") (pinfunction "P$1_1") (pintype "bidirectional"))
      (node (ref "C134") (pin "1") (pinfunction "P$1_1") (pintype "bidirectional"))
      (node (ref "C135") (pin "1") (pinfunction "P$1_1") (pintype "bidirectional"))
      (node (ref "C136") (pin "1") (pinfunction "P$1_1") (pintype "bidirectional"))
      (node (ref "C137") (pin "1") (pinfunction "P$1_1") (pintype "bidirectional"))
      (node (ref "C138") (pin "1") (pinfunction "P$1_1") (pintype "bidirectional"))
      (node (ref "C139") (pin "1") (pinfunction "P$1_1") (pintype "bidirectional"))
      (node (ref "C14") (pin "P$2") (pinfunction "P$2_P$2") (pintype "bidirectional"))
      (node (ref "C140") (pin "1") (pinfunction "P$1_1") (pintype "bidirectional"))
      (node (ref "C141") (pin "1") (pinfunction "P$1_1") (pintype "bidirectional"))
      (node (ref "C142") (pin "1") (pinfunction "P$1_1") (pintype "bidirectional"))
      (node (ref "C143") (pin "1") (pinfunction "P$1_1") (pintype "bidirectional"))
      (node (ref "C144") (pin "1") (pinfunction "P$1_1") (pintype "bidirectional"))
      (node (ref "C145") (pin "1") (pinfunction "P$1_1") (pintype "bidirectional"))
      (node (ref "C146") (pin "1") (pinfunction "P$1_1") (pintype "bidirectional"))
      (node (ref "C147") (pin "1") (pinfunction "P$1_1") (pintype "bidirectional"))
      (node (ref "C148") (pin "P$1") (pinfunction "P$1_P$1") (pintype "bidirectional"))
      (node (ref "C149") (pin "1") (pinfunction "P$1_1") (pintype "bidirectional"))
      (node (ref "C15") (pin "-") (pinfunction "-_-") (pintype "bidirectional"))
      (node (ref "C150") (pin "1") (pinfunction "P$1_1") (pintype "bidirectional"))
      (node (ref "C151") (pin "1") (pinfunction "P$1_1") (pintype "bidirectional"))
      (node (ref "C152") (pin "1") (pinfunction "P$1_1") (pintype "bidirectional"))
      (node (ref "C153") (pin "P$1") (pinfunction "P$1_P$1") (pintype "bidirectional"))
      (node (ref "C154") (pin "1") (pinfunction "P$1_1") (pintype "bidirectional"))
      (node (ref "C155") (pin "1") (pinfunction "P$1_1") (pintype "bidirectional"))
      (node (ref "C156") (pin "1") (pinfunction "P$1_1") (pintype "bidirectional"))
      (node (ref "C157") (pin "1") (pinfunction "P$1_1") (pintype "bidirectional"))
      (node (ref "C158") (pin "P$1") (pinfunction "P$1_P$1") (pintype "bidirectional"))
      (node (ref "C159") (pin "1") (pinfunction "P$1_1") (pintype "bidirectional"))
      (node (ref "C16") (pin "P$2") (pinfunction "P$2_P$2") (pintype "bidirectional"))
      (node (ref "C160") (pin "1") (pinfunction "P$1_1") (pintype "bidirectional"))
      (node (ref "C161") (pin "1") (pinfunction "P$1_1") (pintype "bidirectional"))
      (node (ref "C162") (pin "1") (pinfunction "P$1_1") (pintype "bidirectional"))
      (node (ref "C163") (pin "1") (pinfunction "P$1_1") (pintype "bidirectional"))
      (node (ref "C164") (pin "1") (pinfunction "P$1_1") (pintype "bidirectional"))
      (node (ref "C165") (pin "1") (pinfunction "P$1_1") (pintype "bidirectional"))
      (node (ref "C166") (pin "P$1") (pinfunction "P$1_P$1") (pintype "bidirectional"))
      (node (ref "C167") (pin "1") (pinfunction "P$1_1") (pintype "bidirectional"))
      (node (ref "C168") (pin "1") (pinfunction "P$1_1") (pintype "bidirectional"))
      (node (ref "C169") (pin "1") (pinfunction "P$1_1") (pintype "bidirectional"))
      (node (ref "C17") (pin "P$2") (pinfunction "P$2_P$2") (pintype "bidirectional"))
      (node (ref "C170") (pin "1") (pinfunction "P$1_1") (pintype "bidirectional"))
      (node (ref "C171") (pin "1") (pinfunction "P$1_1") (pintype "bidirectional"))
      (node (ref "C172") (pin "1") (pinfunction "P$1_1") (pintype "bidirectional"))
      (node (ref "C173") (pin "1") (pinfunction "P$1_1") (pintype "bidirectional"))
      (node (ref "C174") (pin "1") (pinfunction "P$1_1") (pintype "bidirectional"))
      (node (ref "C175") (pin "P$2") (pinfunction "P$2_P$2") (pintype "bidirectional"))
      (node (ref "C176") (pin "P$2") (pinfunction "P$2_P$2") (pintype "bidirectional"))
      (node (ref "C177") (pin "1") (pinfunction "P$1_1") (pintype "bidirectional"))
      (node (ref "C178") (pin "1") (pinfunction "P$1_1") (pintype "bidirectional"))
      (node (ref "C179") (pin "P$2") (pinfunction "P$2_P$2") (pintype "bidirectional"))
      (node (ref "C18") (pin "-") (pinfunction "-_-") (pintype "bidirectional"))
      (node (ref "C180") (pin "P$2") (pinfunction "P$2_P$2") (pintype "bidirectional"))
      (node (ref "C181") (pin "1") (pinfunction "P$1_1") (pintype "bidirectional"))
      (node (ref "C182") (pin "1") (pinfunction "P$1_1") (pintype "bidirectional"))
      (node (ref "C183") (pin "1") (pinfunction "P$1_1") (pintype "bidirectional"))
      (node (ref "C184") (pin "1") (pinfunction "P$1_1") (pintype "bidirectional"))
      (node (ref "C185") (pin "1") (pinfunction "P$1_1") (pintype "bidirectional"))
      (node (ref "C186") (pin "1") (pinfunction "P$1_1") (pintype "bidirectional"))
      (node (ref "C187") (pin "1") (pinfunction "P$1_1") (pintype "bidirectional"))
      (node (ref "C188") (pin "1") (pinfunction "P$1_1") (pintype "bidirectional"))
      (node (ref "C189") (pin "1") (pinfunction "P$1_1") (pintype "bidirectional"))
      (node (ref "C19") (pin "2") (pinfunction "P$2_2") (pintype "bidirectional"))
      (node (ref "C190") (pin "1") (pinfunction "P$1_1") (pintype "bidirectional"))
      (node (ref "C191") (pin "1") (pinfunction "P$1_1") (pintype "bidirectional"))
      (node (ref "C192") (pin "1") (pinfunction "P$1_1") (pintype "bidirectional"))
      (node (ref "C193") (pin "1") (pinfunction "P$1_1") (pintype "bidirectional"))
      (node (ref "C194") (pin "1") (pinfunction "P$1_1") (pintype "bidirectional"))
      (node (ref "C195") (pin "1") (pinfunction "P$1_1") (pintype "bidirectional"))
      (node (ref "C196") (pin "P$2") (pinfunction "P$2_P$2") (pintype "bidirectional"))
      (node (ref "C197") (pin "P$2") (pinfunction "P$2_P$2") (pintype "bidirectional"))
      (node (ref "C198") (pin "P$2") (pinfunction "P$2_P$2") (pintype "bidirectional"))
      (node (ref "C199") (pin "P$2") (pinfunction "P$2_P$2") (pintype "bidirectional"))
      (node (ref "C2") (pin "-") (pinfunction "-_-") (pintype "bidirectional"))
      (node (ref "C20") (pin "P$2") (pinfunction "P$2_P$2") (pintype "bidirectional"))
      (node (ref "C21") (pin "P$2") (pinfunction "P$2_P$2") (pintype "bidirectional"))
      (node (ref "C216") (pin "1") (pinfunction "P$1_1") (pintype "bidirectional"))
      (node (ref "C217") (pin "1") (pinfunction "P$1_1") (pintype "bidirectional"))
      (node (ref "C219") (pin "1") (pinfunction "P$1_1") (pintype "bidirectional"))
      (node (ref "C22") (pin "-") (pinfunction "-_-") (pintype "bidirectional"))
      (node (ref "C220") (pin "P$1") (pinfunction "P$1_P$1") (pintype "bidirectional"))
      (node (ref "C23") (pin "2") (pinfunction "P$2_2") (pintype "bidirectional"))
      (node (ref "C24") (pin "P$2") (pinfunction "P$2_P$2") (pintype "bidirectional"))
      (node (ref "C25") (pin "P$2") (pinfunction "P$2_P$2") (pintype "bidirectional"))
      (node (ref "C26") (pin "-") (pinfunction "-_-") (pintype "bidirectional"))
      (node (ref "C27") (pin "2") (pinfunction "P$2_2") (pintype "bidirectional"))
      (node (ref "C28") (pin "1") (pinfunction "P$1_1") (pintype "bidirectional"))
      (node (ref "C29") (pin "P$1") (pinfunction "P$1_P$1") (pintype "bidirectional"))
      (node (ref "C3") (pin "2") (pinfunction "P$2_2") (pintype "bidirectional"))
      (node (ref "C30") (pin "P$1") (pinfunction "P$1_P$1") (pintype "bidirectional"))
      (node (ref "C31") (pin "P$1") (pinfunction "P$1_P$1") (pintype "bidirectional"))
      (node (ref "C32") (pin "P$1") (pinfunction "P$1_P$1") (pintype "bidirectional"))
      (node (ref "C33") (pin "P$1") (pinfunction "P$1_P$1") (pintype "bidirectional"))
      (node (ref "C34") (pin "P$1") (pinfunction "P$1_P$1") (pintype "bidirectional"))
      (node (ref "C35") (pin "P$1") (pinfunction "P$1_P$1") (pintype "bidirectional"))
      (node (ref "C36") (pin "P$1") (pinfunction "P$1_P$1") (pintype "bidirectional"))
      (node (ref "C37") (pin "1") (pinfunction "P$1_1") (pintype "bidirectional"))
      (node (ref "C38") (pin "P$1") (pinfunction "P$1_P$1") (pintype "bidirectional"))
      (node (ref "C39") (pin "P$1") (pinfunction "P$1_P$1") (pintype "bidirectional"))
      (node (ref "C4") (pin "2") (pinfunction "P$2_2") (pintype "bidirectional"))
      (node (ref "C40") (pin "P$1") (pinfunction "P$1_P$1") (pintype "bidirectional"))
      (node (ref "C41") (pin "P$1") (pinfunction "P$1_P$1") (pintype "bidirectional"))
      (node (ref "C42") (pin "P$1") (pinfunction "P$1_P$1") (pintype "bidirectional"))
      (node (ref "C43") (pin "P$1") (pinfunction "P$1_P$1") (pintype "bidirectional"))
      (node (ref "C44") (pin "P$1") (pinfunction "P$1_P$1") (pintype "bidirectional"))
      (node (ref "C45") (pin "P$1") (pinfunction "P$1_P$1") (pintype "bidirectional"))
      (node (ref "C46") (pin "1") (pinfunction "P$1_1") (pintype "bidirectional"))
      (node (ref "C47") (pin "P$1") (pinfunction "P$1_P$1") (pintype "bidirectional"))
      (node (ref "C48") (pin "P$1") (pinfunction "P$1_P$1") (pintype "bidirectional"))
      (node (ref "C49") (pin "P$1") (pinfunction "P$1_P$1") (pintype "bidirectional"))
      (node (ref "C5") (pin "2") (pinfunction "P$2_2") (pintype "bidirectional"))
      (node (ref "C50") (pin "P$1") (pinfunction "P$1_P$1") (pintype "bidirectional"))
      (node (ref "C51") (pin "P$1") (pinfunction "P$1_P$1") (pintype "bidirectional"))
      (node (ref "C52") (pin "P$1") (pinfunction "P$1_P$1") (pintype "bidirectional"))
      (node (ref "C53") (pin "P$1") (pinfunction "P$1_P$1") (pintype "bidirectional"))
      (node (ref "C54") (pin "P$1") (pinfunction "P$1_P$1") (pintype "bidirectional"))
      (node (ref "C56") (pin "1") (pinfunction "P$1_1") (pintype "bidirectional"))
      (node (ref "C57") (pin "1") (pinfunction "P$1_1") (pintype "bidirectional"))
      (node (ref "C58") (pin "1") (pinfunction "P$1_1") (pintype "bidirectional"))
      (node (ref "C59") (pin "1") (pinfunction "P$1_1") (pintype "bidirectional"))
      (node (ref "C6") (pin "-") (pinfunction "-_-") (pintype "bidirectional"))
      (node (ref "C67") (pin "1") (pinfunction "P$1_1") (pintype "bidirectional"))
      (node (ref "C7") (pin "2") (pinfunction "P$2_2") (pintype "bidirectional"))
      (node (ref "C71") (pin "1") (pinfunction "P$1_1") (pintype "bidirectional"))
      (node (ref "C72") (pin "1") (pinfunction "P$1_1") (pintype "bidirectional"))
      (node (ref "C73") (pin "1") (pinfunction "P$1_1") (pintype "bidirectional"))
      (node (ref "C75") (pin "1") (pinfunction "P$1_1") (pintype "bidirectional"))
      (node (ref "C76") (pin "1") (pinfunction "P$1_1") (pintype "bidirectional"))
      (node (ref "C77") (pin "P$1") (pinfunction "P$1_P$1") (pintype "bidirectional"))
      (node (ref "C78") (pin "P$1") (pinfunction "P$1_P$1") (pintype "bidirectional"))
      (node (ref "C79") (pin "P$1") (pinfunction "P$1_P$1") (pintype "bidirectional"))
      (node (ref "C8") (pin "2") (pinfunction "P$2_2") (pintype "bidirectional"))
      (node (ref "C80") (pin "P$1") (pinfunction "P$1_P$1") (pintype "bidirectional"))
      (node (ref "C81") (pin "P$1") (pinfunction "P$1_P$1") (pintype "bidirectional"))
      (node (ref "C82") (pin "P$1") (pinfunction "P$1_P$1") (pintype "bidirectional"))
      (node (ref "C83") (pin "P$1") (pinfunction "P$1_P$1") (pintype "bidirectional"))
      (node (ref "C84") (pin "P$1") (pinfunction "P$1_P$1") (pintype "bidirectional"))
      (node (ref "C89") (pin "1") (pinfunction "P$1_1") (pintype "bidirectional"))
      (node (ref "C9") (pin "2") (pinfunction "P$2_2") (pintype "bidirectional"))
      (node (ref "C90") (pin "1") (pinfunction "P$1_1") (pintype "bidirectional"))
      (node (ref "C91") (pin "-") (pinfunction "-_-") (pintype "bidirectional"))
      (node (ref "C92") (pin "1") (pinfunction "P$1_1") (pintype "bidirectional"))
      (node (ref "C93") (pin "2") (pinfunction "P$2_2") (pintype "bidirectional"))
      (node (ref "C94") (pin "2") (pinfunction "P$2_2") (pintype "bidirectional"))
      (node (ref "C95") (pin "1") (pinfunction "P$1_1") (pintype "bidirectional"))
      (node (ref "C96") (pin "1") (pinfunction "P$1_1") (pintype "bidirectional"))
      (node (ref "C97") (pin "1") (pinfunction "P$1_1") (pintype "bidirectional"))
      (node (ref "C98") (pin "2") (pinfunction "P$2_2") (pintype "bidirectional"))
      (node (ref "C99") (pin "2") (pinfunction "P$2_2") (pintype "bidirectional"))
      (node (ref "CON1") (pin "P$1") (pinfunction "1_P$1") (pintype "bidirectional"))
      (node (ref "CON14") (pin "P$4") (pinfunction "4_P$4") (pintype "bidirectional"))
      (node (ref "CON15") (pin "P$6") (pinfunction "6_P$6") (pintype "bidirectional"))
      (node (ref "CON16") (pin "P$6") (pinfunction "6_P$6") (pintype "bidirectional"))
      (node (ref "CON17") (pin "P$4") (pinfunction "4_P$4") (pintype "bidirectional"))
      (node (ref "CON18") (pin "1") (pinfunction "1_1") (pintype "bidirectional"))
      (node (ref "CON19") (pin "1") (pinfunction "1_1") (pintype "bidirectional"))
      (node (ref "CON19") (pin "4") (pinfunction "4_4") (pintype "bidirectional"))
      (node (ref "CON2") (pin "P$1") (pinfunction "1_P$1") (pintype "bidirectional"))
      (node (ref "CON20") (pin "1") (pinfunction "1_1") (pintype "bidirectional"))
      (node (ref "CON22") (pin "1") (pinfunction "1_1") (pintype "bidirectional"))
      (node (ref "CON23") (pin "1") (pinfunction "1_1") (pintype "bidirectional"))
      (node (ref "CON25") (pin "1") (pinfunction "1_1") (pintype "bidirectional"))
      (node (ref "CON26") (pin "1") (pinfunction "1_1") (pintype "bidirectional"))
      (node (ref "CON27") (pin "1") (pinfunction "1_1") (pintype "bidirectional"))
      (node (ref "CON27") (pin "4") (pinfunction "4_4") (pintype "bidirectional"))
      (node (ref "CON28") (pin "1") (pinfunction "1_1") (pintype "bidirectional"))
      (node (ref "CON30") (pin "1") (pinfunction "1_1") (pintype "bidirectional"))
      (node (ref "CON31") (pin "1") (pinfunction "1_1") (pintype "bidirectional"))
      (node (ref "CON32") (pin "1") (pinfunction "1_1") (pintype "bidirectional"))
      (node (ref "CON33") (pin "1") (pinfunction "1_1") (pintype "bidirectional"))
      (node (ref "CON35") (pin "1") (pinfunction "1_1") (pintype "bidirectional"))
      (node (ref "CON36") (pin "1") (pinfunction "1_1") (pintype "bidirectional"))
      (node (ref "CON37") (pin "1") (pinfunction "1_1") (pintype "bidirectional"))
      (node (ref "CON39") (pin "1") (pinfunction "1_1") (pintype "bidirectional"))
      (node (ref "CON40") (pin "1") (pinfunction "1_1") (pintype "bidirectional"))
      (node (ref "CON41") (pin "1") (pinfunction "1_1") (pintype "bidirectional"))
      (node (ref "CON42") (pin "1") (pinfunction "1_1") (pintype "bidirectional"))
      (node (ref "CON44") (pin "1") (pinfunction "1_1") (pintype "bidirectional"))
      (node (ref "CON45") (pin "1") (pinfunction "1_1") (pintype "bidirectional"))
      (node (ref "CON46") (pin "1") (pinfunction "1_1") (pintype "bidirectional"))
      (node (ref "CON48") (pin "1") (pinfunction "1_1") (pintype "bidirectional"))
      (node (ref "CON49") (pin "1") (pinfunction "1_1") (pintype "bidirectional"))
      (node (ref "CON50") (pin "1") (pinfunction "1_1") (pintype "bidirectional"))
      (node (ref "CON52") (pin "1") (pinfunction "1_1") (pintype "bidirectional"))
      (node (ref "CON53") (pin "1") (pinfunction "1_1") (pintype "bidirectional"))
      (node (ref "CON54") (pin "4") (pinfunction "GND_4") (pintype "bidirectional"))
      (node (ref "CON54") (pin "GND1") (pinfunction "GND_GND1") (pintype "bidirectional"))
      (node (ref "CON54") (pin "GND2") (pinfunction "GND_GND2") (pintype "bidirectional"))
      (node (ref "CON55") (pin "4") (pinfunction "GND_4") (pintype "bidirectional"))
      (node (ref "CON55") (pin "GND1") (pinfunction "GND_GND1") (pintype "bidirectional"))
      (node (ref "CON55") (pin "GND2") (pinfunction "GND_GND2") (pintype "bidirectional"))
      (node (ref "CON56") (pin "1") (pinfunction "1_1") (pintype "bidirectional"))
      (node (ref "CON57") (pin "12") (pinfunction "12_12") (pintype "bidirectional"))
      (node (ref "CON57") (pin "30") (pinfunction "30_30") (pintype "bidirectional"))
      (node (ref "CON58") (pin "12") (pinfunction "12_12") (pintype "bidirectional"))
      (node (ref "CON58") (pin "30") (pinfunction "30_30") (pintype "bidirectional"))
      (node (ref "CON6") (pin "P$1") (pinfunction "1_P$1") (pintype "bidirectional"))
      (node (ref "CON60") (pin "4") (pinfunction "GND_4") (pintype "bidirectional"))
      (node (ref "CON60") (pin "GND1") (pinfunction "GND_GND1") (pintype "bidirectional"))
      (node (ref "CON60") (pin "GND2") (pinfunction "GND_GND2") (pintype "bidirectional"))
      (node (ref "CON61") (pin "1") (pinfunction "1_1") (pintype "bidirectional"))
      (node (ref "CON62") (pin "1") (pinfunction "1_1") (pintype "bidirectional"))
      (node (ref "CON63") (pin "1") (pinfunction "1_1") (pintype "bidirectional"))
      (node (ref "CON64") (pin "1") (pinfunction "1_1") (pintype "bidirectional"))
      (node (ref "CON7") (pin "P$1") (pinfunction "1_P$1") (pintype "bidirectional"))
      (node (ref "D1") (pin "A") (pinfunction "A_A") (pintype "bidirectional"))
      (node (ref "D2") (pin "A") (pinfunction "A_A") (pintype "bidirectional"))
      (node (ref "D3") (pin "A") (pinfunction "A_A") (pintype "bidirectional"))
      (node (ref "D4") (pin "C") (pinfunction "C_C") (pintype "bidirectional"))
      (node (ref "D5") (pin "C") (pinfunction "C_C") (pintype "bidirectional"))
      (node (ref "D6") (pin "C") (pinfunction "C_C") (pintype "bidirectional"))
      (node (ref "D7") (pin "C") (pinfunction "C_C") (pintype "bidirectional"))
      (node (ref "D8") (pin "C") (pinfunction "C_C") (pintype "bidirectional"))
      (node (ref "IC1") (pin "12") (pinfunction "CLKSEL_12") (pintype "passive"))
      (node (ref "IC1") (pin "29") (pinfunction "DGND_29") (pintype "passive"))
      (node (ref "IC1") (pin "30") (pinfunction "VREFN_30") (pintype "passive"))
      (node (ref "IC1") (pin "32") (pinfunction "AINCOM_32") (pintype "passive"))
      (node (ref "IC1") (pin "41") (pinfunction "ADCINN_41") (pintype "passive"))
      (node (ref "IC1") (pin "5") (pinfunction "AVSS_5") (pintype "passive"))
      (node (ref "IC2") (pin "12") (pinfunction "DIN_12") (pintype "passive"))
      (node (ref "IC2") (pin "21") (pinfunction "DGND_21") (pintype "passive"))
      (node (ref "IC2") (pin "24") (pinfunction "DGND_24") (pintype "passive"))
      (node (ref "IC2") (pin "25") (pinfunction "DGND_25") (pintype "passive"))
      (node (ref "IC2") (pin "30") (pinfunction "FORMAT2_30") (pintype "passive"))
      (node (ref "IC2") (pin "31") (pinfunction "FORMAT1_31") (pintype "passive"))
      (node (ref "IC2") (pin "33") (pinfunction "MODE1_33") (pintype "passive"))
      (node (ref "IC2") (pin "4") (pinfunction "AINN1_4") (pintype "passive"))
      (node (ref "IC2") (pin "43") (pinfunction "AGND_43") (pintype "passive"))
      (node (ref "IC2") (pin "54") (pinfunction "AGND_54") (pintype "passive"))
      (node (ref "IC2") (pin "57") (pinfunction "VREFN_57") (pintype "passive"))
      (node (ref "IC2") (pin "58") (pinfunction "AGND_58") (pintype "passive"))
      (node (ref "IC2") (pin "59") (pinfunction "AGND_59") (pintype "passive"))
      (node (ref "IC2") (pin "6") (pinfunction "AGND_6") (pintype "passive"))
      (node (ref "IC2") (pin "7") (pinfunction "DGND_7") (pintype "passive"))
      (node (ref "IC2") (pin "8") (pinfunction "TEST0_8") (pintype "passive"))
      (node (ref "IC2") (pin "9") (pinfunction "TEST1_9") (pintype "passive"))
      (node (ref "IC2") (pin "POWERPAD") (pinfunction "PGND_POWERPAD") (pintype "bidirectional"))
      (node (ref "IC3") (pin "4") (pinfunction "GND_4") (pintype "passive"))
      (node (ref "IC3") (pin "7") (pinfunction "NC_7") (pintype "passive"))
      (node (ref "IC4") (pin "4") (pinfunction "GND_4") (pintype "passive"))
      (node (ref "IC4") (pin "7") (pinfunction "NC_7") (pintype "passive"))
      (node (ref "J10") (pin "P$1") (pinfunction "1_P$1") (pintype "bidirectional"))
      (node (ref "J16") (pin "P$1") (pinfunction "1_P$1") (pintype "bidirectional"))
      (node (ref "J17") (pin "P$1") (pinfunction "1_P$1") (pintype "bidirectional"))
      (node (ref "J18") (pin "P$1") (pinfunction "1_P$1") (pintype "bidirectional"))
      (node (ref "J19") (pin "P$1") (pinfunction "1_P$1") (pintype "bidirectional"))
      (node (ref "J22") (pin "P$1") (pinfunction "1_P$1") (pintype "bidirectional"))
      (node (ref "J29") (pin "P$1") (pinfunction "1_P$1") (pintype "bidirectional"))
      (node (ref "J47") (pin "10") (pinfunction "10_10") (pintype "passive"))
      (node (ref "J50") (pin "P$1") (pinfunction "1_P$1") (pintype "bidirectional"))
      (node (ref "R107") (pin "2") (pinfunction "P$2_2") (pintype "bidirectional"))
      (node (ref "R108") (pin "2") (pinfunction "P$2_2") (pintype "bidirectional"))
      (node (ref "R109") (pin "2") (pinfunction "P$2_2") (pintype "bidirectional"))
      (node (ref "R110") (pin "2") (pinfunction "P$2_2") (pintype "bidirectional"))
      (node (ref "R16") (pin "2") (pinfunction "P$2_2") (pintype "bidirectional"))
      (node (ref "R18") (pin "2") (pinfunction "P$2_2") (pintype "bidirectional"))
      (node (ref "R20") (pin "2") (pinfunction "P$2_2") (pintype "bidirectional"))
      (node (ref "R26") (pin "2") (pinfunction "P$2_2") (pintype "bidirectional"))
      (node (ref "R28") (pin "2") (pinfunction "P$2_2") (pintype "bidirectional"))
      (node (ref "R30") (pin "2") (pinfunction "P$2_2") (pintype "bidirectional"))
      (node (ref "R33") (pin "2") (pinfunction "P$2_2") (pintype "bidirectional"))
      (node (ref "R43") (pin "2") (pinfunction "P$2_2") (pintype "bidirectional"))
      (node (ref "R45") (pin "P$2") (pinfunction "P$2_P$2") (pintype "bidirectional"))
      (node (ref "R48") (pin "2") (pinfunction "P$2_2") (pintype "bidirectional"))
      (node (ref "R5") (pin "2") (pinfunction "P$2_2") (pintype "bidirectional"))
      (node (ref "R52") (pin "P$2") (pinfunction "P$2_P$2") (pintype "bidirectional"))
      (node (ref "R55") (pin "2") (pinfunction "P$2_2") (pintype "bidirectional"))
      (node (ref "R57") (pin "P$2") (pinfunction "P$2_P$2") (pintype "bidirectional"))
      (node (ref "R6") (pin "2") (pinfunction "P$2_2") (pintype "bidirectional"))
      (node (ref "R63") (pin "2") (pinfunction "P$2_2") (pintype "bidirectional"))
      (node (ref "R65") (pin "P$2") (pinfunction "P$2_P$2") (pintype "bidirectional"))
      (node (ref "R68") (pin "2") (pinfunction "P$2_2") (pintype "bidirectional"))
      (node (ref "R7") (pin "2") (pinfunction "P$2_2") (pintype "bidirectional"))
      (node (ref "R70") (pin "P$2") (pinfunction "P$2_P$2") (pintype "bidirectional"))
      (node (ref "R76") (pin "2") (pinfunction "P$2_2") (pintype "bidirectional"))
      (node (ref "R78") (pin "P$2") (pinfunction "P$2_P$2") (pintype "bidirectional"))
      (node (ref "R8") (pin "2") (pinfunction "P$2_2") (pintype "bidirectional"))
      (node (ref "R81") (pin "2") (pinfunction "P$2_2") (pintype "bidirectional"))
      (node (ref "R83") (pin "P$2") (pinfunction "P$2_P$2") (pintype "bidirectional"))
      (node (ref "R86") (pin "2") (pinfunction "P$2_2") (pintype "bidirectional"))
      (node (ref "R88") (pin "P$2") (pinfunction "P$2_P$2") (pintype "bidirectional"))
      (node (ref "R9") (pin "2") (pinfunction "P$2_2") (pintype "bidirectional"))
      (node (ref "R95") (pin "1") (pinfunction "P$1_1") (pintype "bidirectional"))
      (node (ref "R96") (pin "1") (pinfunction "P$1_1") (pintype "bidirectional"))
      (node (ref "T1") (pin "P$2") (pinfunction "S_P$2") (pintype "bidirectional"))
      (node (ref "T2") (pin "P$2") (pinfunction "S_P$2") (pintype "bidirectional"))
      (node (ref "T3") (pin "P$2") (pinfunction "S_P$2") (pintype "bidirectional"))
      (node (ref "U1") (pin "1") (pinfunction "Y0_1") (pintype "bidirectional"))
      (node (ref "U1") (pin "2") (pinfunction "Y2_2") (pintype "bidirectional"))
      (node (ref "U1") (pin "3") (pinfunction "Y_3") (pintype "bidirectional"))
      (node (ref "U1") (pin "4") (pinfunction "Y3_4") (pintype "bidirectional"))
      (node (ref "U1") (pin "5") (pinfunction "Y1_5") (pintype "bidirectional"))
      (node (ref "U1") (pin "6") (pinfunction "EN_6") (pintype "bidirectional"))
      (node (ref "U1") (pin "7") (pinfunction "GND_7") (pintype "bidirectional"))
      (node (ref "U1") (pin "8") (pinfunction "GND_8") (pintype "bidirectional"))
      (node (ref "U10") (pin "P$11") (pinfunction "M3_P$11") (pintype "bidirectional"))
      (node (ref "U10") (pin "P$23") (pinfunction "GNDD_P$23") (pintype "bidirectional"))
      (node (ref "U10") (pin "P$24") (pinfunction "GNDC_P$24") (pintype "bidirectional"))
      (node (ref "U10") (pin "P$31") (pinfunction "GNDB_P$31") (pintype "bidirectional"))
      (node (ref "U10") (pin "P$32") (pinfunction "GNDA_P$32") (pintype "bidirectional"))
      (node (ref "U10") (pin "P$37") (pinfunction "GND_P$37") (pintype "bidirectional"))
      (node (ref "U10") (pin "P$8") (pinfunction "GND_P$8") (pintype "bidirectional"))
      (node (ref "U10") (pin "P$9") (pinfunction "GND_P$9") (pintype "bidirectional"))
      (node (ref "U11") (pin "P$11") (pinfunction "M3_P$11") (pintype "bidirectional"))
      (node (ref "U11") (pin "P$23") (pinfunction "GNDD_P$23") (pintype "bidirectional"))
      (node (ref "U11") (pin "P$24") (pinfunction "GNDC_P$24") (pintype "bidirectional"))
      (node (ref "U11") (pin "P$31") (pinfunction "GNDB_P$31") (pintype "bidirectional"))
      (node (ref "U11") (pin "P$32") (pinfunction "GNDA_P$32") (pintype "bidirectional"))
      (node (ref "U11") (pin "P$37") (pinfunction "GND_P$37") (pintype "bidirectional"))
      (node (ref "U11") (pin "P$8") (pinfunction "GND_P$8") (pintype "bidirectional"))
      (node (ref "U11") (pin "P$9") (pinfunction "GND_P$9") (pintype "bidirectional"))
      (node (ref "U12") (pin "P$1") (pinfunction "NC_P$1") (pintype "bidirectional"))
      (node (ref "U12") (pin "P$4") (pinfunction "GND_P$4") (pintype "bidirectional"))
      (node (ref "U13") (pin "P$1") (pinfunction "NC_P$1") (pintype "bidirectional"))
      (node (ref "U13") (pin "P$4") (pinfunction "GND_P$4") (pintype "bidirectional"))
      (node (ref "U14") (pin "P$11") (pinfunction "M3_P$11") (pintype "bidirectional"))
      (node (ref "U14") (pin "P$14") (pinfunction "PWMC_P$14") (pintype "bidirectional"))
      (node (ref "U14") (pin "P$16") (pinfunction "PWMD_P$16") (pintype "bidirectional"))
      (node (ref "U14") (pin "P$23") (pinfunction "GNDD_P$23") (pintype "bidirectional"))
      (node (ref "U14") (pin "P$24") (pinfunction "GNDC_P$24") (pintype "bidirectional"))
      (node (ref "U14") (pin "P$31") (pinfunction "GNDB_P$31") (pintype "bidirectional"))
      (node (ref "U14") (pin "P$32") (pinfunction "GNDA_P$32") (pintype "bidirectional"))
      (node (ref "U14") (pin "P$37") (pinfunction "GND_P$37") (pintype "bidirectional"))
      (node (ref "U14") (pin "P$8") (pinfunction "GND_P$8") (pintype "bidirectional"))
      (node (ref "U14") (pin "P$9") (pinfunction "GND_P$9") (pintype "bidirectional"))
      (node (ref "U15") (pin "P$1") (pinfunction "NC_P$1") (pintype "bidirectional"))
      (node (ref "U15") (pin "P$4") (pinfunction "GND_P$4") (pintype "bidirectional"))
      (node (ref "U16") (pin "P$1") (pinfunction "NC_P$1") (pintype "bidirectional"))
      (node (ref "U16") (pin "P$4") (pinfunction "GND_P$4") (pintype "bidirectional"))
      (node (ref "U17") (pin "GND") (pinfunction "GND_GND") (pintype "bidirectional"))
      (node (ref "U18") (pin "P$1") (pinfunction "NC_P$1") (pintype "bidirectional"))
      (node (ref "U18") (pin "P$4") (pinfunction "GND_P$4") (pintype "bidirectional"))
      (node (ref "U19") (pin "GND") (pinfunction "GND_GND") (pintype "bidirectional"))
      (node (ref "U20") (pin "24") (pinfunction "EECS_24") (pintype "bidirectional"))
      (node (ref "U20") (pin "34") (pinfunction "TEST2_34") (pintype "bidirectional"))
      (node (ref "U20") (pin "44") (pinfunction "CLK24_EN_44") (pintype "bidirectional"))
      (node (ref "U20") (pin "GND") (pinfunction "GND_GND") (pintype "bidirectional"))
      (node (ref "U21") (pin "P$1") (pinfunction "GND_P$1") (pintype "bidirectional"))
      (node (ref "U21") (pin "P$10") (pinfunction "P$7_P$10") (pintype "bidirectional"))
      (node (ref "U21") (pin "P$11") (pinfunction "P$11_P$11") (pintype "bidirectional"))
      (node (ref "U21") (pin "P$12") (pinfunction "P$12_P$12") (pintype "bidirectional"))
      (node (ref "U21") (pin "P$13") (pinfunction "P$13_P$13") (pintype "bidirectional"))
      (node (ref "U21") (pin "P$14") (pinfunction "P$14_P$14") (pintype "bidirectional"))
      (node (ref "U21") (pin "P$15") (pinfunction "P$15_P$15") (pintype "bidirectional"))
      (node (ref "U21") (pin "P$16") (pinfunction "P$16_P$16") (pintype "bidirectional"))
      (node (ref "U21") (pin "P$17") (pinfunction "P$17_P$17") (pintype "bidirectional"))
      (node (ref "U21") (pin "P$18") (pinfunction "P$18_P$18") (pintype "bidirectional"))
      (node (ref "U21") (pin "P$7") (pinfunction "P$10_P$7") (pintype "bidirectional"))
      (node (ref "U21") (pin "P$8") (pinfunction "P$9_P$8") (pintype "bidirectional"))
      (node (ref "U21") (pin "P$9") (pinfunction "P$8_P$9") (pintype "bidirectional"))
      (node (ref "U22") (pin "P$1") (pinfunction "GND_P$1") (pintype "bidirectional"))
      (node (ref "U22") (pin "P$10") (pinfunction "P$7_P$10") (pintype "bidirectional"))
      (node (ref "U22") (pin "P$11") (pinfunction "P$11_P$11") (pintype "bidirectional"))
      (node (ref "U22") (pin "P$12") (pinfunction "P$12_P$12") (pintype "bidirectional"))
      (node (ref "U22") (pin "P$13") (pinfunction "P$13_P$13") (pintype "bidirectional"))
      (node (ref "U22") (pin "P$14") (pinfunction "P$14_P$14") (pintype "bidirectional"))
      (node (ref "U22") (pin "P$15") (pinfunction "P$15_P$15") (pintype "bidirectional"))
      (node (ref "U22") (pin "P$16") (pinfunction "P$16_P$16") (pintype "bidirectional"))
      (node (ref "U22") (pin "P$17") (pinfunction "P$17_P$17") (pintype "bidirectional"))
      (node (ref "U22") (pin "P$18") (pinfunction "P$18_P$18") (pintype "bidirectional"))
      (node (ref "U22") (pin "P$7") (pinfunction "P$10_P$7") (pintype "bidirectional"))
      (node (ref "U22") (pin "P$8") (pinfunction "P$9_P$8") (pintype "bidirectional"))
      (node (ref "U22") (pin "P$9") (pinfunction "P$8_P$9") (pintype "bidirectional"))
      (node (ref "U23") (pin "2") (pinfunction "GND_2") (pintype "bidirectional"))
      (node (ref "U23") (pin "3") (pinfunction "GND_3") (pintype "bidirectional"))
      (node (ref "U23") (pin "5") (pinfunction "GND_5") (pintype "bidirectional"))
      (node (ref "U23") (pin "GND") (pinfunction "GND_GND") (pintype "bidirectional"))
      (node (ref "U24") (pin "P$1") (pinfunction "+_P$1") (pintype "bidirectional"))
      (node (ref "U24") (pin "P$2") (pinfunction "GND_P$2") (pintype "bidirectional"))
      (node (ref "U25") (pin "P$11") (pinfunction "GND_P$11") (pintype "bidirectional"))
      (node (ref "U26") (pin "P$11") (pinfunction "GND_P$11") (pintype "bidirectional"))
      (node (ref "U27") (pin "P$11") (pinfunction "GND_P$11") (pintype "bidirectional"))
      (node (ref "U28") (pin "P$11") (pinfunction "GND_P$11") (pintype "bidirectional"))
      (node (ref "U29") (pin "GND") (pinfunction "GND_GND") (pintype "bidirectional"))
      (node (ref "U29") (pin "GND1") (pinfunction "GND1_GND1") (pintype "bidirectional"))
      (node (ref "U29") (pin "GND2") (pinfunction "GND2_GND2") (pintype "bidirectional"))
      (node (ref "U3") (pin "P$3") (pinfunction "GND_P$3") (pintype "bidirectional"))
      (node (ref "U30") (pin "P$11") (pinfunction "GND_P$11") (pintype "bidirectional"))
      (node (ref "U31") (pin "P$11") (pinfunction "GND_P$11") (pintype "bidirectional"))
      (node (ref "U32") (pin "P$11") (pinfunction "GND_P$11") (pintype "bidirectional"))
      (node (ref "U33") (pin "P$12") (pinfunction "GND_P$12") (pintype "bidirectional"))
      (node (ref "U33") (pin "P$2") (pinfunction "GND_P$2") (pintype "bidirectional"))
      (node (ref "U33") (pin "P$3") (pinfunction "GND_P$3") (pintype "bidirectional"))
      (node (ref "U33") (pin "P$4") (pinfunction "GND_P$4") (pintype "bidirectional"))
      (node (ref "U33") (pin "P$6") (pinfunction "GND_P$6") (pintype "bidirectional"))
      (node (ref "U34") (pin "GND") (pinfunction "GND_GND") (pintype "bidirectional"))
      (node (ref "U34") (pin "P$16") (pinfunction "ADDR_P$16") (pintype "bidirectional"))
      (node (ref "U34") (pin "P$6") (pinfunction "GND_P$6") (pintype "bidirectional"))
      (node (ref "U35") (pin "2") (pinfunction "GND_2") (pintype "bidirectional"))
      (node (ref "U35") (pin "3") (pinfunction "GND_3") (pintype "bidirectional"))
      (node (ref "U35") (pin "5") (pinfunction "GND_5") (pintype "bidirectional"))
      (node (ref "U35") (pin "GND") (pinfunction "GND_GND") (pintype "bidirectional"))
      (node (ref "U36") (pin "P$11") (pinfunction "GND_P$11") (pintype "bidirectional"))
      (node (ref "U36") (pin "P$12") (pinfunction "GND_P$12") (pintype "bidirectional"))
      (node (ref "U36") (pin "P$2") (pinfunction "GND_P$2") (pintype "bidirectional"))
      (node (ref "U36") (pin "P$3") (pinfunction "GND_P$3") (pintype "bidirectional"))
      (node (ref "U36") (pin "P$7") (pinfunction "GND_P$7") (pintype "bidirectional"))
      (node (ref "U36") (pin "P$9") (pinfunction "GND_P$9") (pintype "bidirectional"))
      (node (ref "U37") (pin "14") (pinfunction "GND_14") (pintype "bidirectional"))
      (node (ref "U37") (pin "15") (pinfunction "GND_15") (pintype "bidirectional"))
      (node (ref "U37") (pin "16") (pinfunction "GND_16") (pintype "bidirectional"))
      (node (ref "U37") (pin "17") (pinfunction "GND_17") (pintype "bidirectional"))
      (node (ref "U37") (pin "18") (pinfunction "GND_18") (pintype "bidirectional"))
      (node (ref "U37") (pin "2") (pinfunction "GND_2") (pintype "bidirectional"))
      (node (ref "U37") (pin "20") (pinfunction "GND_20") (pintype "bidirectional"))
      (node (ref "U37") (pin "3") (pinfunction "GND_3") (pintype "bidirectional"))
      (node (ref "U37") (pin "4") (pinfunction "GND_4") (pintype "bidirectional"))
      (node (ref "U37") (pin "5") (pinfunction "GND_5") (pintype "bidirectional"))
      (node (ref "U37") (pin "6") (pinfunction "GND_6") (pintype "bidirectional"))
      (node (ref "U37") (pin "PAD") (pinfunction "GND_PAD") (pintype "bidirectional"))
      (node (ref "U38") (pin "2") (pinfunction "GND_2") (pintype "bidirectional"))
      (node (ref "U38") (pin "3") (pinfunction "GND_3") (pintype "bidirectional"))
      (node (ref "U38") (pin "5") (pinfunction "GND_5") (pintype "bidirectional"))
      (node (ref "U38") (pin "GND") (pinfunction "GND_GND") (pintype "bidirectional"))
      (node (ref "U39") (pin "GND") (pinfunction "GND_GND") (pintype "bidirectional"))
      (node (ref "U39") (pin "P$16") (pinfunction "ADDR_P$16") (pintype "bidirectional"))
      (node (ref "U39") (pin "P$6") (pinfunction "GND_P$6") (pintype "bidirectional"))
      (node (ref "U4") (pin "P$3") (pinfunction "GND_P$3") (pintype "bidirectional"))
      (node (ref "U4") (pin "P$9") (pinfunction "GND_P$9") (pintype "bidirectional"))
      (node (ref "U40") (pin "2") (pinfunction "GND_2") (pintype "bidirectional"))
      (node (ref "U40") (pin "3") (pinfunction "GND_3") (pintype "bidirectional"))
      (node (ref "U40") (pin "5") (pinfunction "GND_5") (pintype "bidirectional"))
      (node (ref "U40") (pin "GND") (pinfunction "GND_GND") (pintype "bidirectional"))
      (node (ref "U5") (pin "P$3") (pinfunction "GND_P$3") (pintype "bidirectional"))
      (node (ref "U5") (pin "P$9") (pinfunction "GND_P$9") (pintype "bidirectional"))
      (node (ref "U6") (pin "P$3") (pinfunction "GND_P$3") (pintype "bidirectional"))
      (node (ref "U6") (pin "P$9") (pinfunction "GND_P$9") (pintype "bidirectional"))
      (node (ref "U7") (pin "P$1") (pinfunction "NC_P$1") (pintype "bidirectional"))
      (node (ref "U7") (pin "P$4") (pinfunction "GND_P$4") (pintype "bidirectional"))
      (node (ref "U8") (pin "P$1") (pinfunction "NC_P$1") (pintype "bidirectional"))
      (node (ref "U8") (pin "P$4") (pinfunction "GND_P$4") (pintype "bidirectional"))
      (node (ref "U9") (pin "P$11") (pinfunction "M3_P$11") (pintype "bidirectional"))
      (node (ref "U9") (pin "P$14") (pinfunction "PWMC_P$14") (pintype "bidirectional"))
      (node (ref "U9") (pin "P$16") (pinfunction "PWMD_P$16") (pintype "bidirectional"))
      (node (ref "U9") (pin "P$23") (pinfunction "GNDD_P$23") (pintype "bidirectional"))
      (node (ref "U9") (pin "P$24") (pinfunction "GNDC_P$24") (pintype "bidirectional"))
      (node (ref "U9") (pin "P$31") (pinfunction "GNDB_P$31") (pintype "bidirectional"))
      (node (ref "U9") (pin "P$32") (pinfunction "GNDA_P$32") (pintype "bidirectional"))
      (node (ref "U9") (pin "P$37") (pinfunction "GND_P$37") (pintype "bidirectional"))
      (node (ref "U9") (pin "P$8") (pinfunction "GND_P$8") (pintype "bidirectional"))
      (node (ref "U9") (pin "P$9") (pinfunction "GND_P$9") (pintype "bidirectional"))
    )
    (net (code "73") (name "I2C0") (class "Default")
      (node (ref "CON57") (pin "22") (pinfunction "22_22") (pintype "bidirectional"))
      (node (ref "U27") (pin "P$3") (pinfunction "A2_P$3") (pintype "bidirectional"))
    )
    (net (code "74") (name "I2C0°") (class "Default")
      (node (ref "CON49") (pin "3") (pinfunction "3_3") (pintype "bidirectional"))
      (node (ref "U27") (pin "P$18") (pinfunction "B2_P$18") (pintype "bidirectional"))
    )
    (net (code "75") (name "I2C1") (class "Default")
      (node (ref "CON58") (pin "24") (pinfunction "24_24") (pintype "bidirectional"))
      (node (ref "U30") (pin "P$8") (pinfunction "A7_P$8") (pintype "bidirectional"))
    )
    (net (code "76") (name "I2C1°") (class "Default")
      (node (ref "CON53") (pin "3") (pinfunction "3_3") (pintype "bidirectional"))
      (node (ref "U30") (pin "P$13") (pinfunction "B7_P$13") (pintype "bidirectional"))
    )
    (net (code "77") (name "IMU_DRDY") (class "Default")
      (node (ref "CON58") (pin "5") (pinfunction "5_5") (pintype "bidirectional"))
      (node (ref "U37") (pin "12") (pinfunction "INT_12") (pintype "bidirectional"))
    )
    (net (code "78") (name "IMU_FSYNC") (class "Default")
      (node (ref "J51") (pin "P$2") (pinfunction "2_P$2") (pintype "bidirectional"))
      (node (ref "U29") (pin "RESET") (pinfunction "/RESET_RESET") (pintype "bidirectional"))
    )
    (net (code "79") (name "IMU_SS") (class "Default")
      (node (ref "CON58") (pin "3") (pinfunction "3_3") (pintype "bidirectional"))
      (node (ref "U37") (pin "22") (pinfunction "~{CS}_22") (pintype "bidirectional"))
    )
    (net (code "80") (name "IO0") (class "Default")
      (node (ref "CON57") (pin "17") (pinfunction "17_17") (pintype "bidirectional"))
      (node (ref "U28") (pin "P$9") (pinfunction "A8_P$9") (pintype "bidirectional"))
    )
    (net (code "81") (name "IO0°") (class "Default")
      (node (ref "C102") (pin "2") (pinfunction "P$2_2") (pintype "bidirectional"))
      (node (ref "R42") (pin "2") (pinfunction "P$2_2") (pintype "bidirectional"))
      (node (ref "U28") (pin "P$12") (pinfunction "B8_P$12") (pintype "bidirectional"))
    )
    (net (code "82") (name "IO1") (class "Default")
      (node (ref "CON57") (pin "15") (pinfunction "15_15") (pintype "bidirectional"))
      (node (ref "U28") (pin "P$8") (pinfunction "A7_P$8") (pintype "bidirectional"))
    )
    (net (code "83") (name "IO1°") (class "Default")
      (node (ref "C108") (pin "2") (pinfunction "P$2_2") (pintype "bidirectional"))
      (node (ref "R47") (pin "2") (pinfunction "P$2_2") (pintype "bidirectional"))
      (node (ref "U28") (pin "P$13") (pinfunction "B7_P$13") (pintype "bidirectional"))
    )
    (net (code "84") (name "IO2") (class "Default")
      (node (ref "CON57") (pin "13") (pinfunction "13_13") (pintype "bidirectional"))
      (node (ref "U28") (pin "P$7") (pinfunction "A6_P$7") (pintype "bidirectional"))
    )
    (net (code "85") (name "IO2°") (class "Default")
      (node (ref "C114") (pin "2") (pinfunction "P$2_2") (pintype "bidirectional"))
      (node (ref "R54") (pin "2") (pinfunction "P$2_2") (pintype "bidirectional"))
      (node (ref "U28") (pin "P$14") (pinfunction "B6_P$14") (pintype "bidirectional"))
    )
    (net (code "86") (name "IO3") (class "Default")
      (node (ref "CON57") (pin "9") (pinfunction "9_9") (pintype "bidirectional"))
      (node (ref "U28") (pin "P$6") (pinfunction "A5_P$6") (pintype "bidirectional"))
    )
    (net (code "87") (name "IO3°") (class "Default")
      (node (ref "C117") (pin "2") (pinfunction "P$2_2") (pintype "bidirectional"))
      (node (ref "R60") (pin "2") (pinfunction "P$2_2") (pintype "bidirectional"))
      (node (ref "U28") (pin "P$15") (pinfunction "B5_P$15") (pintype "bidirectional"))
    )
    (net (code "88") (name "IO4") (class "Default")
      (node (ref "CON57") (pin "7") (pinfunction "7_7") (pintype "bidirectional"))
      (node (ref "U28") (pin "P$5") (pinfunction "A4_P$5") (pintype "bidirectional"))
    )
    (net (code "89") (name "IO4°") (class "Default")
      (node (ref "C124") (pin "2") (pinfunction "P$2_2") (pintype "bidirectional"))
      (node (ref "R67") (pin "2") (pinfunction "P$2_2") (pintype "bidirectional"))
      (node (ref "U28") (pin "P$16") (pinfunction "B4_P$16") (pintype "bidirectional"))
    )
    (net (code "90") (name "IO5") (class "Default")
      (node (ref "CON57") (pin "5") (pinfunction "5_5") (pintype "bidirectional"))
      (node (ref "U28") (pin "P$4") (pinfunction "A3_P$4") (pintype "bidirectional"))
    )
    (net (code "91") (name "IO5°") (class "Default")
      (node (ref "C131") (pin "2") (pinfunction "P$2_2") (pintype "bidirectional"))
      (node (ref "R75") (pin "2") (pinfunction "P$2_2") (pintype "bidirectional"))
      (node (ref "U28") (pin "P$17") (pinfunction "B3_P$17") (pintype "bidirectional"))
    )
    (net (code "92") (name "IO6") (class "Default")
      (node (ref "CON57") (pin "3") (pinfunction "3_3") (pintype "bidirectional"))
      (node (ref "U28") (pin "P$3") (pinfunction "A2_P$3") (pintype "bidirectional"))
    )
    (net (code "93") (name "IO6°") (class "Default")
      (node (ref "C134") (pin "2") (pinfunction "P$2_2") (pintype "bidirectional"))
      (node (ref "R80") (pin "2") (pinfunction "P$2_2") (pintype "bidirectional"))
      (node (ref "U28") (pin "P$18") (pinfunction "B2_P$18") (pintype "bidirectional"))
    )
    (net (code "94") (name "IO7") (class "Default")
      (node (ref "CON57") (pin "1") (pinfunction "1_1") (pintype "bidirectional"))
      (node (ref "U28") (pin "P$1") (pinfunction "A1_P$1") (pintype "bidirectional"))
    )
    (net (code "95") (name "IO7°") (class "Default")
      (node (ref "C137") (pin "2") (pinfunction "P$2_2") (pintype "bidirectional"))
      (node (ref "R85") (pin "2") (pinfunction "P$2_2") (pintype "bidirectional"))
      (node (ref "U28") (pin "P$20") (pinfunction "B1_P$20") (pintype "bidirectional"))
    )
    (net (code "96") (name "LAN_3V3") (class "Default")
      (node (ref "C143") (pin "2") (pinfunction "P$2_2") (pintype "bidirectional"))
      (node (ref "C144") (pin "2") (pinfunction "P$2_2") (pintype "bidirectional"))
      (node (ref "C145") (pin "2") (pinfunction "P$2_2") (pintype "bidirectional"))
      (node (ref "C146") (pin "2") (pinfunction "P$2_2") (pintype "bidirectional"))
      (node (ref "C147") (pin "2") (pinfunction "P$2_2") (pintype "bidirectional"))
      (node (ref "C148") (pin "P$2") (pinfunction "P$2_P$2") (pintype "bidirectional"))
      (node (ref "L9") (pin "2") (pinfunction "2_2") (pintype "bidirectional"))
      (node (ref "U20") (pin "10") (pinfunction "VDD33A_10") (pintype "bidirectional"))
      (node (ref "U20") (pin "49") (pinfunction "VDD33A_49") (pintype "bidirectional"))
      (node (ref "U20") (pin "5") (pinfunction "VDD33A_5") (pintype "bidirectional"))
      (node (ref "U20") (pin "51") (pinfunction "VDD33A_51") (pintype "bidirectional"))
      (node (ref "U20") (pin "54") (pinfunction "VDD33A_54") (pintype "bidirectional"))
      (node (ref "U20") (pin "57") (pinfunction "VDD33A_57") (pintype "bidirectional"))
      (node (ref "U20") (pin "64") (pinfunction "VDD33A_64") (pintype "bidirectional"))
    )
    (net (code "97") (name "LEDA") (class "Default")
      (node (ref "CON58") (pin "1") (pinfunction "1_1") (pintype "bidirectional"))
      (node (ref "R10") (pin "1") (pinfunction "P$1_1") (pintype "bidirectional"))
    )
    (net (code "98") (name "LEDB") (class "Default")
      (node (ref "CON58") (pin "2") (pinfunction "2_2") (pintype "bidirectional"))
      (node (ref "R11") (pin "1") (pinfunction "P$1_1") (pintype "bidirectional"))
    )
    (net (code "99") (name "LOW_VOLTAGE") (class "Default")
      (node (ref "C4") (pin "1") (pinfunction "P$1_1") (pintype "bidirectional"))
      (node (ref "IC2") (pin "3") (pinfunction "AINP1_3") (pintype "passive"))
      (node (ref "U1") (pin "13") (pinfunction "X_13") (pintype "bidirectional"))
    )
    (net (code "100") (name "LV_MUXA") (class "Default")
      (node (ref "CON58") (pin "40") (pinfunction "40_40") (pintype "bidirectional"))
      (node (ref "U1") (pin "10") (pinfunction "A_10") (pintype "bidirectional"))
    )
    (net (code "101") (name "LV_MUXB") (class "Default")
      (node (ref "CON58") (pin "39") (pinfunction "39_39") (pintype "bidirectional"))
      (node (ref "U1") (pin "9") (pinfunction "B_9") (pintype "bidirectional"))
    )
    (net (code "102") (name "M0_CS") (class "Default")
      (node (ref "C71") (pin "2") (pinfunction "P$2_2") (pintype "bidirectional"))
      (node (ref "IC2") (pin "45") (pinfunction "AINP8_45") (pintype "passive"))
      (node (ref "R27") (pin "2") (pinfunction "P$2_2") (pintype "bidirectional"))
    )
    (net (code "103") (name "M0_FAULT") (class "Default")
      (node (ref "CON57") (pin "27") (pinfunction "27_27") (pintype "bidirectional"))
      (node (ref "U9") (pin "P$2") (pinfunction "OT_P$2") (pintype "bidirectional"))
      (node (ref "U9") (pin "P$3") (pinfunction "FAULT_P$3") (pintype "bidirectional"))
    )
    (net (code "104") (name "M0_PWMA") (class "Default")
      (node (ref "CON57") (pin "28") (pinfunction "28_28") (pintype "bidirectional"))
      (node (ref "U9") (pin "P$4") (pinfunction "PWMA_P$4") (pintype "bidirectional"))
    )
    (net (code "105") (name "M0_PWMB") (class "Default")
      (node (ref "CON57") (pin "32") (pinfunction "32_32") (pintype "bidirectional"))
      (node (ref "U9") (pin "P$6") (pinfunction "PWMB_P$6") (pintype "bidirectional"))
    )
    (net (code "106") (name "M1_CS") (class "Default")
      (node (ref "C90") (pin "2") (pinfunction "P$2_2") (pintype "bidirectional"))
      (node (ref "IC2") (pin "47") (pinfunction "AINP7_47") (pintype "passive"))
      (node (ref "R34") (pin "2") (pinfunction "P$2_2") (pintype "bidirectional"))
    )
    (net (code "107") (name "M1_FAULT") (class "Default")
      (node (ref "CON57") (pin "24") (pinfunction "24_24") (pintype "bidirectional"))
      (node (ref "U14") (pin "P$2") (pinfunction "OT_P$2") (pintype "bidirectional"))
      (node (ref "U14") (pin "P$3") (pinfunction "FAULT_P$3") (pintype "bidirectional"))
    )
    (net (code "108") (name "M1_PWMA") (class "Default")
      (node (ref "CON57") (pin "25") (pinfunction "25_25") (pintype "bidirectional"))
      (node (ref "U14") (pin "P$4") (pinfunction "PWMA_P$4") (pintype "bidirectional"))
    )
    (net (code "109") (name "M1_PWMB") (class "Default")
      (node (ref "CON57") (pin "26") (pinfunction "26_26") (pintype "bidirectional"))
      (node (ref "U14") (pin "P$6") (pinfunction "PWMB_P$6") (pintype "bidirectional"))
    )
    (net (code "110") (name "M2_CS") (class "Default")
      (node (ref "C76") (pin "2") (pinfunction "P$2_2") (pintype "bidirectional"))
      (node (ref "IC2") (pin "49") (pinfunction "AINP6_49") (pintype "passive"))
      (node (ref "R31") (pin "2") (pinfunction "P$2_2") (pintype "bidirectional"))
    )
    (net (code "111") (name "M2_PWMA") (class "Default")
      (node (ref "CON58") (pin "19") (pinfunction "19_19") (pintype "bidirectional"))
      (node (ref "U10") (pin "P$14") (pinfunction "PWMC_P$14") (pintype "bidirectional"))
    )
    (net (code "112") (name "M2_PWMB") (class "Default")
      (node (ref "CON58") (pin "17") (pinfunction "17_17") (pintype "bidirectional"))
      (node (ref "U10") (pin "P$16") (pinfunction "PWMD_P$16") (pintype "bidirectional"))
    )
    (net (code "113") (name "M3_CS") (class "Default")
      (node (ref "C56") (pin "2") (pinfunction "P$2_2") (pintype "bidirectional"))
      (node (ref "IC2") (pin "51") (pinfunction "AINP5_51") (pintype "passive"))
      (node (ref "R21") (pin "2") (pinfunction "P$2_2") (pintype "bidirectional"))
    )
    (net (code "114") (name "M3_PWMA") (class "Default")
      (node (ref "CON58") (pin "23") (pinfunction "23_23") (pintype "bidirectional"))
      (node (ref "U10") (pin "P$4") (pinfunction "PWMA_P$4") (pintype "bidirectional"))
    )
    (net (code "115") (name "M3_PWMB") (class "Default")
      (node (ref "CON58") (pin "21") (pinfunction "21_21") (pintype "bidirectional"))
      (node (ref "U10") (pin "P$6") (pinfunction "PWMB_P$6") (pintype "bidirectional"))
    )
    (net (code "116") (name "M4_PWMA") (class "Default")
      (node (ref "CON58") (pin "31") (pinfunction "31_31") (pintype "bidirectional"))
      (node (ref "U11") (pin "P$14") (pinfunction "PWMC_P$14") (pintype "bidirectional"))
    )
    (net (code "117") (name "M4_PWMB") (class "Default")
      (node (ref "CON58") (pin "27") (pinfunction "27_27") (pintype "bidirectional"))
      (node (ref "U11") (pin "P$16") (pinfunction "PWMD_P$16") (pintype "bidirectional"))
    )
    (net (code "118") (name "M5_CS") (class "Default")
      (node (ref "C58") (pin "2") (pinfunction "P$2_2") (pintype "bidirectional"))
      (node (ref "IC2") (pin "61") (pinfunction "AINP4_61") (pintype "passive"))
      (node (ref "R22") (pin "2") (pinfunction "P$2_2") (pintype "bidirectional"))
    )
    (net (code "119") (name "M5_PWMA") (class "Default")
      (node (ref "CON58") (pin "35") (pinfunction "35_35") (pintype "bidirectional"))
      (node (ref "U11") (pin "P$4") (pinfunction "PWMA_P$4") (pintype "bidirectional"))
    )
    (net (code "120") (name "M5_PWMB") (class "Default")
      (node (ref "CON58") (pin "33") (pinfunction "33_33") (pintype "bidirectional"))
      (node (ref "U11") (pin "P$6") (pinfunction "PWMB_P$6") (pintype "bidirectional"))
    )
    (net (code "121") (name "M23_FAULT") (class "Default")
      (node (ref "CON58") (pin "25") (pinfunction "25_25") (pintype "bidirectional"))
      (node (ref "U10") (pin "P$2") (pinfunction "OT_P$2") (pintype "bidirectional"))
      (node (ref "U10") (pin "P$3") (pinfunction "FAULT_P$3") (pintype "bidirectional"))
    )
    (net (code "122") (name "M45_FAULT") (class "Default")
      (node (ref "CON58") (pin "37") (pinfunction "37_37") (pintype "bidirectional"))
      (node (ref "U11") (pin "P$2") (pinfunction "OT_P$2") (pintype "bidirectional"))
      (node (ref "U11") (pin "P$3") (pinfunction "FAULT_P$3") (pintype "bidirectional"))
    )
    (net (code "123") (name "MISO0") (class "Default")
      (node (ref "CON57") (pin "36") (pinfunction "36_36") (pintype "bidirectional"))
      (node (ref "U25") (pin "P$6") (pinfunction "A5_P$6") (pintype "bidirectional"))
    )
    (net (code "124") (name "MISO0°") (class "Default")
      (node (ref "CON40") (pin "5") (pinfunction "5_5") (pintype "bidirectional"))
      (node (ref "U25") (pin "P$15") (pinfunction "B5_P$15") (pintype "bidirectional"))
    )
    (net (code "125") (name "MISO1") (class "Default")
      (node (ref "CON58") (pin "20") (pinfunction "20_20") (pintype "bidirectional"))
      (node (ref "U32") (pin "P$1") (pinfunction "A1_P$1") (pintype "bidirectional"))
      (node (ref "U37") (pin "9") (pinfunction "AD0/SDO_9") (pintype "bidirectional"))
    )
    (net (code "126") (name "MISO1°") (class "Default")
      (node (ref "CON45") (pin "5") (pinfunction "5_5") (pintype "bidirectional"))
      (node (ref "U32") (pin "P$20") (pinfunction "B1_P$20") (pintype "bidirectional"))
    )
    (net (code "127") (name "MOSI0") (class "Default")
      (node (ref "CON57") (pin "35") (pinfunction "35_35") (pintype "bidirectional"))
      (node (ref "U25") (pin "P$7") (pinfunction "A6_P$7") (pintype "bidirectional"))
    )
    (net (code "128") (name "MOSI0°") (class "Default")
      (node (ref "CON40") (pin "4") (pinfunction "4_4") (pintype "bidirectional"))
      (node (ref "U25") (pin "P$14") (pinfunction "B6_P$14") (pintype "bidirectional"))
    )
    (net (code "129") (name "MOSI1") (class "Default")
      (node (ref "CON58") (pin "18") (pinfunction "18_18") (pintype "bidirectional"))
      (node (ref "U32") (pin "P$3") (pinfunction "A2_P$3") (pintype "bidirectional"))
      (node (ref "U37") (pin "24") (pinfunction "SDA/SDI_24") (pintype "bidirectional"))
    )
    (net (code "130") (name "MOSI1°") (class "Default")
      (node (ref "CON45") (pin "4") (pinfunction "4_4") (pintype "bidirectional"))
      (node (ref "U32") (pin "P$18") (pinfunction "B2_P$18") (pintype "bidirectional"))
    )
    (net (code "131") (name "Net-(C7-P$1)") (class "Default")
      (node (ref "C7") (pin "1") (pinfunction "P$1_1") (pintype "bidirectional"))
      (node (ref "R1") (pin "2") (pinfunction "P$2_2") (pintype "bidirectional"))
      (node (ref "R5") (pin "1") (pinfunction "P$1_1") (pintype "bidirectional"))
      (node (ref "U1") (pin "11") (pinfunction "X3_11") (pintype "bidirectional"))
    )
    (net (code "132") (name "Net-(C8-P$1)") (class "Default")
      (node (ref "C8") (pin "1") (pinfunction "P$1_1") (pintype "bidirectional"))
      (node (ref "R2") (pin "2") (pinfunction "P$2_2") (pintype "bidirectional"))
      (node (ref "R6") (pin "1") (pinfunction "P$1_1") (pintype "bidirectional"))
      (node (ref "U1") (pin "15") (pinfunction "X2_15") (pintype "bidirectional"))
    )
    (net (code "133") (name "Net-(C9-P$1)") (class "Default")
      (node (ref "C9") (pin "1") (pinfunction "P$1_1") (pintype "bidirectional"))
      (node (ref "R3") (pin "2") (pinfunction "P$2_2") (pintype "bidirectional"))
      (node (ref "R7") (pin "1") (pinfunction "P$1_1") (pintype "bidirectional"))
      (node (ref "U1") (pin "14") (pinfunction "X1_14") (pintype "bidirectional"))
    )
    (net (code "134") (name "Net-(C10-P$1)") (class "Default")
      (node (ref "C10") (pin "1") (pinfunction "P$1_1") (pintype "bidirectional"))
      (node (ref "R4") (pin "2") (pinfunction "P$2_2") (pintype "bidirectional"))
      (node (ref "R8") (pin "1") (pinfunction "P$1_1") (pintype "bidirectional"))
      (node (ref "U1") (pin "12") (pinfunction "X0_12") (pintype "bidirectional"))
    )
    (net (code "135") (name "Net-(C19-P$1)") (class "Default")
      (node (ref "C19") (pin "1") (pinfunction "P$1_1") (pintype "bidirectional"))
      (node (ref "U4") (pin "P$8") (pinfunction "SS_P$8") (pintype "bidirectional"))
    )
    (net (code "136") (name "Net-(C23-P$1)") (class "Default")
      (node (ref "C23") (pin "1") (pinfunction "P$1_1") (pintype "bidirectional"))
      (node (ref "U5") (pin "P$8") (pinfunction "SS_P$8") (pintype "bidirectional"))
    )
    (net (code "137") (name "Net-(C27-P$1)") (class "Default")
      (node (ref "C27") (pin "1") (pinfunction "P$1_1") (pintype "bidirectional"))
      (node (ref "U6") (pin "P$8") (pinfunction "SS_P$8") (pintype "bidirectional"))
    )
    (net (code "138") (name "Net-(C67-P$2)") (class "Default")
      (node (ref "C67") (pin "2") (pinfunction "P$2_2") (pintype "bidirectional"))
      (node (ref "J11") (pin "P$1") (pinfunction "1_P$1") (pintype "bidirectional"))
      (node (ref "J8") (pin "P$1") (pinfunction "1_P$1") (pintype "bidirectional"))
      (node (ref "J9") (pin "P$1") (pinfunction "1_P$1") (pintype "bidirectional"))
      (node (ref "U9") (pin "P$10") (pinfunction "VCAP_P$10") (pintype "bidirectional"))
    )
    (net (code "139") (name "Net-(C73-P$2)") (class "Default")
      (node (ref "C73") (pin "2") (pinfunction "P$2_2") (pintype "bidirectional"))
      (node (ref "J12") (pin "P$1") (pinfunction "1_P$1") (pintype "bidirectional"))
      (node (ref "J13") (pin "P$1") (pinfunction "1_P$1") (pintype "bidirectional"))
      (node (ref "U10") (pin "P$10") (pinfunction "VCAP_P$10") (pintype "bidirectional"))
    )
    (net (code "140") (name "Net-(C75-P$2)") (class "Default")
      (node (ref "C75") (pin "2") (pinfunction "P$2_2") (pintype "bidirectional"))
      (node (ref "J14") (pin "P$1") (pinfunction "1_P$1") (pintype "bidirectional"))
      (node (ref "J15") (pin "P$1") (pinfunction "1_P$1") (pintype "bidirectional"))
      (node (ref "U11") (pin "P$10") (pinfunction "VCAP_P$10") (pintype "bidirectional"))
    )
    (net (code "141") (name "Net-(C89-P$2)") (class "Default")
      (node (ref "C89") (pin "2") (pinfunction "P$2_2") (pintype "bidirectional"))
      (node (ref "J20") (pin "P$1") (pinfunction "1_P$1") (pintype "bidirectional"))
      (node (ref "J21") (pin "P$1") (pinfunction "1_P$1") (pintype "bidirectional"))
      (node (ref "J23") (pin "P$1") (pinfunction "1_P$1") (pintype "bidirectional"))
      (node (ref "U14") (pin "P$10") (pinfunction "VCAP_P$10") (pintype "bidirectional"))
    )
    (net (code "142") (name "Net-(C150-P$2)") (class "Default")
      (node (ref "C150") (pin "2") (pinfunction "P$2_2") (pintype "bidirectional"))
      (node (ref "Q1") (pin "1") (pinfunction "1_1") (pintype "bidirectional"))
      (node (ref "R90") (pin "2") (pinfunction "P$2_2") (pintype "bidirectional"))
      (node (ref "U20") (pin "61") (pinfunction "XI_61") (pintype "bidirectional"))
    )
    (net (code "143") (name "Net-(C151-P$2)") (class "Default")
      (node (ref "C151") (pin "2") (pinfunction "P$2_2") (pintype "bidirectional"))
      (node (ref "Q1") (pin "2") (pinfunction "2_2") (pintype "bidirectional"))
      (node (ref "R90") (pin "1") (pinfunction "P$1_1") (pintype "bidirectional"))
      (node (ref "U20") (pin "60") (pinfunction "XO_60") (pintype "bidirectional"))
    )
    (net (code "144") (name "Net-(C154-P$2)") (class "Default")
      (node (ref "C153") (pin "P$2") (pinfunction "P$2_P$2") (pintype "bidirectional"))
      (node (ref "C154") (pin "2") (pinfunction "P$2_2") (pintype "bidirectional"))
      (node (ref "C155") (pin "2") (pinfunction "P$2_2") (pintype "bidirectional"))
      (node (ref "U20") (pin "15") (pinfunction "VDD18CORE_15") (pintype "bidirectional"))
      (node (ref "U20") (pin "38") (pinfunction "VDD18CORE_38") (pintype "bidirectional"))
    )
    (net (code "145") (name "Net-(C156-P$2)") (class "Default")
      (node (ref "C156") (pin "2") (pinfunction "P$2_2") (pintype "bidirectional"))
      (node (ref "L10") (pin "1") (pinfunction "1_1") (pintype "bidirectional"))
      (node (ref "U20") (pin "48") (pinfunction "VDD18ETHPLL_48") (pintype "bidirectional"))
    )
    (net (code "146") (name "Net-(C157-P$2)") (class "Default")
      (node (ref "C157") (pin "2") (pinfunction "P$2_2") (pintype "bidirectional"))
      (node (ref "C158") (pin "P$2") (pinfunction "P$2_P$2") (pintype "bidirectional"))
      (node (ref "L10") (pin "2") (pinfunction "2_2") (pintype "bidirectional"))
      (node (ref "U20") (pin "62") (pinfunction "VDD18USBPLL_62") (pintype "bidirectional"))
    )
    (net (code "147") (name "Net-(C168-P$2)") (class "Default")
      (node (ref "C168") (pin "2") (pinfunction "P$2_2") (pintype "bidirectional"))
      (node (ref "IC1") (pin "8") (pinfunction "XTAL1_8") (pintype "passive"))
      (node (ref "Q2") (pin "P$1") (pinfunction "P1_P$1") (pintype "bidirectional"))
    )
    (net (code "148") (name "Net-(C169-P$2)") (class "Default")
      (node (ref "C169") (pin "2") (pinfunction "P$2_2") (pintype "bidirectional"))
      (node (ref "IC1") (pin "9") (pinfunction "XTAL2_9") (pintype "passive"))
      (node (ref "Q2") (pin "P$2") (pinfunction "P2_P$2") (pintype "bidirectional"))
    )
    (net (code "149") (name "Net-(C170-P$2)") (class "Default")
      (node (ref "C170") (pin "2") (pinfunction "P$2_2") (pintype "bidirectional"))
      (node (ref "IC1") (pin "7") (pinfunction "PLLCAP_7") (pintype "passive"))
    )
    (net (code "150") (name "Net-(C182-P$2)") (class "Default")
      (node (ref "C182") (pin "2") (pinfunction "P$2_2") (pintype "bidirectional"))
      (node (ref "J33") (pin "P$1") (pinfunction "1_P$1") (pintype "bidirectional"))
      (node (ref "J34") (pin "P$1") (pinfunction "1_P$1") (pintype "bidirectional"))
      (node (ref "U25") (pin "P$19") (pinfunction "VB_P$19") (pintype "bidirectional"))
    )
    (net (code "151") (name "Net-(C184-P$2)") (class "Default")
      (node (ref "C184") (pin "2") (pinfunction "P$2_2") (pintype "bidirectional"))
      (node (ref "J35") (pin "P$1") (pinfunction "1_P$1") (pintype "bidirectional"))
      (node (ref "J36") (pin "P$1") (pinfunction "1_P$1") (pintype "bidirectional"))
      (node (ref "U26") (pin "P$19") (pinfunction "VB_P$19") (pintype "bidirectional"))
    )
    (net (code "152") (name "Net-(C186-P$2)") (class "Default")
      (node (ref "C186") (pin "2") (pinfunction "P$2_2") (pintype "bidirectional"))
      (node (ref "J37") (pin "P$1") (pinfunction "1_P$1") (pintype "bidirectional"))
      (node (ref "J38") (pin "P$1") (pinfunction "1_P$1") (pintype "bidirectional"))
      (node (ref "U27") (pin "P$19") (pinfunction "VB_P$19") (pintype "bidirectional"))
    )
    (net (code "153") (name "Net-(C188-P$2)") (class "Default")
      (node (ref "C188") (pin "2") (pinfunction "P$2_2") (pintype "bidirectional"))
      (node (ref "J39") (pin "P$1") (pinfunction "1_P$1") (pintype "bidirectional"))
      (node (ref "J40") (pin "P$1") (pinfunction "1_P$1") (pintype "bidirectional"))
      (node (ref "U28") (pin "P$19") (pinfunction "VB_P$19") (pintype "bidirectional"))
    )
    (net (code "154") (name "Net-(C190-P$2)") (class "Default")
      (node (ref "C190") (pin "2") (pinfunction "P$2_2") (pintype "bidirectional"))
      (node (ref "J41") (pin "P$1") (pinfunction "1_P$1") (pintype "bidirectional"))
      (node (ref "J42") (pin "P$1") (pinfunction "1_P$1") (pintype "bidirectional"))
      (node (ref "U30") (pin "P$19") (pinfunction "VB_P$19") (pintype "bidirectional"))
    )
    (net (code "155") (name "Net-(C192-P$2)") (class "Default")
      (node (ref "C192") (pin "2") (pinfunction "P$2_2") (pintype "bidirectional"))
      (node (ref "J43") (pin "P$1") (pinfunction "1_P$1") (pintype "bidirectional"))
      (node (ref "J44") (pin "P$1") (pinfunction "1_P$1") (pintype "bidirectional"))
      (node (ref "U31") (pin "P$19") (pinfunction "VB_P$19") (pintype "bidirectional"))
    )
    (net (code "156") (name "Net-(C194-P$2)") (class "Default")
      (node (ref "C194") (pin "2") (pinfunction "P$2_2") (pintype "bidirectional"))
      (node (ref "J45") (pin "P$1") (pinfunction "1_P$1") (pintype "bidirectional"))
      (node (ref "J46") (pin "P$1") (pinfunction "1_P$1") (pintype "bidirectional"))
      (node (ref "U32") (pin "P$19") (pinfunction "VB_P$19") (pintype "bidirectional"))
    )
    (net (code "157") (name "Net-(C216-P$2)") (class "Default")
      (node (ref "C216") (pin "2") (pinfunction "P$2_2") (pintype "bidirectional"))
      (node (ref "C220") (pin "P$2") (pinfunction "P$2_P$2") (pintype "bidirectional"))
      (node (ref "U37") (pin "1") (pinfunction "VDDIO_1") (pintype "bidirectional"))
      (node (ref "U37") (pin "13") (pinfunction "VDD_13") (pintype "bidirectional"))
      (node (ref "U37") (pin "8") (pinfunction "VDDIO_8") (pintype "bidirectional"))
      (node (ref "U38") (pin "1") (pinfunction "VO_1") (pintype "bidirectional"))
    )
    (net (code "158") (name "Net-(C217-P$2)") (class "Default")
      (node (ref "C217") (pin "2") (pinfunction "P$2_2") (pintype "bidirectional"))
      (node (ref "U37") (pin "10") (pinfunction "REGOUT_10") (pintype "bidirectional"))
    )
    (net (code "159") (name "Net-(CON3-1)") (class "Default")
      (node (ref "CON3") (pin "P$1") (pinfunction "1_P$1") (pintype "bidirectional"))
      (node (ref "CON4") (pin "P$2") (pinfunction "2_P$2") (pintype "bidirectional"))
    )
    (net (code "160") (name "Net-(CON4-1)") (class "Default")
      (node (ref "CON4") (pin "P$1") (pinfunction "1_P$1") (pintype "bidirectional"))
      (node (ref "CON5") (pin "P$2") (pinfunction "2_P$2") (pintype "bidirectional"))
    )
    (net (code "161") (name "Net-(CON5-1)") (class "Default")
      (node (ref "CON5") (pin "P$1") (pinfunction "1_P$1") (pintype "bidirectional"))
      (node (ref "CON6") (pin "P$2") (pinfunction "2_P$2") (pintype "bidirectional"))
    )
    (net (code "162") (name "Net-(CON7-2)") (class "Default")
      (node (ref "C25") (pin "P$1") (pinfunction "P$1_P$1") (pintype "bidirectional"))
      (node (ref "C26") (pin "+") (pinfunction "+_+") (pintype "bidirectional"))
      (node (ref "CON7") (pin "P$2") (pinfunction "2_P$2") (pintype "bidirectional"))
      (node (ref "R19") (pin "1") (pinfunction "P$1_1") (pintype "bidirectional"))
      (node (ref "U6") (pin "P$4") (pinfunction "VO_P$4") (pintype "bidirectional"))
      (node (ref "U6") (pin "P$5") (pinfunction "VO_P$5") (pintype "bidirectional"))
    )
    (net (code "163") (name "Net-(CON8-1)") (class "Default")
      (node (ref "CON8") (pin "P$1") (pinfunction "1_P$1") (pintype "bidirectional"))
      (node (ref "L1") (pin "P$1") (pinfunction "1_P$1") (pintype "bidirectional"))
      (node (ref "L2") (pin "P$1") (pinfunction "1_P$1") (pintype "bidirectional"))
    )
    (net (code "164") (name "Net-(CON8-2)") (class "Default")
      (node (ref "CON8") (pin "P$2") (pinfunction "2_P$2") (pintype "bidirectional"))
      (node (ref "R24") (pin "P$2") (pinfunction "P$2_P$2") (pintype "bidirectional"))
      (node (ref "U12") (pin "P$2") (pinfunction "IN+_P$2") (pintype "bidirectional"))
    )
    (net (code "165") (name "Net-(CON9-1)") (class "Default")
      (node (ref "CON9") (pin "P$1") (pinfunction "1_P$1") (pintype "bidirectional"))
      (node (ref "R23") (pin "P$2") (pinfunction "P$2_P$2") (pintype "bidirectional"))
      (node (ref "U7") (pin "P$3") (pinfunction "IN-_P$3") (pintype "bidirectional"))
    )
    (net (code "166") (name "Net-(CON9-2)") (class "Default")
      (node (ref "C64") (pin "P$2") (pinfunction "P$2_P$2") (pintype "bidirectional"))
      (node (ref "CON9") (pin "P$2") (pinfunction "2_P$2") (pintype "bidirectional"))
      (node (ref "U10") (pin "P$30") (pinfunction "OUTB_P$30") (pintype "bidirectional"))
    )
    (net (code "167") (name "Net-(CON10-1)") (class "Default")
      (node (ref "CON10") (pin "P$1") (pinfunction "1_P$1") (pintype "bidirectional"))
      (node (ref "R25") (pin "P$2") (pinfunction "P$2_P$2") (pintype "bidirectional"))
      (node (ref "U8") (pin "P$3") (pinfunction "IN-_P$3") (pintype "bidirectional"))
    )
    (net (code "168") (name "Net-(CON10-2)") (class "Default")
      (node (ref "C66") (pin "P$2") (pinfunction "P$2_P$2") (pintype "bidirectional"))
      (node (ref "CON10") (pin "P$2") (pinfunction "2_P$2") (pintype "bidirectional"))
      (node (ref "U11") (pin "P$30") (pinfunction "OUTB_P$30") (pintype "bidirectional"))
    )
    (net (code "169") (name "Net-(CON11-1)") (class "Default")
      (node (ref "C68") (pin "P$2") (pinfunction "P$2_P$2") (pintype "bidirectional"))
      (node (ref "CON11") (pin "P$1") (pinfunction "1_P$1") (pintype "bidirectional"))
      (node (ref "U10") (pin "P$25") (pinfunction "OUTC_P$25") (pintype "bidirectional"))
    )
    (net (code "170") (name "Net-(CON11-2)") (class "Default")
      (node (ref "CON11") (pin "P$2") (pinfunction "2_P$2") (pintype "bidirectional"))
      (node (ref "R29") (pin "P$2") (pinfunction "P$2_P$2") (pintype "bidirectional"))
      (node (ref "U13") (pin "P$2") (pinfunction "IN+_P$2") (pintype "bidirectional"))
    )
    (net (code "171") (name "Net-(CON12-1)") (class "Default")
      (node (ref "C69") (pin "P$2") (pinfunction "P$2_P$2") (pintype "bidirectional"))
      (node (ref "CON12") (pin "P$1") (pinfunction "1_P$1") (pintype "bidirectional"))
      (node (ref "U11") (pin "P$25") (pinfunction "OUTC_P$25") (pintype "bidirectional"))
    )
    (net (code "172") (name "Net-(CON12-2)") (class "Default")
      (node (ref "C74") (pin "P$2") (pinfunction "P$2_P$2") (pintype "bidirectional"))
      (node (ref "CON12") (pin "P$2") (pinfunction "2_P$2") (pintype "bidirectional"))
      (node (ref "U11") (pin "P$22") (pinfunction "OUTD_P$22") (pintype "bidirectional"))
    )
    (net (code "173") (name "Net-(CON13-1)") (class "Default")
      (node (ref "CON13") (pin "P$1") (pinfunction "1_P$1") (pintype "bidirectional"))
      (node (ref "L5") (pin "P$1") (pinfunction "1_P$1") (pintype "bidirectional"))
      (node (ref "L6") (pin "P$1") (pinfunction "1_P$1") (pintype "bidirectional"))
    )
    (net (code "174") (name "Net-(CON13-2)") (class "Default")
      (node (ref "CON13") (pin "P$2") (pinfunction "2_P$2") (pintype "bidirectional"))
      (node (ref "R32") (pin "P$2") (pinfunction "P$2_P$2") (pintype "bidirectional"))
      (node (ref "U15") (pin "P$3") (pinfunction "IN-_P$3") (pintype "bidirectional"))
    )
    (net (code "175") (name "Net-(CON14-1)") (class "Default")
      (node (ref "CON14") (pin "P$1") (pinfunction "1_P$1") (pintype "bidirectional"))
      (node (ref "U17") (pin "V") (pinfunction "V_V") (pintype "bidirectional"))
    )
    (net (code "176") (name "Net-(CON14-2)") (class "Default")
      (node (ref "CON14") (pin "P$2") (pinfunction "2_P$2") (pintype "bidirectional"))
      (node (ref "K1") (pin "1") (pinfunction "NF_1") (pintype "bidirectional"))
      (node (ref "K2") (pin "12") (pinfunction "NO_12") (pintype "bidirectional"))
    )
    (net (code "177") (name "Net-(CON14-3)") (class "Default")
      (node (ref "CON14") (pin "P$3") (pinfunction "3_P$3") (pintype "bidirectional"))
      (node (ref "K1") (pin "12") (pinfunction "NO_12") (pintype "bidirectional"))
      (node (ref "K2") (pin "1") (pinfunction "NF_1") (pintype "bidirectional"))
    )
    (net (code "178") (name "Net-(CON17-1)") (class "Default")
      (node (ref "CON17") (pin "P$1") (pinfunction "1_P$1") (pintype "bidirectional"))
      (node (ref "U19") (pin "V") (pinfunction "V_V") (pintype "bidirectional"))
    )
    (net (code "179") (name "Net-(CON17-2)") (class "Default")
      (node (ref "CON17") (pin "P$2") (pinfunction "2_P$2") (pintype "bidirectional"))
      (node (ref "K3") (pin "1") (pinfunction "NF_1") (pintype "bidirectional"))
      (node (ref "K4") (pin "12") (pinfunction "NO_12") (pintype "bidirectional"))
    )
    (net (code "180") (name "Net-(CON17-3)") (class "Default")
      (node (ref "CON17") (pin "P$3") (pinfunction "3_P$3") (pintype "bidirectional"))
      (node (ref "K3") (pin "12") (pinfunction "NO_12") (pintype "bidirectional"))
      (node (ref "K4") (pin "1") (pinfunction "NF_1") (pintype "bidirectional"))
    )
    (net (code "181") (name "Net-(CON60-D+)") (class "Default")
      (node (ref "CON60") (pin "3") (pinfunction "D+_3") (pintype "bidirectional"))
      (node (ref "J49") (pin "P$1") (pinfunction "1_P$1") (pintype "bidirectional"))
    )
    (net (code "182") (name "Net-(CON60-D-)") (class "Default")
      (node (ref "CON60") (pin "2") (pinfunction "D-_2") (pintype "bidirectional"))
      (node (ref "J48") (pin "P$1") (pinfunction "1_P$1") (pintype "bidirectional"))
    )
    (net (code "183") (name "Net-(IC2-DVDD)") (class "Default")
      (node (ref "C166") (pin "P$2") (pinfunction "P$2_P$2") (pintype "bidirectional"))
      (node (ref "IC2") (pin "26") (pinfunction "DVDD_26") (pintype "passive"))
      (node (ref "U23") (pin "1") (pinfunction "VO_1") (pintype "bidirectional"))
    )
    (net (code "184") (name "Net-(IC2-MODE0)") (class "Default")
      (node (ref "IC2") (pin "34") (pinfunction "MODE0_34") (pintype "passive"))
      (node (ref "J28") (pin "P$1") (pinfunction "1_P$1") (pintype "bidirectional"))
      (node (ref "J29") (pin "P$2") (pinfunction "2_P$2") (pintype "bidirectional"))
    )
    (net (code "185") (name "Net-(IC2-VCOM)") (class "Default")
      (node (ref "IC2") (pin "55") (pinfunction "VCOM_55") (pintype "passive"))
      (node (ref "J30") (pin "P$2") (pinfunction "2_P$2") (pintype "bidirectional"))
    )
    (net (code "186") (name "Net-(IC3-TRIM)") (class "Default")
      (node (ref "C175") (pin "P$1") (pinfunction "P$1_P$1") (pintype "bidirectional"))
      (node (ref "IC3") (pin "5") (pinfunction "TRIM_5") (pintype "passive"))
    )
    (net (code "187") (name "Net-(IC3-VOUT)") (class "Default")
      (node (ref "IC3") (pin "6") (pinfunction "VOUT_6") (pintype "passive"))
      (node (ref "J31") (pin "P$1") (pinfunction "1_P$1") (pintype "bidirectional"))
    )
    (net (code "188") (name "Net-(IC4-TRIM)") (class "Default")
      (node (ref "C179") (pin "P$1") (pinfunction "P$1_P$1") (pintype "bidirectional"))
      (node (ref "IC4") (pin "5") (pinfunction "TRIM_5") (pintype "passive"))
    )
    (net (code "189") (name "Net-(IC4-VOUT)") (class "Default")
      (node (ref "IC4") (pin "6") (pinfunction "VOUT_6") (pintype "passive"))
      (node (ref "J32") (pin "P$1") (pinfunction "1_P$1") (pintype "bidirectional"))
    )
    (net (code "190") (name "Net-(J2-2)") (class "Default")
      (node (ref "J2") (pin "P$2") (pinfunction "2_P$2") (pintype "bidirectional"))
      (node (ref "J3") (pin "P$2") (pinfunction "2_P$2") (pintype "bidirectional"))
      (node (ref "U2") (pin "+") (pinfunction "+_+") (pintype "bidirectional"))
    )
    (net (code "191") (name "Net-(J4-2)") (class "Default")
      (node (ref "C42") (pin "P$2") (pinfunction "P$2_P$2") (pintype "bidirectional"))
      (node (ref "C43") (pin "P$2") (pinfunction "P$2_P$2") (pintype "bidirectional"))
      (node (ref "C44") (pin "P$2") (pinfunction "P$2_P$2") (pintype "bidirectional"))
      (node (ref "C45") (pin "P$2") (pinfunction "P$2_P$2") (pintype "bidirectional"))
      (node (ref "J4") (pin "P$2") (pinfunction "2_P$2") (pintype "bidirectional"))
      (node (ref "J5") (pin "P$2") (pinfunction "2_P$2") (pintype "bidirectional"))
      (node (ref "U10") (pin "P$21") (pinfunction "VDDD_P$21") (pintype "bidirectional"))
      (node (ref "U10") (pin "P$26") (pinfunction "VDDC_P$26") (pintype "bidirectional"))
      (node (ref "U10") (pin "P$29") (pinfunction "VDDB_P$29") (pintype "bidirectional"))
      (node (ref "U10") (pin "P$34") (pinfunction "VDDA_P$34") (pintype "bidirectional"))
    )
    (net (code "192") (name "Net-(J6-2)") (class "Default")
      (node (ref "C51") (pin "P$2") (pinfunction "P$2_P$2") (pintype "bidirectional"))
      (node (ref "C52") (pin "P$2") (pinfunction "P$2_P$2") (pintype "bidirectional"))
      (node (ref "C53") (pin "P$2") (pinfunction "P$2_P$2") (pintype "bidirectional"))
      (node (ref "C54") (pin "P$2") (pinfunction "P$2_P$2") (pintype "bidirectional"))
      (node (ref "J6") (pin "P$2") (pinfunction "2_P$2") (pintype "bidirectional"))
      (node (ref "J7") (pin "P$2") (pinfunction "2_P$2") (pintype "bidirectional"))
      (node (ref "U11") (pin "P$21") (pinfunction "VDDD_P$21") (pintype "bidirectional"))
      (node (ref "U11") (pin "P$26") (pinfunction "VDDC_P$26") (pintype "bidirectional"))
      (node (ref "U11") (pin "P$29") (pinfunction "VDDB_P$29") (pintype "bidirectional"))
      (node (ref "U11") (pin "P$34") (pinfunction "VDDA_P$34") (pintype "bidirectional"))
    )
    (net (code "193") (name "Net-(J8-2)") (class "Default")
      (node (ref "J8") (pin "P$2") (pinfunction "2_P$2") (pintype "bidirectional"))
      (node (ref "U9") (pin "P$5") (pinfunction "RST_AB_P$5") (pintype "bidirectional"))
    )
    (net (code "194") (name "Net-(J9-2)") (class "Default")
      (node (ref "J9") (pin "P$2") (pinfunction "2_P$2") (pintype "bidirectional"))
      (node (ref "U9") (pin "P$15") (pinfunction "RST_CD_P$15") (pintype "bidirectional"))
    )
    (net (code "195") (name "Net-(J10-2)") (class "Default")
      (node (ref "J10") (pin "P$2") (pinfunction "2_P$2") (pintype "bidirectional"))
      (node (ref "U9") (pin "P$13") (pinfunction "M1_P$13") (pintype "bidirectional"))
    )
    (net (code "196") (name "Net-(J11-2)") (class "Default")
      (node (ref "J11") (pin "P$2") (pinfunction "2_P$2") (pintype "bidirectional"))
      (node (ref "U9") (pin "P$12") (pinfunction "M2_P$12") (pintype "bidirectional"))
    )
    (net (code "197") (name "Net-(J12-2)") (class "Default")
      (node (ref "J12") (pin "P$2") (pinfunction "2_P$2") (pintype "bidirectional"))
      (node (ref "U10") (pin "P$5") (pinfunction "RST_AB_P$5") (pintype "bidirectional"))
    )
    (net (code "198") (name "Net-(J13-2)") (class "Default")
      (node (ref "J13") (pin "P$2") (pinfunction "2_P$2") (pintype "bidirectional"))
      (node (ref "U10") (pin "P$15") (pinfunction "RST_CD_P$15") (pintype "bidirectional"))
    )
    (net (code "199") (name "Net-(J14-2)") (class "Default")
      (node (ref "J14") (pin "P$2") (pinfunction "2_P$2") (pintype "bidirectional"))
      (node (ref "U11") (pin "P$5") (pinfunction "RST_AB_P$5") (pintype "bidirectional"))
    )
    (net (code "200") (name "Net-(J15-2)") (class "Default")
      (node (ref "J15") (pin "P$2") (pinfunction "2_P$2") (pintype "bidirectional"))
      (node (ref "U11") (pin "P$15") (pinfunction "RST_CD_P$15") (pintype "bidirectional"))
    )
    (net (code "201") (name "Net-(J16-2)") (class "Default")
      (node (ref "J16") (pin "P$2") (pinfunction "2_P$2") (pintype "bidirectional"))
      (node (ref "U10") (pin "P$13") (pinfunction "M1_P$13") (pintype "bidirectional"))
    )
    (net (code "202") (name "Net-(J17-2)") (class "Default")
      (node (ref "J17") (pin "P$2") (pinfunction "2_P$2") (pintype "bidirectional"))
      (node (ref "U10") (pin "P$12") (pinfunction "M2_P$12") (pintype "bidirectional"))
    )
    (net (code "203") (name "Net-(J18-2)") (class "Default")
      (node (ref "J18") (pin "P$2") (pinfunction "2_P$2") (pintype "bidirectional"))
      (node (ref "U11") (pin "P$13") (pinfunction "M1_P$13") (pintype "bidirectional"))
    )
    (net (code "204") (name "Net-(J19-2)") (class "Default")
      (node (ref "J19") (pin "P$2") (pinfunction "2_P$2") (pintype "bidirectional"))
      (node (ref "U11") (pin "P$12") (pinfunction "M2_P$12") (pintype "bidirectional"))
    )
    (net (code "205") (name "Net-(J20-2)") (class "Default")
      (node (ref "J20") (pin "P$2") (pinfunction "2_P$2") (pintype "bidirectional"))
      (node (ref "U14") (pin "P$5") (pinfunction "RST_AB_P$5") (pintype "bidirectional"))
    )
    (net (code "206") (name "Net-(J21-2)") (class "Default")
      (node (ref "J21") (pin "P$2") (pinfunction "2_P$2") (pintype "bidirectional"))
      (node (ref "U14") (pin "P$15") (pinfunction "RST_CD_P$15") (pintype "bidirectional"))
    )
    (net (code "207") (name "Net-(J22-2)") (class "Default")
      (node (ref "J22") (pin "P$2") (pinfunction "2_P$2") (pintype "bidirectional"))
      (node (ref "U14") (pin "P$13") (pinfunction "M1_P$13") (pintype "bidirectional"))
    )
    (net (code "208") (name "Net-(J23-2)") (class "Default")
      (node (ref "J23") (pin "P$2") (pinfunction "2_P$2") (pintype "bidirectional"))
      (node (ref "U14") (pin "P$12") (pinfunction "M2_P$12") (pintype "bidirectional"))
    )
    (net (code "209") (name "Net-(J26-2)") (class "Default")
      (node (ref "J26") (pin "P$2") (pinfunction "2_P$2") (pintype "bidirectional"))
      (node (ref "U17") (pin "VCC") (pinfunction "VCC_VCC") (pintype "bidirectional"))
    )
    (net (code "210") (name "Net-(J27-2)") (class "Default")
      (node (ref "J27") (pin "P$2") (pinfunction "2_P$2") (pintype "bidirectional"))
      (node (ref "U19") (pin "VCC") (pinfunction "VCC_VCC") (pintype "bidirectional"))
    )
    (net (code "211") (name "Net-(J50-2)") (class "Default")
      (node (ref "J50") (pin "P$2") (pinfunction "2_P$2") (pintype "bidirectional"))
      (node (ref "J51") (pin "P$1") (pinfunction "1_P$1") (pintype "bidirectional"))
      (node (ref "U37") (pin "11") (pinfunction "FSYNC_11") (pintype "bidirectional"))
    )
    (net (code "212") (name "Net-(K1-COM-Pad6)") (class "Default")
      (node (ref "K1") (pin "6") (pinfunction "COM_6") (pintype "bidirectional"))
      (node (ref "K1") (pin "7") (pinfunction "COM_7") (pintype "bidirectional"))
      (node (ref "U17") (pin "U") (pinfunction "U_U") (pintype "bidirectional"))
    )
    (net (code "213") (name "Net-(K2-COM-Pad6)") (class "Default")
      (node (ref "K2") (pin "6") (pinfunction "COM_6") (pintype "bidirectional"))
      (node (ref "K2") (pin "7") (pinfunction "COM_7") (pintype "bidirectional"))
      (node (ref "U17") (pin "W") (pinfunction "W_W") (pintype "bidirectional"))
    )
    (net (code "214") (name "Net-(K3-COM-Pad6)") (class "Default")
      (node (ref "K3") (pin "6") (pinfunction "COM_6") (pintype "bidirectional"))
      (node (ref "K3") (pin "7") (pinfunction "COM_7") (pintype "bidirectional"))
      (node (ref "U19") (pin "U") (pinfunction "U_U") (pintype "bidirectional"))
    )
    (net (code "215") (name "Net-(K4-COM-Pad6)") (class "Default")
      (node (ref "K4") (pin "6") (pinfunction "COM_6") (pintype "bidirectional"))
      (node (ref "K4") (pin "7") (pinfunction "COM_7") (pintype "bidirectional"))
      (node (ref "U19") (pin "W") (pinfunction "W_W") (pintype "bidirectional"))
    )
    (net (code "216") (name "Net-(L1-2)") (class "Default")
      (node (ref "C55") (pin "P$2") (pinfunction "P$2_P$2") (pintype "bidirectional"))
      (node (ref "L1") (pin "P$2") (pinfunction "2_P$2") (pintype "bidirectional"))
      (node (ref "U9") (pin "P$33") (pinfunction "OUTA_P$33") (pintype "bidirectional"))
    )
    (net (code "217") (name "Net-(L2-2)") (class "Default")
      (node (ref "C60") (pin "P$2") (pinfunction "P$2_P$2") (pintype "bidirectional"))
      (node (ref "L2") (pin "P$2") (pinfunction "2_P$2") (pintype "bidirectional"))
      (node (ref "U9") (pin "P$30") (pinfunction "OUTB_P$30") (pintype "bidirectional"))
    )
    (net (code "218") (name "Net-(L3-1)") (class "Default")
      (node (ref "L3") (pin "P$1") (pinfunction "1_P$1") (pintype "bidirectional"))
      (node (ref "L4") (pin "P$1") (pinfunction "1_P$1") (pintype "bidirectional"))
      (node (ref "R24") (pin "P$1") (pinfunction "P$1_P$1") (pintype "bidirectional"))
      (node (ref "U12") (pin "P$3") (pinfunction "IN-_P$3") (pintype "bidirectional"))
    )
    (net (code "219") (name "Net-(L3-2)") (class "Default")
      (node (ref "C62") (pin "P$2") (pinfunction "P$2_P$2") (pintype "bidirectional"))
      (node (ref "L3") (pin "P$2") (pinfunction "2_P$2") (pintype "bidirectional"))
      (node (ref "U9") (pin "P$25") (pinfunction "OUTC_P$25") (pintype "bidirectional"))
    )
    (net (code "220") (name "Net-(L4-2)") (class "Default")
      (node (ref "C65") (pin "P$2") (pinfunction "P$2_P$2") (pintype "bidirectional"))
      (node (ref "L4") (pin "P$2") (pinfunction "2_P$2") (pintype "bidirectional"))
      (node (ref "U9") (pin "P$22") (pinfunction "OUTD_P$22") (pintype "bidirectional"))
    )
    (net (code "221") (name "Net-(L5-2)") (class "Default")
      (node (ref "C85") (pin "P$2") (pinfunction "P$2_P$2") (pintype "bidirectional"))
      (node (ref "L5") (pin "P$2") (pinfunction "2_P$2") (pintype "bidirectional"))
      (node (ref "U14") (pin "P$33") (pinfunction "OUTA_P$33") (pintype "bidirectional"))
    )
    (net (code "222") (name "Net-(L6-2)") (class "Default")
      (node (ref "C86") (pin "P$2") (pinfunction "P$2_P$2") (pintype "bidirectional"))
      (node (ref "L6") (pin "P$2") (pinfunction "2_P$2") (pintype "bidirectional"))
      (node (ref "U14") (pin "P$30") (pinfunction "OUTB_P$30") (pintype "bidirectional"))
    )
    (net (code "223") (name "Net-(L7-1)") (class "Default")
      (node (ref "L7") (pin "P$1") (pinfunction "1_P$1") (pintype "bidirectional"))
      (node (ref "L8") (pin "P$1") (pinfunction "1_P$1") (pintype "bidirectional"))
      (node (ref "R32") (pin "P$1") (pinfunction "P$1_P$1") (pintype "bidirectional"))
      (node (ref "U15") (pin "P$2") (pinfunction "IN+_P$2") (pintype "bidirectional"))
    )
    (net (code "224") (name "Net-(L7-2)") (class "Default")
      (node (ref "C87") (pin "P$2") (pinfunction "P$2_P$2") (pintype "bidirectional"))
      (node (ref "L7") (pin "P$2") (pinfunction "2_P$2") (pintype "bidirectional"))
      (node (ref "U14") (pin "P$25") (pinfunction "OUTC_P$25") (pintype "bidirectional"))
    )
    (net (code "225") (name "Net-(L8-2)") (class "Default")
      (node (ref "C88") (pin "P$2") (pinfunction "P$2_P$2") (pintype "bidirectional"))
      (node (ref "L8") (pin "P$2") (pinfunction "2_P$2") (pintype "bidirectional"))
      (node (ref "U14") (pin "P$22") (pinfunction "OUTD_P$22") (pintype "bidirectional"))
    )
    (net (code "226") (name "Net-(R9-P$1)") (class "Default")
      (node (ref "R9") (pin "1") (pinfunction "P$1_1") (pintype "bidirectional"))
      (node (ref "U3") (pin "P$5") (pinfunction "RSET_P$5") (pintype "bidirectional"))
    )
    (net (code "227") (name "Net-(R10-P$2)") (class "Default")
      (node (ref "D4") (pin "A") (pinfunction "A_A") (pintype "bidirectional"))
      (node (ref "R10") (pin "2") (pinfunction "P$2_2") (pintype "bidirectional"))
    )
    (net (code "228") (name "Net-(R11-P$2)") (class "Default")
      (node (ref "D5") (pin "A") (pinfunction "A_A") (pintype "bidirectional"))
      (node (ref "R11") (pin "2") (pinfunction "P$2_2") (pintype "bidirectional"))
    )
    (net (code "229") (name "Net-(R12-P$2)") (class "Default")
      (node (ref "D6") (pin "A") (pinfunction "A_A") (pintype "bidirectional"))
      (node (ref "R12") (pin "2") (pinfunction "P$2_2") (pintype "bidirectional"))
    )
    (net (code "230") (name "Net-(R13-P$2)") (class "Default")
      (node (ref "D7") (pin "A") (pinfunction "A_A") (pintype "bidirectional"))
      (node (ref "R13") (pin "2") (pinfunction "P$2_2") (pintype "bidirectional"))
    )
    (net (code "231") (name "Net-(R14-P$2)") (class "Default")
      (node (ref "D8") (pin "A") (pinfunction "A_A") (pintype "bidirectional"))
      (node (ref "R14") (pin "2") (pinfunction "P$2_2") (pintype "bidirectional"))
    )
    (net (code "232") (name "Net-(R15-P$2)") (class "Default")
      (node (ref "R15") (pin "2") (pinfunction "P$2_2") (pintype "bidirectional"))
      (node (ref "R16") (pin "1") (pinfunction "P$1_1") (pintype "bidirectional"))
      (node (ref "U4") (pin "P$6") (pinfunction "ADJ_P$6") (pintype "bidirectional"))
    )
    (net (code "233") (name "Net-(R17-P$2)") (class "Default")
      (node (ref "R17") (pin "2") (pinfunction "P$2_2") (pintype "bidirectional"))
      (node (ref "R18") (pin "1") (pinfunction "P$1_1") (pintype "bidirectional"))
      (node (ref "U5") (pin "P$6") (pinfunction "ADJ_P$6") (pintype "bidirectional"))
    )
    (net (code "234") (name "Net-(R19-P$2)") (class "Default")
      (node (ref "R19") (pin "2") (pinfunction "P$2_2") (pintype "bidirectional"))
      (node (ref "R20") (pin "1") (pinfunction "P$1_1") (pintype "bidirectional"))
      (node (ref "U6") (pin "P$6") (pinfunction "ADJ_P$6") (pintype "bidirectional"))
    )
    (net (code "235") (name "Net-(R21-P$1)") (class "Default")
      (node (ref "R21") (pin "1") (pinfunction "P$1_1") (pintype "bidirectional"))
      (node (ref "U7") (pin "P$8") (pinfunction "OUT_P$8") (pintype "bidirectional"))
    )
    (net (code "236") (name "Net-(R22-P$1)") (class "Default")
      (node (ref "R22") (pin "1") (pinfunction "P$1_1") (pintype "bidirectional"))
      (node (ref "U8") (pin "P$8") (pinfunction "OUT_P$8") (pintype "bidirectional"))
    )
    (net (code "237") (name "Net-(R26-P$1)") (class "Default")
      (node (ref "R26") (pin "1") (pinfunction "P$1_1") (pintype "bidirectional"))
      (node (ref "U9") (pin "P$7") (pinfunction "OC_ADJ_P$7") (pintype "bidirectional"))
    )
    (net (code "238") (name "Net-(R27-P$1)") (class "Default")
      (node (ref "R27") (pin "1") (pinfunction "P$1_1") (pintype "bidirectional"))
      (node (ref "U12") (pin "P$8") (pinfunction "OUT_P$8") (pintype "bidirectional"))
    )
    (net (code "239") (name "Net-(R28-P$1)") (class "Default")
      (node (ref "R28") (pin "1") (pinfunction "P$1_1") (pintype "bidirectional"))
      (node (ref "U10") (pin "P$7") (pinfunction "OC_ADJ_P$7") (pintype "bidirectional"))
    )
    (net (code "240") (name "Net-(R30-P$1)") (class "Default")
      (node (ref "R30") (pin "1") (pinfunction "P$1_1") (pintype "bidirectional"))
      (node (ref "U11") (pin "P$7") (pinfunction "OC_ADJ_P$7") (pintype "bidirectional"))
    )
    (net (code "241") (name "Net-(R31-P$1)") (class "Default")
      (node (ref "R31") (pin "1") (pinfunction "P$1_1") (pintype "bidirectional"))
      (node (ref "U13") (pin "P$8") (pinfunction "OUT_P$8") (pintype "bidirectional"))
    )
    (net (code "242") (name "Net-(R33-P$1)") (class "Default")
      (node (ref "R33") (pin "1") (pinfunction "P$1_1") (pintype "bidirectional"))
      (node (ref "U14") (pin "P$7") (pinfunction "OC_ADJ_P$7") (pintype "bidirectional"))
    )
    (net (code "243") (name "Net-(R34-P$1)") (class "Default")
      (node (ref "R34") (pin "1") (pinfunction "P$1_1") (pintype "bidirectional"))
      (node (ref "U15") (pin "P$8") (pinfunction "OUT_P$8") (pintype "bidirectional"))
    )
    (net (code "244") (name "Net-(R35-P$1)") (class "Default")
      (node (ref "R35") (pin "1") (pinfunction "P$1_1") (pintype "bidirectional"))
      (node (ref "U16") (pin "P$8") (pinfunction "OUT_P$8") (pintype "bidirectional"))
    )
    (net (code "245") (name "Net-(R37-P$1)") (class "Default")
      (node (ref "R37") (pin "1") (pinfunction "P$1_1") (pintype "bidirectional"))
      (node (ref "U18") (pin "P$8") (pinfunction "OUT_P$8") (pintype "bidirectional"))
    )
    (net (code "246") (name "Net-(R41-P$1)") (class "Default")
      (node (ref "CON20") (pin "3") (pinfunction "3_3") (pintype "bidirectional"))
      (node (ref "R41") (pin "1") (pinfunction "P$1_1") (pintype "bidirectional"))
    )
    (net (code "247") (name "Net-(R42-P$1)") (class "Default")
      (node (ref "CON22") (pin "3") (pinfunction "3_3") (pintype "bidirectional"))
      (node (ref "R42") (pin "1") (pinfunction "P$1_1") (pintype "bidirectional"))
    )
    (net (code "248") (name "Net-(R44-P$2)") (class "Default")
      (node (ref "CON21") (pin "1") (pinfunction "1_1") (pintype "bidirectional"))
      (node (ref "R44") (pin "2") (pinfunction "P$2_2") (pintype "bidirectional"))
      (node (ref "R45") (pin "P$1") (pinfunction "P$1_P$1") (pintype "bidirectional"))
    )
    (net (code "249") (name "Net-(R46-P$1)") (class "Default")
      (node (ref "CON23") (pin "3") (pinfunction "3_3") (pintype "bidirectional"))
      (node (ref "R46") (pin "1") (pinfunction "P$1_1") (pintype "bidirectional"))
    )
    (net (code "250") (name "Net-(R47-P$1)") (class "Default")
      (node (ref "CON25") (pin "3") (pinfunction "3_3") (pintype "bidirectional"))
      (node (ref "R47") (pin "1") (pinfunction "P$1_1") (pintype "bidirectional"))
    )
    (net (code "251") (name "Net-(R49-P$2)") (class "Default")
      (node (ref "CON24") (pin "1") (pinfunction "1_1") (pintype "bidirectional"))
      (node (ref "R49") (pin "2") (pinfunction "P$2_2") (pintype "bidirectional"))
      (node (ref "R52") (pin "P$1") (pinfunction "P$1_P$1") (pintype "bidirectional"))
    )
    (net (code "252") (name "Net-(R53-P$1)") (class "Default")
      (node (ref "CON28") (pin "3") (pinfunction "3_3") (pintype "bidirectional"))
      (node (ref "R53") (pin "1") (pinfunction "P$1_1") (pintype "bidirectional"))
    )
    (net (code "253") (name "Net-(R54-P$1)") (class "Default")
      (node (ref "CON30") (pin "3") (pinfunction "3_3") (pintype "bidirectional"))
      (node (ref "R54") (pin "1") (pinfunction "P$1_1") (pintype "bidirectional"))
    )
    (net (code "254") (name "Net-(R56-P$2)") (class "Default")
      (node (ref "CON29") (pin "1") (pinfunction "1_1") (pintype "bidirectional"))
      (node (ref "R56") (pin "2") (pinfunction "P$2_2") (pintype "bidirectional"))
      (node (ref "R57") (pin "P$1") (pinfunction "P$1_P$1") (pintype "bidirectional"))
    )
    (net (code "255") (name "Net-(R58-P$2)") (class "Default")
      (node (ref "CON32") (pin "4") (pinfunction "4_4") (pintype "bidirectional"))
      (node (ref "R58") (pin "2") (pinfunction "P$2_2") (pintype "bidirectional"))
    )
    (net (code "256") (name "Net-(R59-P$1)") (class "Default")
      (node (ref "CON33") (pin "3") (pinfunction "3_3") (pintype "bidirectional"))
      (node (ref "R59") (pin "1") (pinfunction "P$1_1") (pintype "bidirectional"))
    )
    (net (code "257") (name "Net-(R60-P$1)") (class "Default")
      (node (ref "CON35") (pin "3") (pinfunction "3_3") (pintype "bidirectional"))
      (node (ref "R60") (pin "1") (pinfunction "P$1_1") (pintype "bidirectional"))
    )
    (net (code "258") (name "Net-(R61-P$2)") (class "Default")
      (node (ref "CON32") (pin "3") (pinfunction "3_3") (pintype "bidirectional"))
      (node (ref "R61") (pin "2") (pinfunction "P$2_2") (pintype "bidirectional"))
    )
    (net (code "259") (name "Net-(R62-P$2)") (class "Default")
      (node (ref "CON32") (pin "2") (pinfunction "2_2") (pintype "bidirectional"))
      (node (ref "R62") (pin "2") (pinfunction "P$2_2") (pintype "bidirectional"))
    )
    (net (code "260") (name "Net-(R64-P$2)") (class "Default")
      (node (ref "CON34") (pin "1") (pinfunction "1_1") (pintype "bidirectional"))
      (node (ref "R64") (pin "2") (pinfunction "P$2_2") (pintype "bidirectional"))
      (node (ref "R65") (pin "P$1") (pinfunction "P$1_P$1") (pintype "bidirectional"))
    )
    (net (code "261") (name "Net-(R66-P$1)") (class "Default")
      (node (ref "CON37") (pin "3") (pinfunction "3_3") (pintype "bidirectional"))
      (node (ref "R66") (pin "1") (pinfunction "P$1_1") (pintype "bidirectional"))
    )
    (net (code "262") (name "Net-(R67-P$1)") (class "Default")
      (node (ref "CON39") (pin "3") (pinfunction "3_3") (pintype "bidirectional"))
      (node (ref "R67") (pin "1") (pinfunction "P$1_1") (pintype "bidirectional"))
    )
    (net (code "263") (name "Net-(R69-P$2)") (class "Default")
      (node (ref "CON38") (pin "1") (pinfunction "1_1") (pintype "bidirectional"))
      (node (ref "R69") (pin "2") (pinfunction "P$2_2") (pintype "bidirectional"))
      (node (ref "R70") (pin "P$1") (pinfunction "P$1_P$1") (pintype "bidirectional"))
    )
    (net (code "264") (name "Net-(R71-P$2)") (class "Default")
      (node (ref "CON41") (pin "4") (pinfunction "4_4") (pintype "bidirectional"))
      (node (ref "R71") (pin "2") (pinfunction "P$2_2") (pintype "bidirectional"))
    )
    (net (code "265") (name "Net-(R72-P$2)") (class "Default")
      (node (ref "CON41") (pin "3") (pinfunction "3_3") (pintype "bidirectional"))
      (node (ref "R72") (pin "2") (pinfunction "P$2_2") (pintype "bidirectional"))
    )
    (net (code "266") (name "Net-(R73-P$2)") (class "Default")
      (node (ref "CON41") (pin "2") (pinfunction "2_2") (pintype "bidirectional"))
      (node (ref "R73") (pin "2") (pinfunction "P$2_2") (pintype "bidirectional"))
    )
    (net (code "267") (name "Net-(R74-P$1)") (class "Default")
      (node (ref "CON42") (pin "3") (pinfunction "3_3") (pintype "bidirectional"))
      (node (ref "R74") (pin "1") (pinfunction "P$1_1") (pintype "bidirectional"))
    )
    (net (code "268") (name "Net-(R75-P$1)") (class "Default")
      (node (ref "CON44") (pin "3") (pinfunction "3_3") (pintype "bidirectional"))
      (node (ref "R75") (pin "1") (pinfunction "P$1_1") (pintype "bidirectional"))
    )
    (net (code "269") (name "Net-(R77-P$2)") (class "Default")
      (node (ref "CON43") (pin "1") (pinfunction "1_1") (pintype "bidirectional"))
      (node (ref "R77") (pin "2") (pinfunction "P$2_2") (pintype "bidirectional"))
      (node (ref "R78") (pin "P$1") (pinfunction "P$1_P$1") (pintype "bidirectional"))
    )
    (net (code "270") (name "Net-(R79-P$1)") (class "Default")
      (node (ref "CON46") (pin "3") (pinfunction "3_3") (pintype "bidirectional"))
      (node (ref "R79") (pin "1") (pinfunction "P$1_1") (pintype "bidirectional"))
    )
    (net (code "271") (name "Net-(R80-P$1)") (class "Default")
      (node (ref "CON48") (pin "3") (pinfunction "3_3") (pintype "bidirectional"))
      (node (ref "R80") (pin "1") (pinfunction "P$1_1") (pintype "bidirectional"))
    )
    (net (code "272") (name "Net-(R82-P$2)") (class "Default")
      (node (ref "CON47") (pin "1") (pinfunction "1_1") (pintype "bidirectional"))
      (node (ref "R82") (pin "2") (pinfunction "P$2_2") (pintype "bidirectional"))
      (node (ref "R83") (pin "P$1") (pinfunction "P$1_P$1") (pintype "bidirectional"))
    )
    (net (code "273") (name "Net-(R84-P$1)") (class "Default")
      (node (ref "CON50") (pin "3") (pinfunction "3_3") (pintype "bidirectional"))
      (node (ref "R84") (pin "1") (pinfunction "P$1_1") (pintype "bidirectional"))
    )
    (net (code "274") (name "Net-(R85-P$1)") (class "Default")
      (node (ref "CON52") (pin "3") (pinfunction "3_3") (pintype "bidirectional"))
      (node (ref "R85") (pin "1") (pinfunction "P$1_1") (pintype "bidirectional"))
    )
    (net (code "275") (name "Net-(R87-P$2)") (class "Default")
      (node (ref "CON51") (pin "1") (pinfunction "1_1") (pintype "bidirectional"))
      (node (ref "R87") (pin "2") (pinfunction "P$2_2") (pintype "bidirectional"))
      (node (ref "R88") (pin "P$1") (pinfunction "P$1_P$1") (pintype "bidirectional"))
    )
    (net (code "276") (name "Net-(R89-P$1)") (class "Default")
      (node (ref "R89") (pin "1") (pinfunction "P$1_1") (pintype "bidirectional"))
      (node (ref "U20") (pin "12") (pinfunction "NRESET_12") (pintype "bidirectional"))
    )
    (net (code "277") (name "Net-(R91-P$1)") (class "Default")
      (node (ref "R91") (pin "1") (pinfunction "P$1_1") (pintype "bidirectional"))
      (node (ref "U21") (pin "P$2") (pinfunction "GPIO2_P$2") (pintype "bidirectional"))
    )
    (net (code "278") (name "Net-(R92-P$1)") (class "Default")
      (node (ref "R92") (pin "1") (pinfunction "P$1_1") (pintype "bidirectional"))
      (node (ref "U21") (pin "P$3") (pinfunction "GPIO9_P$3") (pintype "bidirectional"))
    )
    (net (code "279") (name "Net-(R92-P$2)") (class "Default")
      (node (ref "D9") (pin "C") (pinfunction "C_C") (pintype "bidirectional"))
      (node (ref "R92") (pin "2") (pinfunction "P$2_2") (pintype "bidirectional"))
    )
    (net (code "280") (name "Net-(R93-P$1)") (class "Default")
      (node (ref "R93") (pin "1") (pinfunction "P$1_1") (pintype "bidirectional"))
      (node (ref "U22") (pin "P$2") (pinfunction "GPIO2_P$2") (pintype "bidirectional"))
    )
    (net (code "281") (name "Net-(R94-P$1)") (class "Default")
      (node (ref "R94") (pin "1") (pinfunction "P$1_1") (pintype "bidirectional"))
      (node (ref "U22") (pin "P$3") (pinfunction "GPIO9_P$3") (pintype "bidirectional"))
    )
    (net (code "282") (name "Net-(R94-P$2)") (class "Default")
      (node (ref "D10") (pin "C") (pinfunction "C_C") (pintype "bidirectional"))
      (node (ref "R94") (pin "2") (pinfunction "P$2_2") (pintype "bidirectional"))
    )
    (net (code "283") (name "Net-(R95-P$2)") (class "Default")
      (node (ref "R95") (pin "2") (pinfunction "P$2_2") (pintype "bidirectional"))
      (node (ref "U20") (pin "50") (pinfunction "EXRES_50") (pintype "bidirectional"))
    )
    (net (code "284") (name "Net-(R96-P$2)") (class "Default")
      (node (ref "R96") (pin "2") (pinfunction "P$2_2") (pintype "bidirectional"))
      (node (ref "U20") (pin "63") (pinfunction "USBRBIAS_63") (pintype "bidirectional"))
    )
    (net (code "285") (name "Net-(R97-P$2)") (class "Default")
      (node (ref "R97") (pin "2") (pinfunction "P$2_2") (pintype "bidirectional"))
      (node (ref "R98") (pin "1") (pinfunction "P$1_1") (pintype "bidirectional"))
      (node (ref "U24") (pin "P$3") (pinfunction "-_P$3") (pintype "bidirectional"))
    )
    (net (code "286") (name "Net-(R107-P$1)") (class "Default")
      (node (ref "R107") (pin "1") (pinfunction "P$1_1") (pintype "bidirectional"))
      (node (ref "U33") (pin "P$5") (pinfunction "RST_P$5") (pintype "bidirectional"))
      (node (ref "U34") (pin "P$4") (pinfunction "P2_P$4") (pintype "bidirectional"))
    )
    (net (code "287") (name "Net-(R108-P$1)") (class "Default")
      (node (ref "CON62") (pin "3") (pinfunction "3_3") (pintype "bidirectional"))
      (node (ref "R108") (pin "1") (pinfunction "P$1_1") (pintype "bidirectional"))
      (node (ref "U34") (pin "P$1") (pinfunction "RST_P$1") (pintype "bidirectional"))
    )
    (net (code "288") (name "Net-(R109-P$1)") (class "Default")
      (node (ref "R109") (pin "1") (pinfunction "P$1_1") (pintype "bidirectional"))
      (node (ref "U36") (pin "P$4") (pinfunction "RST_P$4") (pintype "bidirectional"))
      (node (ref "U39") (pin "P$4") (pinfunction "P2_P$4") (pintype "bidirectional"))
    )
    (net (code "289") (name "Net-(R110-P$1)") (class "Default")
      (node (ref "CON64") (pin "3") (pinfunction "3_3") (pintype "bidirectional"))
      (node (ref "R110") (pin "1") (pinfunction "P$1_1") (pintype "bidirectional"))
      (node (ref "U39") (pin "P$1") (pinfunction "RST_P$1") (pintype "bidirectional"))
    )
    (net (code "290") (name "Net-(T1-D)") (class "Default")
      (node (ref "T1") (pin "P$3") (pinfunction "D_P$3") (pintype "bidirectional"))
      (node (ref "U2") (pin "-") (pinfunction "-_-") (pintype "bidirectional"))
    )
    (net (code "291") (name "Net-(T2-D)") (class "Default")
      (node (ref "K1") (pin "11") (pinfunction "C_11") (pintype "bidirectional"))
      (node (ref "K2") (pin "2") (pinfunction "C_2") (pintype "bidirectional"))
      (node (ref "T2") (pin "P$3") (pinfunction "D_P$3") (pintype "bidirectional"))
    )
    (net (code "292") (name "Net-(T3-D)") (class "Default")
      (node (ref "K3") (pin "2") (pinfunction "C_2") (pintype "bidirectional"))
      (node (ref "K4") (pin "11") (pinfunction "C_11") (pintype "bidirectional"))
      (node (ref "T3") (pin "P$3") (pinfunction "D_P$3") (pintype "bidirectional"))
    )
    (net (code "293") (name "Net-(U9-BSTA)") (class "Default")
      (node (ref "C55") (pin "P$1") (pinfunction "P$1_P$1") (pintype "bidirectional"))
      (node (ref "U9") (pin "P$35") (pinfunction "BSTA_P$35") (pintype "bidirectional"))
    )
    (net (code "294") (name "Net-(U9-BSTB)") (class "Default")
      (node (ref "C60") (pin "P$1") (pinfunction "P$1_P$1") (pintype "bidirectional"))
      (node (ref "U9") (pin "P$28") (pinfunction "BSTB_P$28") (pintype "bidirectional"))
    )
    (net (code "295") (name "Net-(U9-BSTC)") (class "Default")
      (node (ref "C62") (pin "P$1") (pinfunction "P$1_P$1") (pintype "bidirectional"))
      (node (ref "U9") (pin "P$27") (pinfunction "BSTC_P$27") (pintype "bidirectional"))
    )
    (net (code "296") (name "Net-(U9-BSTD)") (class "Default")
      (node (ref "C65") (pin "P$1") (pinfunction "P$1_P$1") (pintype "bidirectional"))
      (node (ref "U9") (pin "P$20") (pinfunction "BSTD_P$20") (pintype "bidirectional"))
    )
    (net (code "297") (name "Net-(U10-BSTA)") (class "Default")
      (node (ref "C61") (pin "P$1") (pinfunction "P$1_P$1") (pintype "bidirectional"))
      (node (ref "U10") (pin "P$35") (pinfunction "BSTA_P$35") (pintype "bidirectional"))
    )
    (net (code "298") (name "Net-(U10-BSTB)") (class "Default")
      (node (ref "C64") (pin "P$1") (pinfunction "P$1_P$1") (pintype "bidirectional"))
      (node (ref "U10") (pin "P$28") (pinfunction "BSTB_P$28") (pintype "bidirectional"))
    )
    (net (code "299") (name "Net-(U10-BSTC)") (class "Default")
      (node (ref "C68") (pin "P$1") (pinfunction "P$1_P$1") (pintype "bidirectional"))
      (node (ref "U10") (pin "P$27") (pinfunction "BSTC_P$27") (pintype "bidirectional"))
    )
    (net (code "300") (name "Net-(U10-BSTD)") (class "Default")
      (node (ref "C70") (pin "P$1") (pinfunction "P$1_P$1") (pintype "bidirectional"))
      (node (ref "U10") (pin "P$20") (pinfunction "BSTD_P$20") (pintype "bidirectional"))
    )
    (net (code "301") (name "Net-(U10-OUTA)") (class "Default")
      (node (ref "C61") (pin "P$2") (pinfunction "P$2_P$2") (pintype "bidirectional"))
      (node (ref "R23") (pin "P$1") (pinfunction "P$1_P$1") (pintype "bidirectional"))
      (node (ref "U10") (pin "P$33") (pinfunction "OUTA_P$33") (pintype "bidirectional"))
      (node (ref "U7") (pin "P$2") (pinfunction "IN+_P$2") (pintype "bidirectional"))
    )
    (net (code "302") (name "Net-(U10-OUTD)") (class "Default")
      (node (ref "C70") (pin "P$2") (pinfunction "P$2_P$2") (pintype "bidirectional"))
      (node (ref "R29") (pin "P$1") (pinfunction "P$1_P$1") (pintype "bidirectional"))
      (node (ref "U10") (pin "P$22") (pinfunction "OUTD_P$22") (pintype "bidirectional"))
      (node (ref "U13") (pin "P$3") (pinfunction "IN-_P$3") (pintype "bidirectional"))
    )
    (net (code "303") (name "Net-(U11-BSTA)") (class "Default")
      (node (ref "C63") (pin "P$1") (pinfunction "P$1_P$1") (pintype "bidirectional"))
      (node (ref "U11") (pin "P$35") (pinfunction "BSTA_P$35") (pintype "bidirectional"))
    )
    (net (code "304") (name "Net-(U11-BSTB)") (class "Default")
      (node (ref "C66") (pin "P$1") (pinfunction "P$1_P$1") (pintype "bidirectional"))
      (node (ref "U11") (pin "P$28") (pinfunction "BSTB_P$28") (pintype "bidirectional"))
    )
    (net (code "305") (name "Net-(U11-BSTC)") (class "Default")
      (node (ref "C69") (pin "P$1") (pinfunction "P$1_P$1") (pintype "bidirectional"))
      (node (ref "U11") (pin "P$27") (pinfunction "BSTC_P$27") (pintype "bidirectional"))
    )
    (net (code "306") (name "Net-(U11-BSTD)") (class "Default")
      (node (ref "C74") (pin "P$1") (pinfunction "P$1_P$1") (pintype "bidirectional"))
      (node (ref "U11") (pin "P$20") (pinfunction "BSTD_P$20") (pintype "bidirectional"))
    )
    (net (code "307") (name "Net-(U11-OUTA)") (class "Default")
      (node (ref "C63") (pin "P$2") (pinfunction "P$2_P$2") (pintype "bidirectional"))
      (node (ref "R25") (pin "P$1") (pinfunction "P$1_P$1") (pintype "bidirectional"))
      (node (ref "U11") (pin "P$33") (pinfunction "OUTA_P$33") (pintype "bidirectional"))
      (node (ref "U8") (pin "P$2") (pinfunction "IN+_P$2") (pintype "bidirectional"))
    )
    (net (code "308") (name "Net-(U14-BSTA)") (class "Default")
      (node (ref "C85") (pin "P$1") (pinfunction "P$1_P$1") (pintype "bidirectional"))
      (node (ref "U14") (pin "P$35") (pinfunction "BSTA_P$35") (pintype "bidirectional"))
    )
    (net (code "309") (name "Net-(U14-BSTB)") (class "Default")
      (node (ref "C86") (pin "P$1") (pinfunction "P$1_P$1") (pintype "bidirectional"))
      (node (ref "U14") (pin "P$28") (pinfunction "BSTB_P$28") (pintype "bidirectional"))
    )
    (net (code "310") (name "Net-(U14-BSTC)") (class "Default")
      (node (ref "C87") (pin "P$1") (pinfunction "P$1_P$1") (pintype "bidirectional"))
      (node (ref "U14") (pin "P$27") (pinfunction "BSTC_P$27") (pintype "bidirectional"))
    )
    (net (code "311") (name "Net-(U14-BSTD)") (class "Default")
      (node (ref "C88") (pin "P$1") (pinfunction "P$1_P$1") (pintype "bidirectional"))
      (node (ref "U14") (pin "P$20") (pinfunction "BSTD_P$20") (pintype "bidirectional"))
    )
    (net (code "312") (name "Net-(U16-IN+)") (class "Default")
      (node (ref "R36") (pin "P$1") (pinfunction "P$1_P$1") (pintype "bidirectional"))
      (node (ref "U16") (pin "P$2") (pinfunction "IN+_P$2") (pintype "bidirectional"))
      (node (ref "U17") (pin "PWR") (pinfunction "PWR_PWR") (pintype "bidirectional"))
    )
    (net (code "313") (name "Net-(U18-IN-)") (class "Default")
      (node (ref "R38") (pin "P$1") (pinfunction "P$1_P$1") (pintype "bidirectional"))
      (node (ref "U18") (pin "P$3") (pinfunction "IN-_P$3") (pintype "bidirectional"))
      (node (ref "U19") (pin "PWR") (pinfunction "PWR_PWR") (pintype "bidirectional"))
    )
    (net (code "314") (name "Net-(U20-USBDM0)") (class "Default")
      (node (ref "CON56") (pin "3") (pinfunction "3_3") (pintype "bidirectional"))
      (node (ref "U20") (pin "58") (pinfunction "USBDM0_58") (pintype "bidirectional"))
    )
    (net (code "315") (name "Net-(U20-USBDP0)") (class "Default")
      (node (ref "CON56") (pin "2") (pinfunction "2_2") (pintype "bidirectional"))
      (node (ref "U20") (pin "59") (pinfunction "USBDP0_59") (pintype "bidirectional"))
    )
    (net (code "316") (name "Net-(U33-SCL)") (class "Default")
      (node (ref "CON61") (pin "4") (pinfunction "4_4") (pintype "bidirectional"))
      (node (ref "CON62") (pin "4") (pinfunction "4_4") (pintype "bidirectional"))
      (node (ref "U33") (pin "P$10") (pinfunction "SCL_P$10") (pintype "bidirectional"))
      (node (ref "U34") (pin "P$12") (pinfunction "SCL_P$12") (pintype "bidirectional"))
    )
    (net (code "317") (name "Net-(U33-SDA)") (class "Default")
      (node (ref "CON61") (pin "2") (pinfunction "2_2") (pintype "bidirectional"))
      (node (ref "CON62") (pin "2") (pinfunction "2_2") (pintype "bidirectional"))
      (node (ref "U33") (pin "P$9") (pinfunction "SDA_P$9") (pintype "bidirectional"))
      (node (ref "U34") (pin "P$13") (pinfunction "SDA_P$13") (pintype "bidirectional"))
    )
    (net (code "318") (name "Net-(U34-P7)") (class "Default")
      (node (ref "CON61") (pin "3") (pinfunction "3_3") (pintype "bidirectional"))
      (node (ref "U34") (pin "P$10") (pinfunction "P7_P$10") (pintype "bidirectional"))
    )
    (net (code "319") (name "Net-(U34-VCCI)") (class "Default")
      (node (ref "C197") (pin "P$1") (pinfunction "P$1_P$1") (pintype "bidirectional"))
      (node (ref "U33") (pin "P$1") (pinfunction "VCC_P$1") (pintype "bidirectional"))
      (node (ref "U33") (pin "P$11") (pinfunction "VCC_P$11") (pintype "bidirectional"))
      (node (ref "U34") (pin "P$14") (pinfunction "VCCP_P$14") (pintype "bidirectional"))
      (node (ref "U34") (pin "P$15") (pinfunction "VCCI_P$15") (pintype "bidirectional"))
      (node (ref "U35") (pin "1") (pinfunction "VO_1") (pintype "bidirectional"))
    )
    (net (code "320") (name "Net-(U35-EN)") (class "Default")
      (node (ref "C198") (pin "P$1") (pinfunction "P$1_P$1") (pintype "bidirectional"))
      (node (ref "CON61") (pin "5") (pinfunction "5_5") (pintype "bidirectional"))
      (node (ref "CON62") (pin "5") (pinfunction "5_5") (pintype "bidirectional"))
      (node (ref "U35") (pin "4") (pinfunction "EN_4") (pintype "bidirectional"))
      (node (ref "U35") (pin "6") (pinfunction "VI_6") (pintype "bidirectional"))
    )
    (net (code "321") (name "Net-(U36-SCL)") (class "Default")
      (node (ref "CON63") (pin "4") (pinfunction "4_4") (pintype "bidirectional"))
      (node (ref "CON64") (pin "4") (pinfunction "4_4") (pintype "bidirectional"))
      (node (ref "U36") (pin "P$5") (pinfunction "SCL_P$5") (pintype "bidirectional"))
      (node (ref "U39") (pin "P$12") (pinfunction "SCL_P$12") (pintype "bidirectional"))
    )
    (net (code "322") (name "Net-(U36-SDA)") (class "Default")
      (node (ref "CON63") (pin "2") (pinfunction "2_2") (pintype "bidirectional"))
      (node (ref "CON64") (pin "2") (pinfunction "2_2") (pintype "bidirectional"))
      (node (ref "U36") (pin "P$6") (pinfunction "SDA_P$6") (pintype "bidirectional"))
      (node (ref "U39") (pin "P$13") (pinfunction "SDA_P$13") (pintype "bidirectional"))
    )
    (net (code "323") (name "Net-(U39-P7)") (class "Default")
      (node (ref "CON63") (pin "3") (pinfunction "3_3") (pintype "bidirectional"))
      (node (ref "U39") (pin "P$10") (pinfunction "P7_P$10") (pintype "bidirectional"))
    )
    (net (code "324") (name "Net-(U39-VCCI)") (class "Default")
      (node (ref "C196") (pin "P$1") (pinfunction "P$1_P$1") (pintype "bidirectional"))
      (node (ref "U36") (pin "P$10") (pinfunction "VCC_P$10") (pintype "bidirectional"))
      (node (ref "U36") (pin "P$8") (pinfunction "VCC_P$8") (pintype "bidirectional"))
      (node (ref "U39") (pin "P$14") (pinfunction "VCCP_P$14") (pintype "bidirectional"))
      (node (ref "U39") (pin "P$15") (pinfunction "VCCI_P$15") (pintype "bidirectional"))
      (node (ref "U40") (pin "1") (pinfunction "VO_1") (pintype "bidirectional"))
    )
    (net (code "325") (name "Net-(U40-EN)") (class "Default")
      (node (ref "C199") (pin "P$1") (pinfunction "P$1_P$1") (pintype "bidirectional"))
      (node (ref "CON63") (pin "5") (pinfunction "5_5") (pintype "bidirectional"))
      (node (ref "CON64") (pin "5") (pinfunction "5_5") (pintype "bidirectional"))
      (node (ref "U40") (pin "4") (pinfunction "EN_4") (pintype "bidirectional"))
      (node (ref "U40") (pin "6") (pinfunction "VI_6") (pintype "bidirectional"))
    )
    (net (code "326") (name "QEI0_A") (class "Default")
      (node (ref "CON57") (pin "14") (pinfunction "14_14") (pintype "bidirectional"))
      (node (ref "U27") (pin "P$9") (pinfunction "A8_P$9") (pintype "bidirectional"))
    )
    (net (code "327") (name "QEI0_A°") (class "Default")
      (node (ref "C111") (pin "2") (pinfunction "P$2_2") (pintype "bidirectional"))
      (node (ref "CON27") (pin "2") (pinfunction "2_2") (pintype "bidirectional"))
      (node (ref "R51") (pin "1") (pinfunction "P$1_1") (pintype "bidirectional"))
      (node (ref "U27") (pin "P$12") (pinfunction "B8_P$12") (pintype "bidirectional"))
    )
    (net (code "328") (name "QEI0_B") (class "Default")
      (node (ref "CON57") (pin "16") (pinfunction "16_16") (pintype "bidirectional"))
      (node (ref "U27") (pin "P$8") (pinfunction "A7_P$8") (pintype "bidirectional"))
    )
    (net (code "329") (name "QEI0_B°") (class "Default")
      (node (ref "C110") (pin "2") (pinfunction "P$2_2") (pintype "bidirectional"))
      (node (ref "CON27") (pin "3") (pinfunction "3_3") (pintype "bidirectional"))
      (node (ref "R50") (pin "1") (pinfunction "P$1_1") (pintype "bidirectional"))
      (node (ref "U27") (pin "P$13") (pinfunction "B7_P$13") (pintype "bidirectional"))
    )
    (net (code "330") (name "QEI1_A") (class "Default")
      (node (ref "CON58") (pin "36") (pinfunction "36_36") (pintype "bidirectional"))
      (node (ref "U30") (pin "P$3") (pinfunction "A2_P$3") (pintype "bidirectional"))
    )
    (net (code "331") (name "QEI1_A°") (class "Default")
      (node (ref "C105") (pin "2") (pinfunction "P$2_2") (pintype "bidirectional"))
      (node (ref "CON19") (pin "2") (pinfunction "2_2") (pintype "bidirectional"))
      (node (ref "R40") (pin "1") (pinfunction "P$1_1") (pintype "bidirectional"))
      (node (ref "U30") (pin "P$18") (pinfunction "B2_P$18") (pintype "bidirectional"))
    )
    (net (code "332") (name "QEI1_B") (class "Default")
      (node (ref "CON58") (pin "38") (pinfunction "38_38") (pintype "bidirectional"))
      (node (ref "U30") (pin "P$1") (pinfunction "A1_P$1") (pintype "bidirectional"))
    )
    (net (code "333") (name "QEI1_B°") (class "Default")
      (node (ref "C104") (pin "2") (pinfunction "P$2_2") (pintype "bidirectional"))
      (node (ref "CON19") (pin "3") (pinfunction "3_3") (pintype "bidirectional"))
      (node (ref "R39") (pin "1") (pinfunction "P$1_1") (pintype "bidirectional"))
      (node (ref "U30") (pin "P$20") (pinfunction "B1_P$20") (pintype "bidirectional"))
    )
    (net (code "334") (name "QEI2_A") (class "Default")
      (node (ref "CON57") (pin "18") (pinfunction "18_18") (pintype "bidirectional"))
      (node (ref "U27") (pin "P$7") (pinfunction "A6_P$7") (pintype "bidirectional"))
    )
    (net (code "335") (name "QEI2_A°") (class "Default")
      (node (ref "C128") (pin "2") (pinfunction "P$2_2") (pintype "bidirectional"))
      (node (ref "R73") (pin "1") (pinfunction "P$1_1") (pintype "bidirectional"))
      (node (ref "U27") (pin "P$14") (pinfunction "B6_P$14") (pintype "bidirectional"))
    )
    (net (code "336") (name "QEI2_B") (class "Default")
      (node (ref "CON57") (pin "19") (pinfunction "19_19") (pintype "bidirectional"))
      (node (ref "U27") (pin "P$6") (pinfunction "A5_P$6") (pintype "bidirectional"))
    )
    (net (code "337") (name "QEI2_B°") (class "Default")
      (node (ref "C127") (pin "2") (pinfunction "P$2_2") (pintype "bidirectional"))
      (node (ref "R72") (pin "1") (pinfunction "P$1_1") (pintype "bidirectional"))
      (node (ref "U27") (pin "P$15") (pinfunction "B5_P$15") (pintype "bidirectional"))
    )
    (net (code "338") (name "QEI2_Z") (class "Default")
      (node (ref "CON57") (pin "20") (pinfunction "20_20") (pintype "bidirectional"))
      (node (ref "U27") (pin "P$5") (pinfunction "A4_P$5") (pintype "bidirectional"))
    )
    (net (code "339") (name "QEI2_Z°") (class "Default")
      (node (ref "C126") (pin "2") (pinfunction "P$2_2") (pintype "bidirectional"))
      (node (ref "R71") (pin "1") (pinfunction "P$1_1") (pintype "bidirectional"))
      (node (ref "U27") (pin "P$16") (pinfunction "B4_P$16") (pintype "bidirectional"))
    )
    (net (code "340") (name "QEI3_A") (class "Default")
      (node (ref "CON58") (pin "28") (pinfunction "28_28") (pintype "bidirectional"))
      (node (ref "U30") (pin "P$6") (pinfunction "A5_P$6") (pintype "bidirectional"))
    )
    (net (code "341") (name "QEI3_A°") (class "Default")
      (node (ref "C121") (pin "2") (pinfunction "P$2_2") (pintype "bidirectional"))
      (node (ref "R62") (pin "1") (pinfunction "P$1_1") (pintype "bidirectional"))
      (node (ref "U30") (pin "P$15") (pinfunction "B5_P$15") (pintype "bidirectional"))
    )
    (net (code "342") (name "QEI3_B") (class "Default")
      (node (ref "CON58") (pin "32") (pinfunction "32_32") (pintype "bidirectional"))
      (node (ref "U30") (pin "P$5") (pinfunction "A4_P$5") (pintype "bidirectional"))
    )
    (net (code "343") (name "QEI3_B°") (class "Default")
      (node (ref "C120") (pin "2") (pinfunction "P$2_2") (pintype "bidirectional"))
      (node (ref "R61") (pin "1") (pinfunction "P$1_1") (pintype "bidirectional"))
      (node (ref "U30") (pin "P$16") (pinfunction "B4_P$16") (pintype "bidirectional"))
    )
    (net (code "344") (name "QEI3_Z") (class "Default")
      (node (ref "CON58") (pin "34") (pinfunction "34_34") (pintype "bidirectional"))
      (node (ref "U30") (pin "P$4") (pinfunction "A3_P$4") (pintype "bidirectional"))
    )
    (net (code "345") (name "QEI3_Z°") (class "Default")
      (node (ref "C119") (pin "2") (pinfunction "P$2_2") (pintype "bidirectional"))
      (node (ref "R58") (pin "1") (pinfunction "P$1_1") (pintype "bidirectional"))
      (node (ref "U30") (pin "P$17") (pinfunction "B3_P$17") (pintype "bidirectional"))
    )
    (net (code "346") (name "RX0") (class "Default")
      (node (ref "CON57") (pin "39") (pinfunction "39_39") (pintype "bidirectional"))
      (node (ref "U25") (pin "P$3") (pinfunction "A2_P$3") (pintype "bidirectional"))
    )
    (net (code "347") (name "RX0°") (class "Default")
      (node (ref "CON18") (pin "2") (pinfunction "2_2") (pintype "bidirectional"))
      (node (ref "U25") (pin "P$18") (pinfunction "B2_P$18") (pintype "bidirectional"))
    )
    (net (code "348") (name "RX1") (class "Default")
      (node (ref "CON58") (pin "4") (pinfunction "4_4") (pintype "bidirectional"))
      (node (ref "U32") (pin "P$9") (pinfunction "A8_P$9") (pintype "bidirectional"))
    )
    (net (code "349") (name "RX1°") (class "Default")
      (node (ref "CON26") (pin "2") (pinfunction "2_2") (pintype "bidirectional"))
      (node (ref "U32") (pin "P$12") (pinfunction "B8_P$12") (pintype "bidirectional"))
    )
    (net (code "350") (name "RX2") (class "Default")
      (node (ref "CON57") (pin "37") (pinfunction "37_37") (pintype "bidirectional"))
      (node (ref "U25") (pin "P$5") (pinfunction "A4_P$5") (pintype "bidirectional"))
    )
    (net (code "351") (name "RX2°") (class "Default")
      (node (ref "CON31") (pin "2") (pinfunction "2_2") (pintype "bidirectional"))
      (node (ref "U25") (pin "P$16") (pinfunction "B4_P$16") (pintype "bidirectional"))
    )
    (net (code "352") (name "RX3") (class "Default")
      (node (ref "CON58") (pin "8") (pinfunction "8_8") (pintype "bidirectional"))
      (node (ref "U32") (pin "P$7") (pinfunction "A6_P$7") (pintype "bidirectional"))
    )
    (net (code "353") (name "RX3°") (class "Default")
      (node (ref "CON36") (pin "2") (pinfunction "2_2") (pintype "bidirectional"))
      (node (ref "U32") (pin "P$14") (pinfunction "B6_P$14") (pintype "bidirectional"))
    )
    (net (code "354") (name "S0") (class "Default")
      (node (ref "CON58") (pin "15") (pinfunction "15_15") (pintype "bidirectional"))
      (node (ref "U26") (pin "P$9") (pinfunction "A8_P$9") (pintype "bidirectional"))
    )
    (net (code "355") (name "S0_CS") (class "Default")
      (node (ref "C101") (pin "2") (pinfunction "P$2_2") (pintype "bidirectional"))
      (node (ref "IC1") (pin "33") (pinfunction "AIN15_33") (pintype "passive"))
      (node (ref "R44") (pin "1") (pinfunction "P$1_1") (pintype "bidirectional"))
    )
    (net (code "356") (name "S0°") (class "Default")
      (node (ref "CON21") (pin "3") (pinfunction "3_3") (pintype "bidirectional"))
      (node (ref "U26") (pin "P$12") (pinfunction "B8_P$12") (pintype "bidirectional"))
    )
    (net (code "357") (name "S1") (class "Default")
      (node (ref "CON58") (pin "13") (pinfunction "13_13") (pintype "bidirectional"))
      (node (ref "U26") (pin "P$8") (pinfunction "A7_P$8") (pintype "bidirectional"))
    )
    (net (code "358") (name "S1_CS") (class "Default")
      (node (ref "C107") (pin "2") (pinfunction "P$2_2") (pintype "bidirectional"))
      (node (ref "IC1") (pin "34") (pinfunction "AIN14_34") (pintype "passive"))
      (node (ref "R49") (pin "1") (pinfunction "P$1_1") (pintype "bidirectional"))
    )
    (net (code "359") (name "S1°") (class "Default")
      (node (ref "CON24") (pin "3") (pinfunction "3_3") (pintype "bidirectional"))
      (node (ref "U26") (pin "P$13") (pinfunction "B7_P$13") (pintype "bidirectional"))
    )
    (net (code "360") (name "S2") (class "Default")
      (node (ref "CON58") (pin "9") (pinfunction "9_9") (pintype "bidirectional"))
      (node (ref "U26") (pin "P$7") (pinfunction "A6_P$7") (pintype "bidirectional"))
    )
    (net (code "361") (name "S2_CS") (class "Default")
      (node (ref "C113") (pin "2") (pinfunction "P$2_2") (pintype "bidirectional"))
      (node (ref "IC1") (pin "35") (pinfunction "AIN13_35") (pintype "passive"))
      (node (ref "R56") (pin "1") (pinfunction "P$1_1") (pintype "bidirectional"))
    )
    (net (code "362") (name "S2°") (class "Default")
      (node (ref "CON29") (pin "3") (pinfunction "3_3") (pintype "bidirectional"))
      (node (ref "U26") (pin "P$14") (pinfunction "B6_P$14") (pintype "bidirectional"))
    )
    (net (code "363") (name "S3") (class "Default")
      (node (ref "CON58") (pin "7") (pinfunction "7_7") (pintype "bidirectional"))
      (node (ref "U26") (pin "P$6") (pinfunction "A5_P$6") (pintype "bidirectional"))
    )
    (net (code "364") (name "S3_CS") (class "Default")
      (node (ref "C116") (pin "2") (pinfunction "P$2_2") (pintype "bidirectional"))
      (node (ref "IC1") (pin "36") (pinfunction "AIN12_36") (pintype "passive"))
      (node (ref "R64") (pin "1") (pinfunction "P$1_1") (pintype "bidirectional"))
    )
    (net (code "365") (name "S3°") (class "Default")
      (node (ref "CON34") (pin "3") (pinfunction "3_3") (pintype "bidirectional"))
      (node (ref "U26") (pin "P$15") (pinfunction "B5_P$15") (pintype "bidirectional"))
    )
    (net (code "366") (name "S4") (class "Default")
      (node (ref "CON57") (pin "31") (pinfunction "31_31") (pintype "bidirectional"))
      (node (ref "U26") (pin "P$5") (pinfunction "A4_P$5") (pintype "bidirectional"))
    )
    (net (code "367") (name "S4_CS") (class "Default")
      (node (ref "C123") (pin "2") (pinfunction "P$2_2") (pintype "bidirectional"))
      (node (ref "IC1") (pin "37") (pinfunction "AIN11_37") (pintype "passive"))
      (node (ref "R69") (pin "1") (pinfunction "P$1_1") (pintype "bidirectional"))
    )
    (net (code "368") (name "S4°") (class "Default")
      (node (ref "CON38") (pin "3") (pinfunction "3_3") (pintype "bidirectional"))
      (node (ref "U26") (pin "P$16") (pinfunction "B4_P$16") (pintype "bidirectional"))
    )
    (net (code "369") (name "S5") (class "Default")
      (node (ref "U26") (pin "P$4") (pinfunction "A3_P$4") (pintype "bidirectional"))
      (node (ref "U29") (pin "D0") (pinfunction "D0_D0") (pintype "bidirectional"))
    )
    (net (code "370") (name "S5_CS") (class "Default")
      (node (ref "C130") (pin "2") (pinfunction "P$2_2") (pintype "bidirectional"))
      (node (ref "IC1") (pin "38") (pinfunction "AIN10_38") (pintype "passive"))
      (node (ref "R77") (pin "1") (pinfunction "P$1_1") (pintype "bidirectional"))
    )
    (net (code "371") (name "S5°") (class "Default")
      (node (ref "CON43") (pin "3") (pinfunction "3_3") (pintype "bidirectional"))
      (node (ref "U26") (pin "P$17") (pinfunction "B3_P$17") (pintype "bidirectional"))
    )
    (net (code "372") (name "S6") (class "Default")
      (node (ref "U26") (pin "P$3") (pinfunction "A2_P$3") (pintype "bidirectional"))
      (node (ref "U29") (pin "D1") (pinfunction "D1_D1") (pintype "bidirectional"))
    )
    (net (code "373") (name "S6_CS") (class "Default")
      (node (ref "C133") (pin "2") (pinfunction "P$2_2") (pintype "bidirectional"))
      (node (ref "IC1") (pin "39") (pinfunction "AIN9_39") (pintype "passive"))
      (node (ref "R82") (pin "1") (pinfunction "P$1_1") (pintype "bidirectional"))
    )
    (net (code "374") (name "S6°") (class "Default")
      (node (ref "CON47") (pin "3") (pinfunction "3_3") (pintype "bidirectional"))
      (node (ref "U26") (pin "P$18") (pinfunction "B2_P$18") (pintype "bidirectional"))
    )
    (net (code "375") (name "S7") (class "Default")
      (node (ref "U26") (pin "P$1") (pinfunction "A1_P$1") (pintype "bidirectional"))
      (node (ref "U29") (pin "D2") (pinfunction "D2_D2") (pintype "bidirectional"))
    )
    (net (code "376") (name "S7_CS") (class "Default")
      (node (ref "C136") (pin "2") (pinfunction "P$2_2") (pintype "bidirectional"))
      (node (ref "IC1") (pin "40") (pinfunction "AIN8_40") (pintype "passive"))
      (node (ref "R87") (pin "1") (pinfunction "P$1_1") (pintype "bidirectional"))
    )
    (net (code "377") (name "S7°") (class "Default")
      (node (ref "CON51") (pin "3") (pinfunction "3_3") (pintype "bidirectional"))
      (node (ref "U26") (pin "P$20") (pinfunction "B1_P$20") (pintype "bidirectional"))
    )
    (net (code "378") (name "SCL0") (class "Default")
      (node (ref "CON57") (pin "23") (pinfunction "23_23") (pintype "bidirectional"))
      (node (ref "R101") (pin "1") (pinfunction "P$1_1") (pintype "bidirectional"))
      (node (ref "U27") (pin "P$1") (pinfunction "A1_P$1") (pintype "bidirectional"))
    )
    (net (code "379") (name "SCL0°") (class "Default")
      (node (ref "CON49") (pin "4") (pinfunction "4_4") (pintype "bidirectional"))
      (node (ref "R99") (pin "1") (pinfunction "P$1_1") (pintype "bidirectional"))
      (node (ref "U27") (pin "P$20") (pinfunction "B1_P$20") (pintype "bidirectional"))
    )
    (net (code "380") (name "SCL1") (class "Default")
      (node (ref "CON58") (pin "26") (pinfunction "26_26") (pintype "bidirectional"))
      (node (ref "R106") (pin "1") (pinfunction "P$1_1") (pintype "bidirectional"))
      (node (ref "U30") (pin "P$7") (pinfunction "A6_P$7") (pintype "bidirectional"))
    )
    (net (code "381") (name "SCL1°") (class "Default")
      (node (ref "CON53") (pin "4") (pinfunction "4_4") (pintype "bidirectional"))
      (node (ref "R103") (pin "1") (pinfunction "P$1_1") (pintype "bidirectional"))
      (node (ref "U30") (pin "P$14") (pinfunction "B6_P$14") (pintype "bidirectional"))
    )
    (net (code "382") (name "SCLK0") (class "Default")
      (node (ref "CON57") (pin "33") (pinfunction "33_33") (pintype "bidirectional"))
      (node (ref "U25") (pin "P$9") (pinfunction "A8_P$9") (pintype "bidirectional"))
    )
    (net (code "383") (name "SCLK0°") (class "Default")
      (node (ref "CON40") (pin "2") (pinfunction "2_2") (pintype "bidirectional"))
      (node (ref "U25") (pin "P$12") (pinfunction "B8_P$12") (pintype "bidirectional"))
    )
    (net (code "384") (name "SCLK1") (class "Default")
      (node (ref "CON58") (pin "14") (pinfunction "14_14") (pintype "bidirectional"))
      (node (ref "U32") (pin "P$5") (pinfunction "A4_P$5") (pintype "bidirectional"))
      (node (ref "U37") (pin "23") (pinfunction "SCL/SCLK_23") (pintype "bidirectional"))
    )
    (net (code "385") (name "SCLK1°") (class "Default")
      (node (ref "CON45") (pin "2") (pinfunction "2_2") (pintype "bidirectional"))
      (node (ref "U32") (pin "P$16") (pinfunction "B4_P$16") (pintype "bidirectional"))
    )
    (net (code "386") (name "SDA0") (class "Default")
      (node (ref "CON57") (pin "21") (pinfunction "21_21") (pintype "bidirectional"))
      (node (ref "R102") (pin "1") (pinfunction "P$1_1") (pintype "bidirectional"))
      (node (ref "U27") (pin "P$4") (pinfunction "A3_P$4") (pintype "bidirectional"))
    )
    (net (code "387") (name "SDA0°") (class "Default")
      (node (ref "CON49") (pin "2") (pinfunction "2_2") (pintype "bidirectional"))
      (node (ref "R100") (pin "1") (pinfunction "P$1_1") (pintype "bidirectional"))
      (node (ref "U27") (pin "P$17") (pinfunction "B3_P$17") (pintype "bidirectional"))
    )
    (net (code "388") (name "SDA1") (class "Default")
      (node (ref "CON58") (pin "22") (pinfunction "22_22") (pintype "bidirectional"))
      (node (ref "R105") (pin "1") (pinfunction "P$1_1") (pintype "bidirectional"))
      (node (ref "U30") (pin "P$9") (pinfunction "A8_P$9") (pintype "bidirectional"))
    )
    (net (code "389") (name "SDA1°") (class "Default")
      (node (ref "CON53") (pin "2") (pinfunction "2_2") (pintype "bidirectional"))
      (node (ref "R104") (pin "1") (pinfunction "P$1_1") (pintype "bidirectional"))
      (node (ref "U30") (pin "P$12") (pinfunction "B8_P$12") (pintype "bidirectional"))
    )
    (net (code "390") (name "SS0") (class "Default")
      (node (ref "CON57") (pin "34") (pinfunction "34_34") (pintype "bidirectional"))
      (node (ref "U25") (pin "P$8") (pinfunction "A7_P$8") (pintype "bidirectional"))
    )
    (net (code "391") (name "SS0°") (class "Default")
      (node (ref "CON40") (pin "3") (pinfunction "3_3") (pintype "bidirectional"))
      (node (ref "U25") (pin "P$13") (pinfunction "B7_P$13") (pintype "bidirectional"))
    )
    (net (code "392") (name "SS1") (class "Default")
      (node (ref "CON58") (pin "16") (pinfunction "16_16") (pintype "bidirectional"))
      (node (ref "U32") (pin "P$4") (pinfunction "A3_P$4") (pintype "bidirectional"))
    )
    (net (code "393") (name "SS1°") (class "Default")
      (node (ref "CON45") (pin "3") (pinfunction "3_3") (pintype "bidirectional"))
      (node (ref "U32") (pin "P$17") (pinfunction "B3_P$17") (pintype "bidirectional"))
    )
    (net (code "394") (name "TELEM") (class "Default")
      (node (ref "U29") (pin "D9") (pinfunction "D9_D9") (pintype "bidirectional"))
      (node (ref "U31") (pin "P$1") (pinfunction "A1_P$1") (pintype "bidirectional"))
    )
    (net (code "395") (name "TELEM°") (class "Default")
      (node (ref "CON31") (pin "5") (pinfunction "5_5") (pintype "bidirectional"))
      (node (ref "U31") (pin "P$20") (pinfunction "B1_P$20") (pintype "bidirectional"))
    )
    (net (code "396") (name "TX0") (class "Default")
      (node (ref "CON57") (pin "40") (pinfunction "40_40") (pintype "bidirectional"))
      (node (ref "U25") (pin "P$1") (pinfunction "A1_P$1") (pintype "bidirectional"))
    )
    (net (code "397") (name "TX0°") (class "Default")
      (node (ref "CON18") (pin "3") (pinfunction "3_3") (pintype "bidirectional"))
      (node (ref "U25") (pin "P$20") (pinfunction "B1_P$20") (pintype "bidirectional"))
    )
    (net (code "398") (name "TX1") (class "Default")
      (node (ref "CON58") (pin "6") (pinfunction "6_6") (pintype "bidirectional"))
      (node (ref "U32") (pin "P$8") (pinfunction "A7_P$8") (pintype "bidirectional"))
    )
    (net (code "399") (name "TX1°") (class "Default")
      (node (ref "CON26") (pin "3") (pinfunction "3_3") (pintype "bidirectional"))
      (node (ref "U32") (pin "P$13") (pinfunction "B7_P$13") (pintype "bidirectional"))
    )
    (net (code "400") (name "TX2") (class "Default")
      (node (ref "CON57") (pin "38") (pinfunction "38_38") (pintype "bidirectional"))
      (node (ref "U25") (pin "P$4") (pinfunction "A3_P$4") (pintype "bidirectional"))
    )
    (net (code "401") (name "TX2°") (class "Default")
      (node (ref "CON31") (pin "3") (pinfunction "3_3") (pintype "bidirectional"))
      (node (ref "U25") (pin "P$17") (pinfunction "B3_P$17") (pintype "bidirectional"))
    )
    (net (code "402") (name "TX3") (class "Default")
      (node (ref "CON58") (pin "10") (pinfunction "10_10") (pintype "bidirectional"))
      (node (ref "U32") (pin "P$6") (pinfunction "A5_P$6") (pintype "bidirectional"))
    )
    (net (code "403") (name "TX3°") (class "Default")
      (node (ref "CON36") (pin "3") (pinfunction "3_3") (pintype "bidirectional"))
      (node (ref "U32") (pin "P$15") (pinfunction "B5_P$15") (pintype "bidirectional"))
    )
    (net (code "404") (name "WIFI0_DM") (class "Default")
      (node (ref "U20") (pin "8") (pinfunction "USBDM5_8") (pintype "bidirectional"))
      (node (ref "U21") (pin "P$5") (pinfunction "DM_P$5") (pintype "bidirectional"))
    )
    (net (code "405") (name "WIFI0_DP") (class "Default")
      (node (ref "U20") (pin "9") (pinfunction "USBDP5_9") (pintype "bidirectional"))
      (node (ref "U21") (pin "P$4") (pinfunction "DP_P$4") (pintype "bidirectional"))
    )
    (net (code "406") (name "WIFI1_DM") (class "Default")
      (node (ref "J48") (pin "P$2") (pinfunction "2_P$2") (pintype "bidirectional"))
      (node (ref "U20") (pin "1") (pinfunction "USBDM2_1") (pintype "bidirectional"))
      (node (ref "U22") (pin "P$5") (pinfunction "DM_P$5") (pintype "bidirectional"))
    )
    (net (code "407") (name "WIFI1_DP") (class "Default")
      (node (ref "J49") (pin "P$2") (pinfunction "2_P$2") (pintype "bidirectional"))
      (node (ref "U20") (pin "2") (pinfunction "USBDP2_2") (pintype "bidirectional"))
      (node (ref "U22") (pin "P$4") (pinfunction "DP_P$4") (pintype "bidirectional"))
    )
    (net (code "408") (name "unconnected-(CON18-Pad5)") (class "Default")
      (node (ref "CON18") (pin "5") (pinfunction "5_5") (pintype "bidirectional"))
    )
    (net (code "409") (name "unconnected-(CON26-Pad5)") (class "Default")
      (node (ref "CON26") (pin "5") (pinfunction "5_5") (pintype "bidirectional"))
    )
    (net (code "410") (name "unconnected-(CON57-Pad11)") (class "Default")
      (node (ref "CON57") (pin "11") (pinfunction "11_11") (pintype "bidirectional"))
    )
    (net (code "411") (name "unconnected-(CON58-Pad11)") (class "Default")
      (node (ref "CON58") (pin "11") (pinfunction "11_11") (pintype "bidirectional"))
    )
    (net (code "412") (name "unconnected-(CON59-1-PadP$1)") (class "Default")
      (node (ref "CON59") (pin "P$1") (pinfunction "1_P$1") (pintype "bidirectional"))
    )
    (net (code "413") (name "unconnected-(CON59-2-PadP$2)") (class "Default")
      (node (ref "CON59") (pin "P$2") (pinfunction "2_P$2") (pintype "bidirectional"))
    )
    (net (code "414") (name "unconnected-(CON59-3-PadP$3)") (class "Default")
      (node (ref "CON59") (pin "P$3") (pinfunction "3_P$3") (pintype "bidirectional"))
    )
    (net (code "415") (name "unconnected-(CON59-4-PadP$4)") (class "Default")
      (node (ref "CON59") (pin "P$4") (pinfunction "4_P$4") (pintype "bidirectional"))
    )
    (net (code "416") (name "unconnected-(CON59-5-PadP$5)") (class "Default")
      (node (ref "CON59") (pin "P$5") (pinfunction "5_P$5") (pintype "bidirectional"))
    )
    (net (code "417") (name "unconnected-(CON59-6-PadP$6)") (class "Default")
      (node (ref "CON59") (pin "P$6") (pinfunction "6_P$6") (pintype "bidirectional"))
    )
    (net (code "418") (name "unconnected-(CON59-7-PadP$7)") (class "Default")
      (node (ref "CON59") (pin "P$7") (pinfunction "7_P$7") (pintype "bidirectional"))
    )
    (net (code "419") (name "unconnected-(CON59-8-PadP$8)") (class "Default")
      (node (ref "CON59") (pin "P$8") (pinfunction "8_P$8") (pintype "bidirectional"))
    )
    (net (code "420") (name "unconnected-(CON59-9-PadP$9)") (class "Default")
      (node (ref "CON59") (pin "P$9") (pinfunction "9_P$9") (pintype "bidirectional"))
    )
    (net (code "421") (name "unconnected-(CON59-10-PadP$10)") (class "Default")
      (node (ref "CON59") (pin "P$10") (pinfunction "10_P$10") (pintype "bidirectional"))
    )
    (net (code "422") (name "unconnected-(CON59-11-PadP$11)") (class "Default")
      (node (ref "CON59") (pin "P$11") (pinfunction "11_P$11") (pintype "bidirectional"))
    )
    (net (code "423") (name "unconnected-(CON59-12-PadP$12)") (class "Default")
      (node (ref "CON59") (pin "P$12") (pinfunction "12_P$12") (pintype "bidirectional"))
    )
    (net (code "424") (name "unconnected-(CON59-13-PadP$13)") (class "Default")
      (node (ref "CON59") (pin "P$13") (pinfunction "13_P$13") (pintype "bidirectional"))
    )
    (net (code "425") (name "unconnected-(CON59-14-PadP$14)") (class "Default")
      (node (ref "CON59") (pin "P$14") (pinfunction "14_P$14") (pintype "bidirectional"))
    )
    (net (code "426") (name "unconnected-(IC1-CLKIO-Pad13)") (class "Default")
      (node (ref "IC1") (pin "13") (pinfunction "CLKIO_13") (pintype "passive"))
    )
    (net (code "427") (name "unconnected-(IC1-GPIO0-Pad14)") (class "Default")
      (node (ref "IC1") (pin "14") (pinfunction "GPIO0_14") (pintype "passive"))
    )
    (net (code "428") (name "unconnected-(IC1-GPIO1-Pad15)") (class "Default")
      (node (ref "IC1") (pin "15") (pinfunction "GPIO1_15") (pintype "passive"))
    )
    (net (code "429") (name "unconnected-(IC1-GPIO2-Pad16)") (class "Default")
      (node (ref "IC1") (pin "16") (pinfunction "GPIO2_16") (pintype "passive"))
    )
    (net (code "430") (name "unconnected-(IC1-GPIO3-Pad17)") (class "Default")
      (node (ref "IC1") (pin "17") (pinfunction "GPIO3_17") (pintype "passive"))
    )
    (net (code "431") (name "unconnected-(IC1-GPIO4-Pad18)") (class "Default")
      (node (ref "IC1") (pin "18") (pinfunction "GPIO4_18") (pintype "passive"))
    )
    (net (code "432") (name "unconnected-(IC1-GPIO5-Pad19)") (class "Default")
      (node (ref "IC1") (pin "19") (pinfunction "GPIO5_19") (pintype "passive"))
    )
    (net (code "433") (name "unconnected-(IC1-GPIO6-Pad20)") (class "Default")
      (node (ref "IC1") (pin "20") (pinfunction "GPIO6_20") (pintype "passive"))
    )
    (net (code "434") (name "unconnected-(IC1-GPIO7-Pad21)") (class "Default")
      (node (ref "IC1") (pin "21") (pinfunction "GPIO7_21") (pintype "passive"))
    )
    (net (code "435") (name "unconnected-(IC1-MUXOUTN-Pad43)") (class "Default")
      (node (ref "IC1") (pin "43") (pinfunction "MUXOUTN_43") (pintype "passive"))
    )
    (net (code "436") (name "unconnected-(IC2-DOUT2-Pad19)") (class "Default")
      (node (ref "IC2") (pin "19") (pinfunction "DOUT2_19") (pintype "passive"))
    )
    (net (code "437") (name "unconnected-(IC2-DOUT3-Pad18)") (class "Default")
      (node (ref "IC2") (pin "18") (pinfunction "DOUT3_18") (pintype "passive"))
    )
    (net (code "438") (name "unconnected-(IC2-DOUT4-Pad17)") (class "Default")
      (node (ref "IC2") (pin "17") (pinfunction "DOUT4_17") (pintype "passive"))
    )
    (net (code "439") (name "unconnected-(IC2-DOUT5-Pad16)") (class "Default")
      (node (ref "IC2") (pin "16") (pinfunction "DOUT5_16") (pintype "passive"))
    )
    (net (code "440") (name "unconnected-(IC2-DOUT6-Pad15)") (class "Default")
      (node (ref "IC2") (pin "15") (pinfunction "DOUT6_15") (pintype "passive"))
    )
    (net (code "441") (name "unconnected-(IC2-DOUT7-Pad14)") (class "Default")
      (node (ref "IC2") (pin "14") (pinfunction "DOUT7_14") (pintype "passive"))
    )
    (net (code "442") (name "unconnected-(IC2-DOUT8-Pad13)") (class "Default")
      (node (ref "IC2") (pin "13") (pinfunction "DOUT8_13") (pintype "passive"))
    )
    (net (code "443") (name "unconnected-(IC3-DNC-Pad1)") (class "Default")
      (node (ref "IC3") (pin "1") (pinfunction "DNC_1") (pintype "passive"))
    )
    (net (code "444") (name "unconnected-(IC3-DNC-Pad8)") (class "Default")
      (node (ref "IC3") (pin "8") (pinfunction "DNC_8") (pintype "passive"))
    )
    (net (code "445") (name "unconnected-(IC3-TEMP-Pad3)") (class "Default")
      (node (ref "IC3") (pin "3") (pinfunction "TEMP_3") (pintype "passive"))
    )
    (net (code "446") (name "unconnected-(IC4-DNC-Pad1)") (class "Default")
      (node (ref "IC4") (pin "1") (pinfunction "DNC_1") (pintype "passive"))
    )
    (net (code "447") (name "unconnected-(IC4-DNC-Pad8)") (class "Default")
      (node (ref "IC4") (pin "8") (pinfunction "DNC_8") (pintype "passive"))
    )
    (net (code "448") (name "unconnected-(IC4-TEMP-Pad3)") (class "Default")
      (node (ref "IC4") (pin "3") (pinfunction "TEMP_3") (pintype "passive"))
    )
    (net (code "449") (name "unconnected-(U3-INHIBIT-PadP$1)") (class "Default")
      (node (ref "U3") (pin "P$1") (pinfunction "INHIBIT_P$1") (pintype "bidirectional"))
    )
    (net (code "450") (name "unconnected-(U4-PG-PadP$7)") (class "Default")
      (node (ref "U4") (pin "P$7") (pinfunction "PG_P$7") (pintype "bidirectional"))
    )
    (net (code "451") (name "unconnected-(U5-PG-PadP$7)") (class "Default")
      (node (ref "U5") (pin "P$7") (pinfunction "PG_P$7") (pintype "bidirectional"))
    )
    (net (code "452") (name "unconnected-(U6-PG-PadP$7)") (class "Default")
      (node (ref "U6") (pin "P$7") (pinfunction "PG_P$7") (pintype "bidirectional"))
    )
    (net (code "453") (name "unconnected-(U20-CLK24_OUT-Pad45)") (class "Default")
      (node (ref "U20") (pin "45") (pinfunction "CLK24_OUT_45") (pintype "bidirectional"))
    )
    (net (code "454") (name "unconnected-(U20-EECLK-Pad23)") (class "Default")
      (node (ref "U20") (pin "23") (pinfunction "EECLK_23") (pintype "bidirectional"))
    )
    (net (code "455") (name "unconnected-(U20-EEDI-Pad26)") (class "Default")
      (node (ref "U20") (pin "26") (pinfunction "EEDI_26") (pintype "bidirectional"))
    )
    (net (code "456") (name "unconnected-(U20-EEDO-Pad25)") (class "Default")
      (node (ref "U20") (pin "25") (pinfunction "EEDO_25") (pintype "bidirectional"))
    )
    (net (code "457") (name "unconnected-(U20-GPIO3-Pad35)") (class "Default")
      (node (ref "U20") (pin "35") (pinfunction "GPIO3_35") (pintype "bidirectional"))
    )
    (net (code "458") (name "unconnected-(U20-GPIO4-Pad36)") (class "Default")
      (node (ref "U20") (pin "36") (pinfunction "GPIO4_36") (pintype "bidirectional"))
    )
    (net (code "459") (name "unconnected-(U20-GPIO5-Pad37)") (class "Default")
      (node (ref "U20") (pin "37") (pinfunction "GPIO5_37") (pintype "bidirectional"))
    )
    (net (code "460") (name "unconnected-(U20-GPIO6-Pad42)") (class "Default")
      (node (ref "U20") (pin "42") (pinfunction "GPIO6_42") (pintype "bidirectional"))
    )
    (net (code "461") (name "unconnected-(U20-GPIO7-Pad43)") (class "Default")
      (node (ref "U20") (pin "43") (pinfunction "GPIO7_43") (pintype "bidirectional"))
    )
    (net (code "462") (name "unconnected-(U20-NFDX_LED{slash}_GPIO0-Pad20)") (class "Default")
      (node (ref "U20") (pin "20") (pinfunction "NFDX_LED/_GPIO0_20") (pintype "bidirectional"))
    )
    (net (code "463") (name "unconnected-(U20-NLNKA_LED{slash}_GPIO1-Pad21)") (class "Default")
      (node (ref "U20") (pin "21") (pinfunction "NLNKA_LED/_GPIO1_21") (pintype "bidirectional"))
    )
    (net (code "464") (name "unconnected-(U20-NSPD_LED{slash}_GPIO2-Pad22)") (class "Default")
      (node (ref "U20") (pin "22") (pinfunction "NSPD_LED/_GPIO2_22") (pintype "bidirectional"))
    )
    (net (code "465") (name "unconnected-(U20-PRTCTL2-Pad14)") (class "Default")
      (node (ref "U20") (pin "14") (pinfunction "PRTCTL2_14") (pintype "bidirectional"))
    )
    (net (code "466") (name "unconnected-(U20-PRTCTL3-Pad16)") (class "Default")
      (node (ref "U20") (pin "16") (pinfunction "PRTCTL3_16") (pintype "bidirectional"))
    )
    (net (code "467") (name "unconnected-(U20-PRTCTL4-Pad17)") (class "Default")
      (node (ref "U20") (pin "17") (pinfunction "PRTCTL4_17") (pintype "bidirectional"))
    )
    (net (code "468") (name "unconnected-(U20-PRTCTL5-Pad18)") (class "Default")
      (node (ref "U20") (pin "18") (pinfunction "PRTCTL5_18") (pintype "bidirectional"))
    )
    (net (code "469") (name "unconnected-(U20-RXN-Pad53)") (class "Default")
      (node (ref "U20") (pin "53") (pinfunction "RXN_53") (pintype "bidirectional"))
    )
    (net (code "470") (name "unconnected-(U20-RXP-Pad52)") (class "Default")
      (node (ref "U20") (pin "52") (pinfunction "RXP_52") (pintype "bidirectional"))
    )
    (net (code "471") (name "unconnected-(U20-TCK-Pad32)") (class "Default")
      (node (ref "U20") (pin "32") (pinfunction "TCK_32") (pintype "bidirectional"))
    )
    (net (code "472") (name "unconnected-(U20-TDI-Pad30)") (class "Default")
      (node (ref "U20") (pin "30") (pinfunction "TDI_30") (pintype "bidirectional"))
    )
    (net (code "473") (name "unconnected-(U20-TDO-Pad31)") (class "Default")
      (node (ref "U20") (pin "31") (pinfunction "TDO_31") (pintype "bidirectional"))
    )
    (net (code "474") (name "unconnected-(U20-TEST1-Pad13)") (class "Default")
      (node (ref "U20") (pin "13") (pinfunction "TEST1_13") (pintype "bidirectional"))
    )
    (net (code "475") (name "unconnected-(U20-TEST4-Pad47)") (class "Default")
      (node (ref "U20") (pin "47") (pinfunction "TEST4_47") (pintype "bidirectional"))
    )
    (net (code "476") (name "unconnected-(U20-TMS-Pad29)") (class "Default")
      (node (ref "U20") (pin "29") (pinfunction "TMS_29") (pintype "bidirectional"))
    )
    (net (code "477") (name "unconnected-(U20-TXN-Pad56)") (class "Default")
      (node (ref "U20") (pin "56") (pinfunction "TXN_56") (pintype "bidirectional"))
    )
    (net (code "478") (name "unconnected-(U20-TXP-Pad55)") (class "Default")
      (node (ref "U20") (pin "55") (pinfunction "TXP_55") (pintype "bidirectional"))
    )
    (net (code "479") (name "unconnected-(U29-Pad3V)") (class "Default")
      (node (ref "U29") (pin "3V") (pinfunction "3V_3V") (pintype "bidirectional"))
    )
    (net (code "480") (name "unconnected-(U29-Pad5V)") (class "Default")
      (node (ref "U29") (pin "5V") (pinfunction "5V_5V") (pintype "bidirectional"))
    )
    (net (code "481") (name "unconnected-(U29-PadAREF)") (class "Default")
      (node (ref "U29") (pin "AREF") (pinfunction "AREF_AREF") (pintype "bidirectional"))
    )
    (net (code "482") (name "unconnected-(U29-PadIOREF)") (class "Default")
      (node (ref "U29") (pin "IOREF") (pinfunction "IOREF_IOREF") (pintype "output"))
    )
    (net (code "483") (name "unconnected-(U29-PadRESERVED)") (class "Default")
      (node (ref "U29") (pin "RESERVED") (pinfunction "RESERVED_RESERVED") (pintype "no_connect"))
    )
    (net (code "484") (name "unconnected-(U29-PadVIN)") (class "Default")
      (node (ref "U29") (pin "VIN") (pinfunction "VIN_VIN") (pintype "bidirectional"))
    )
    (net (code "485") (name "unconnected-(U31-A7-PadP$8)") (class "Default")
      (node (ref "U31") (pin "P$8") (pinfunction "A7_P$8") (pintype "bidirectional"))
    )
    (net (code "486") (name "unconnected-(U31-B7-PadP$13)") (class "Default")
      (node (ref "U31") (pin "P$13") (pinfunction "B7_P$13") (pintype "bidirectional"))
    )
    (net (code "487") (name "unconnected-(U33-DRDY-PadP$7)") (class "Default")
      (node (ref "U33") (pin "P$7") (pinfunction "DRDY_P$7") (pintype "bidirectional"))
    )
    (net (code "488") (name "unconnected-(U34-DRDY-PadP$11)") (class "Default")
      (node (ref "U34") (pin "P$11") (pinfunction "DRDY_P$11") (pintype "bidirectional"))
    )
    (net (code "489") (name "unconnected-(U34-P0-PadP$2)") (class "Default")
      (node (ref "U34") (pin "P$2") (pinfunction "P0_P$2") (pintype "bidirectional"))
    )
    (net (code "490") (name "unconnected-(U34-P1-PadP$3)") (class "Default")
      (node (ref "U34") (pin "P$3") (pinfunction "P1_P$3") (pintype "bidirectional"))
    )
    (net (code "491") (name "unconnected-(U34-P3-PadP$5)") (class "Default")
      (node (ref "U34") (pin "P$5") (pinfunction "P3_P$5") (pintype "bidirectional"))
    )
    (net (code "492") (name "unconnected-(U34-P4-PadP$7)") (class "Default")
      (node (ref "U34") (pin "P$7") (pinfunction "P4_P$7") (pintype "bidirectional"))
    )
    (net (code "493") (name "unconnected-(U34-P5-PadP$8)") (class "Default")
      (node (ref "U34") (pin "P$8") (pinfunction "P5_P$8") (pintype "bidirectional"))
    )
    (net (code "494") (name "unconnected-(U34-P6-PadP$9)") (class "Default")
      (node (ref "U34") (pin "P$9") (pinfunction "P6_P$9") (pintype "bidirectional"))
    )
    (net (code "495") (name "unconnected-(U36-DRDY-PadP$1)") (class "Default")
      (node (ref "U36") (pin "P$1") (pinfunction "DRDY_P$1") (pintype "bidirectional"))
    )
    (net (code "496") (name "unconnected-(U37-AUX_CL-Pad7)") (class "Default")
      (node (ref "U37") (pin "7") (pinfunction "AUX_CL_7") (pintype "bidirectional"))
    )
    (net (code "497") (name "unconnected-(U37-AUX_DA-Pad21)") (class "Default")
      (node (ref "U37") (pin "21") (pinfunction "AUX_DA_21") (pintype "bidirectional"))
    )
    (net (code "498") (name "unconnected-(U39-DRDY-PadP$11)") (class "Default")
      (node (ref "U39") (pin "P$11") (pinfunction "DRDY_P$11") (pintype "bidirectional"))
    )
    (net (code "499") (name "unconnected-(U39-P0-PadP$2)") (class "Default")
      (node (ref "U39") (pin "P$2") (pinfunction "P0_P$2") (pintype "bidirectional"))
    )
    (net (code "500") (name "unconnected-(U39-P1-PadP$3)") (class "Default")
      (node (ref "U39") (pin "P$3") (pinfunction "P1_P$3") (pintype "bidirectional"))
    )
    (net (code "501") (name "unconnected-(U39-P3-PadP$5)") (class "Default")
      (node (ref "U39") (pin "P$5") (pinfunction "P3_P$5") (pintype "bidirectional"))
    )
    (net (code "502") (name "unconnected-(U39-P4-PadP$7)") (class "Default")
      (node (ref "U39") (pin "P$7") (pinfunction "P4_P$7") (pintype "bidirectional"))
    )
    (net (code "503") (name "unconnected-(U39-P5-PadP$8)") (class "Default")
      (node (ref "U39") (pin "P$8") (pinfunction "P5_P$8") (pintype "bidirectional"))
    )
    (net (code "504") (name "unconnected-(U39-P6-PadP$9)") (class "Default")
      (node (ref "U39") (pin "P$9") (pinfunction "P6_P$9") (pintype "bidirectional"))
    )
  )
)
